# SPU_Rev_1_0.net
KiCad netlist of a schematic drawn in EAGLE
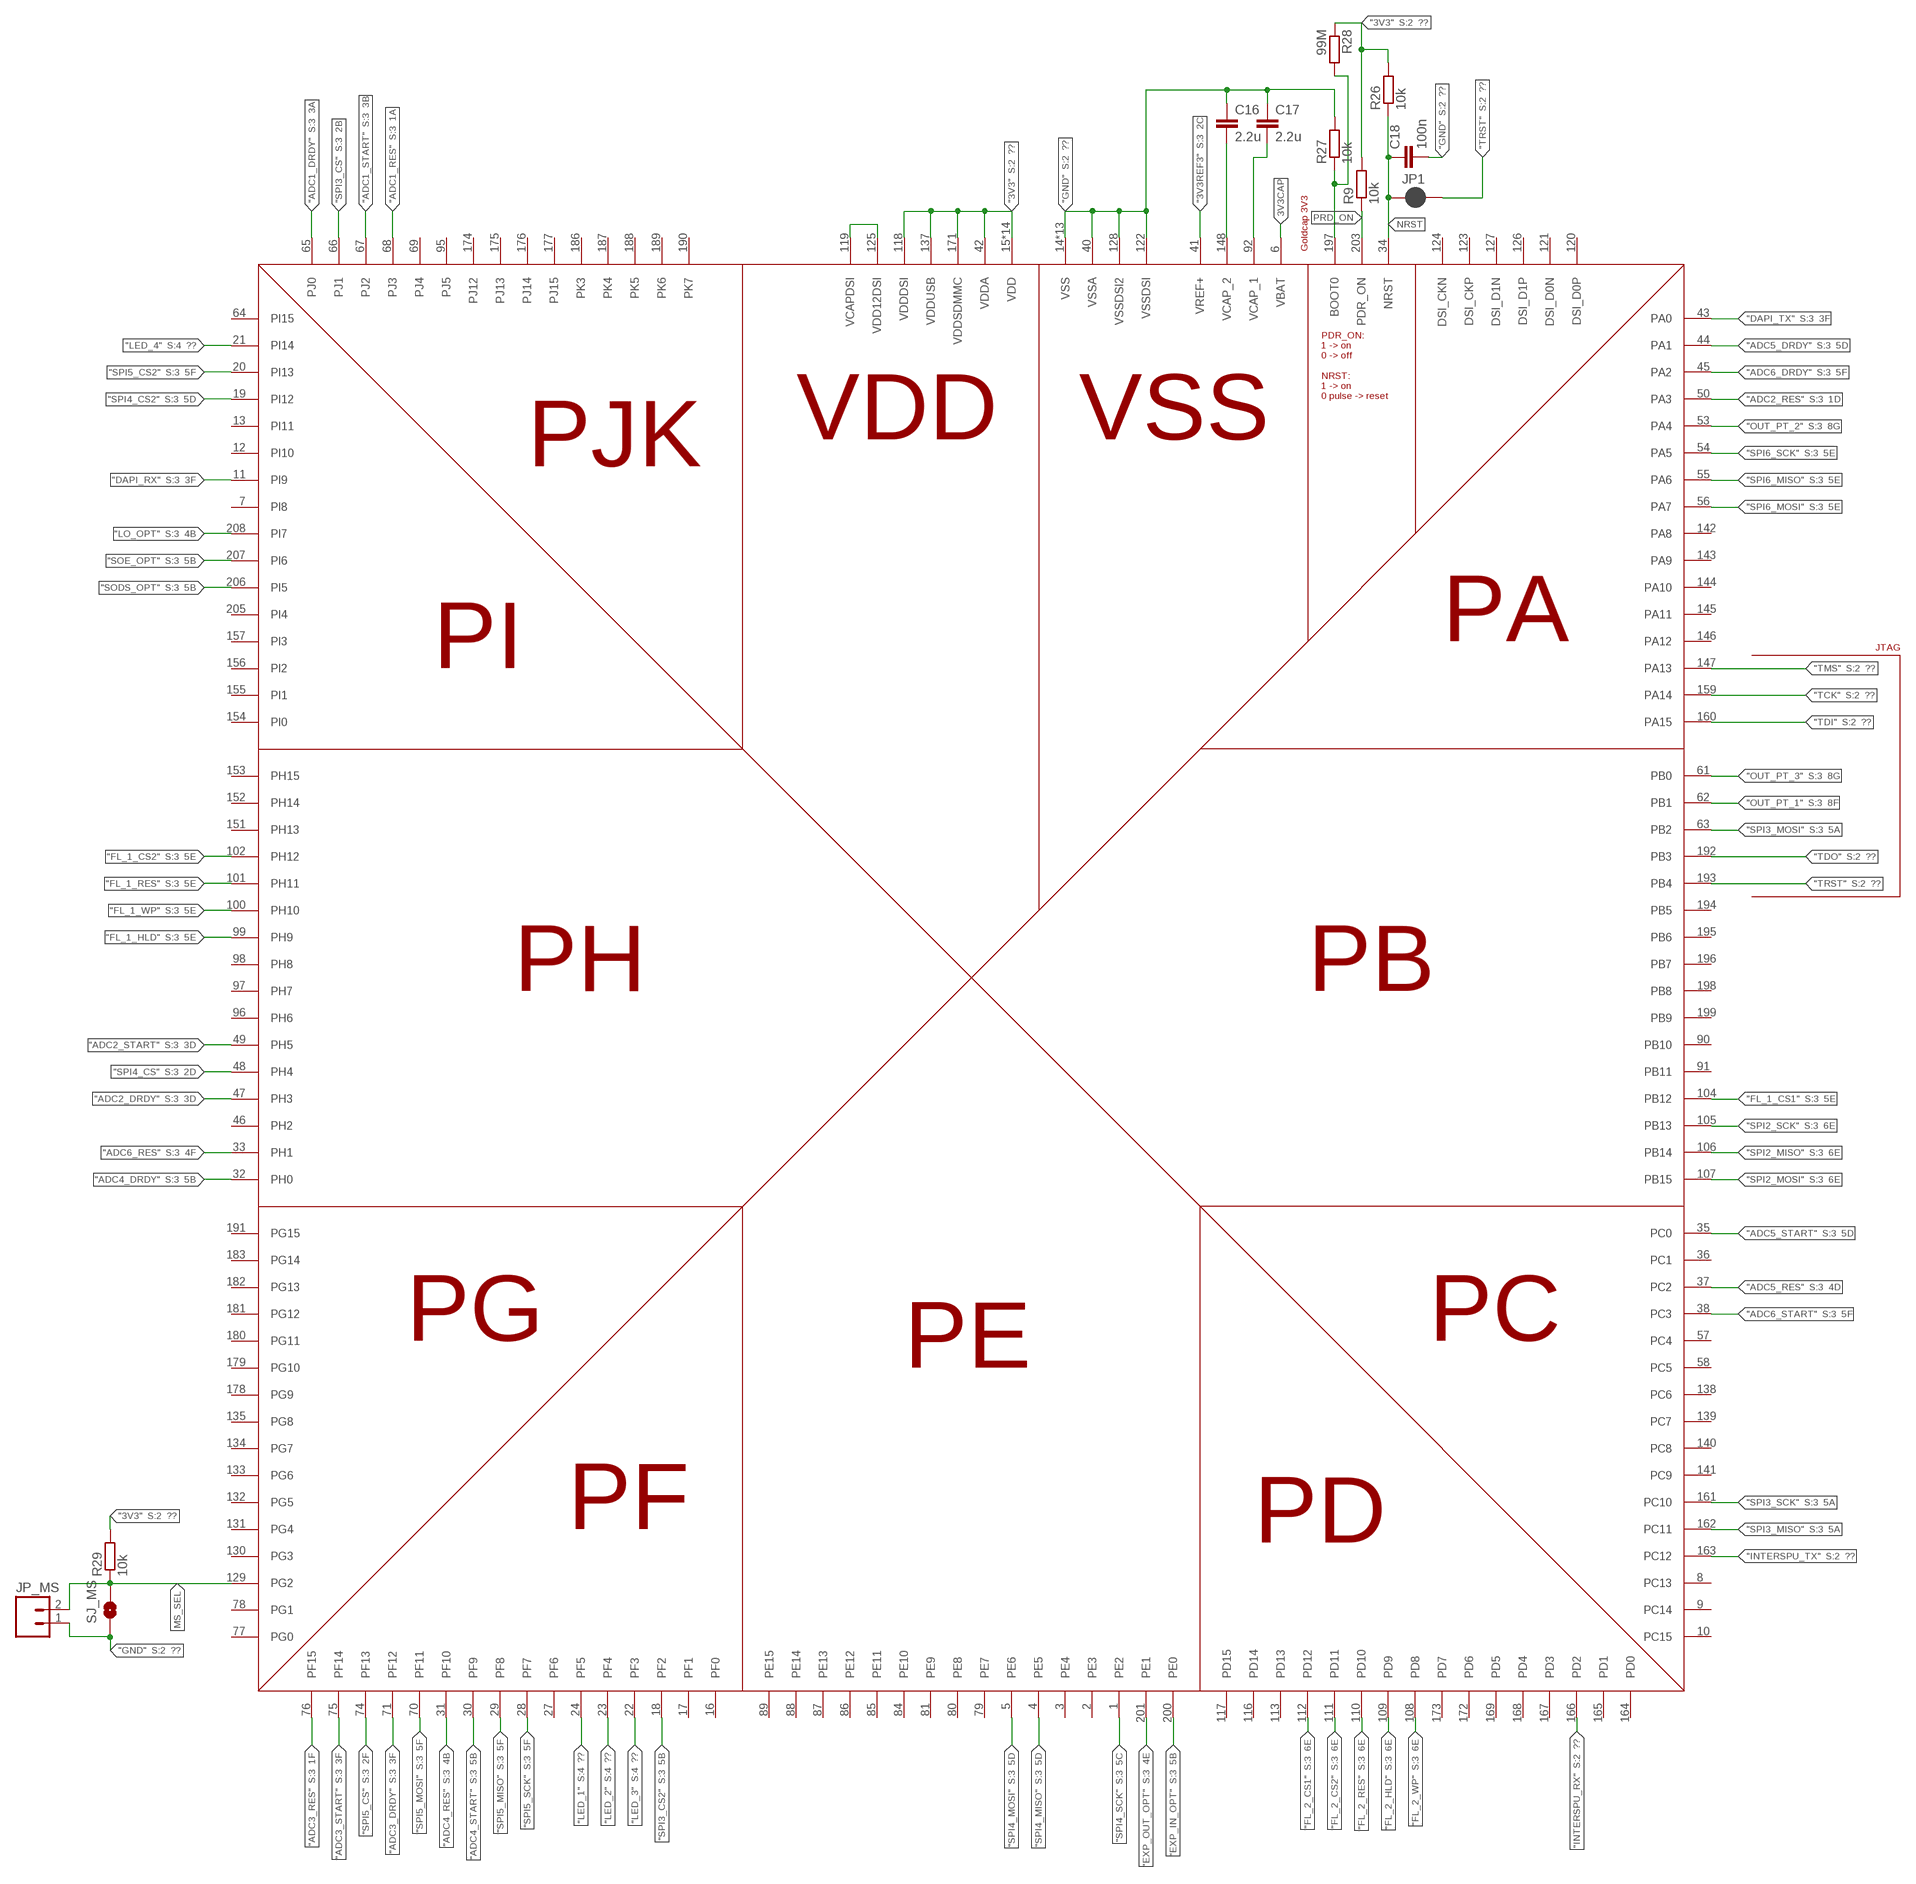
[diagram p0: schematic, sheet 1]
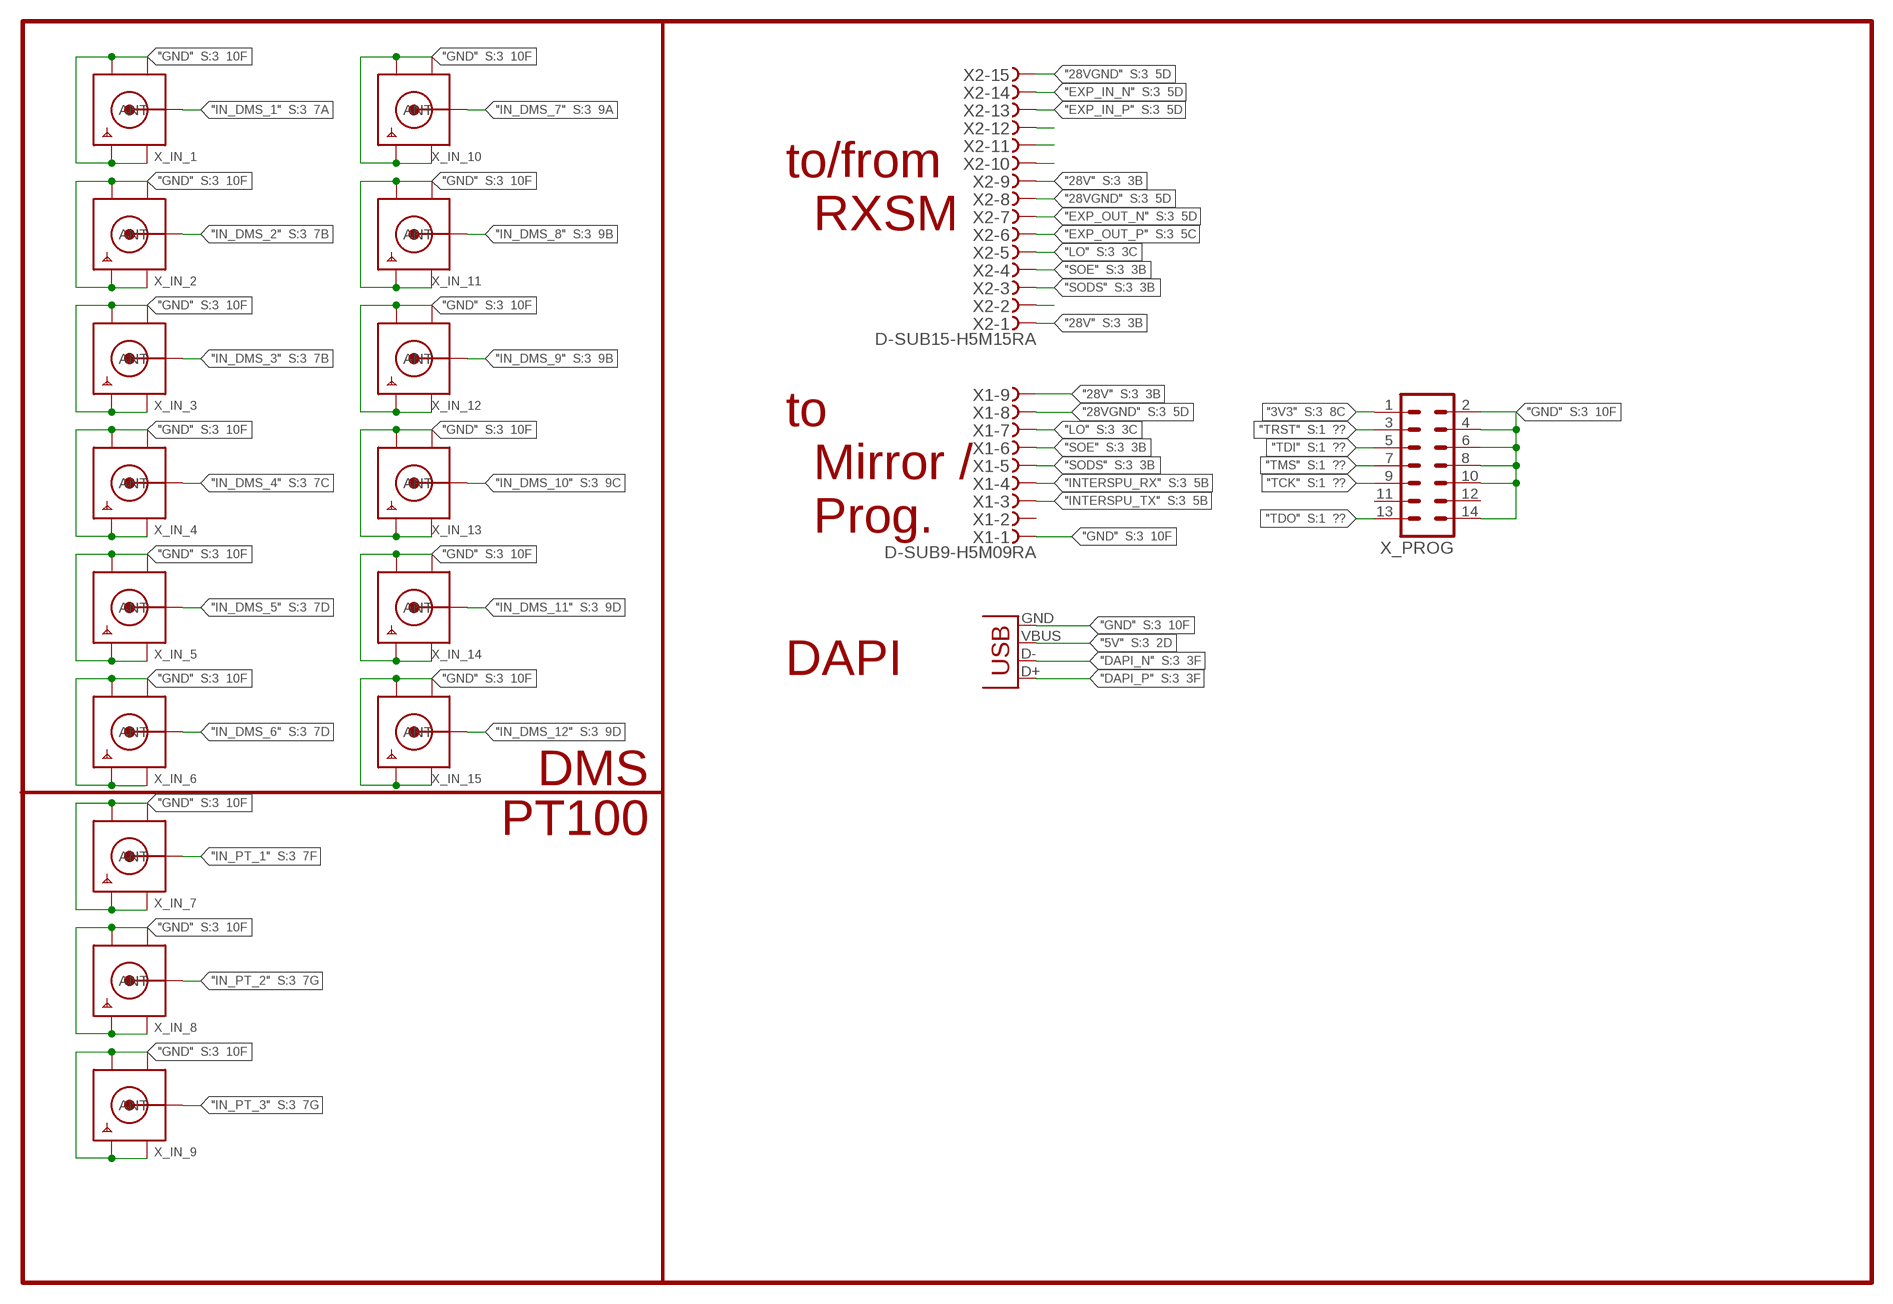
[diagram p1: schematic, sheet 2]
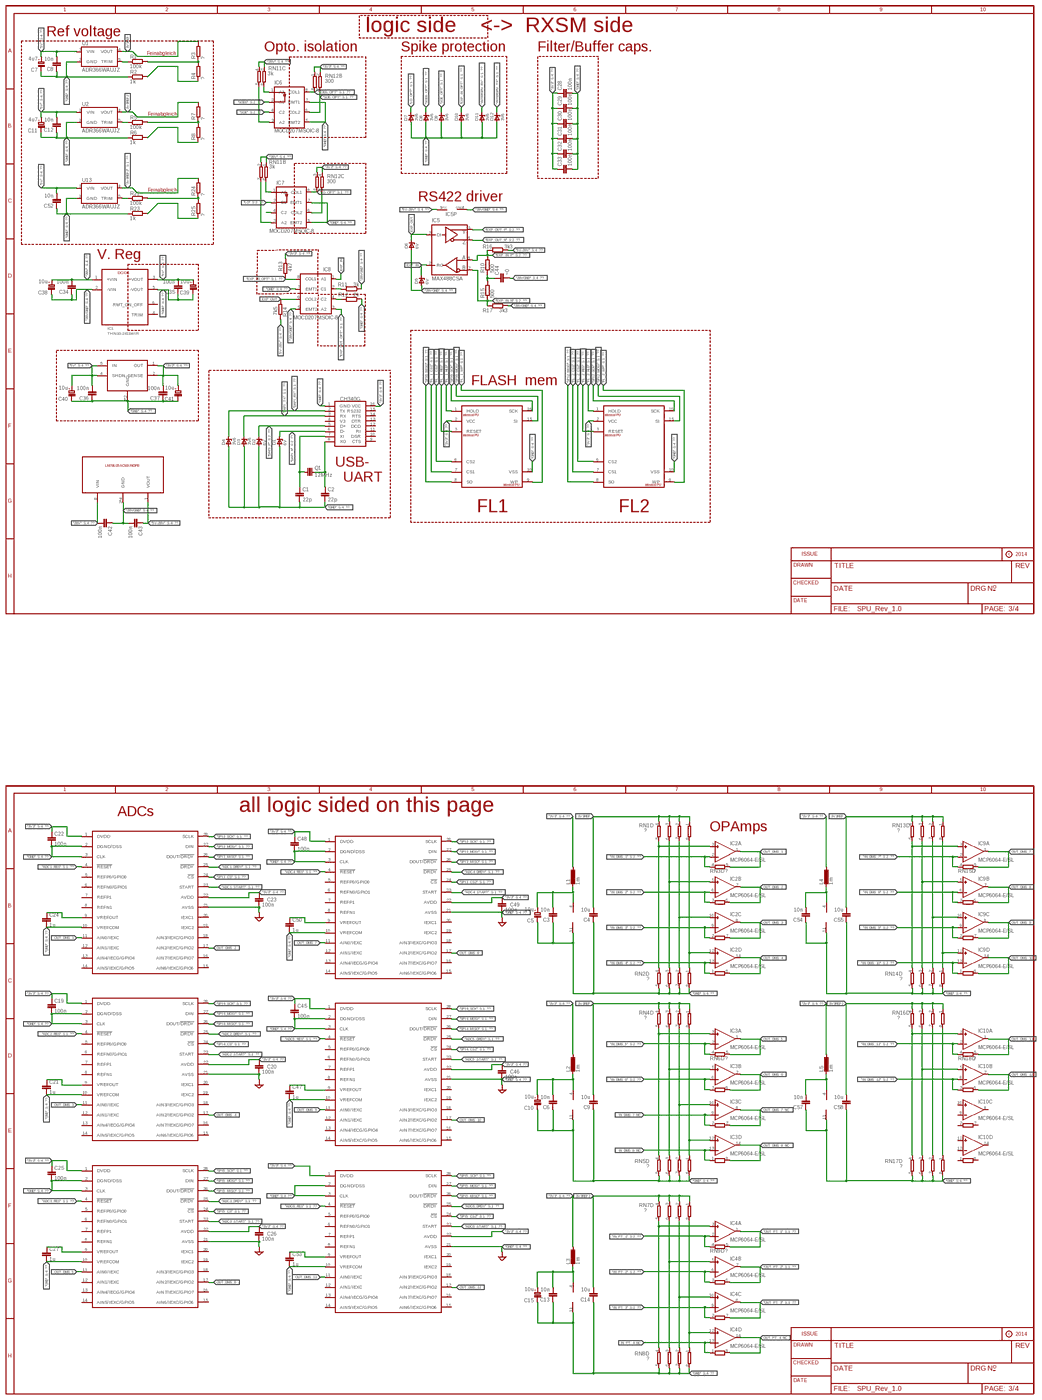
[diagram p2: schematic, sheet 3, overview]
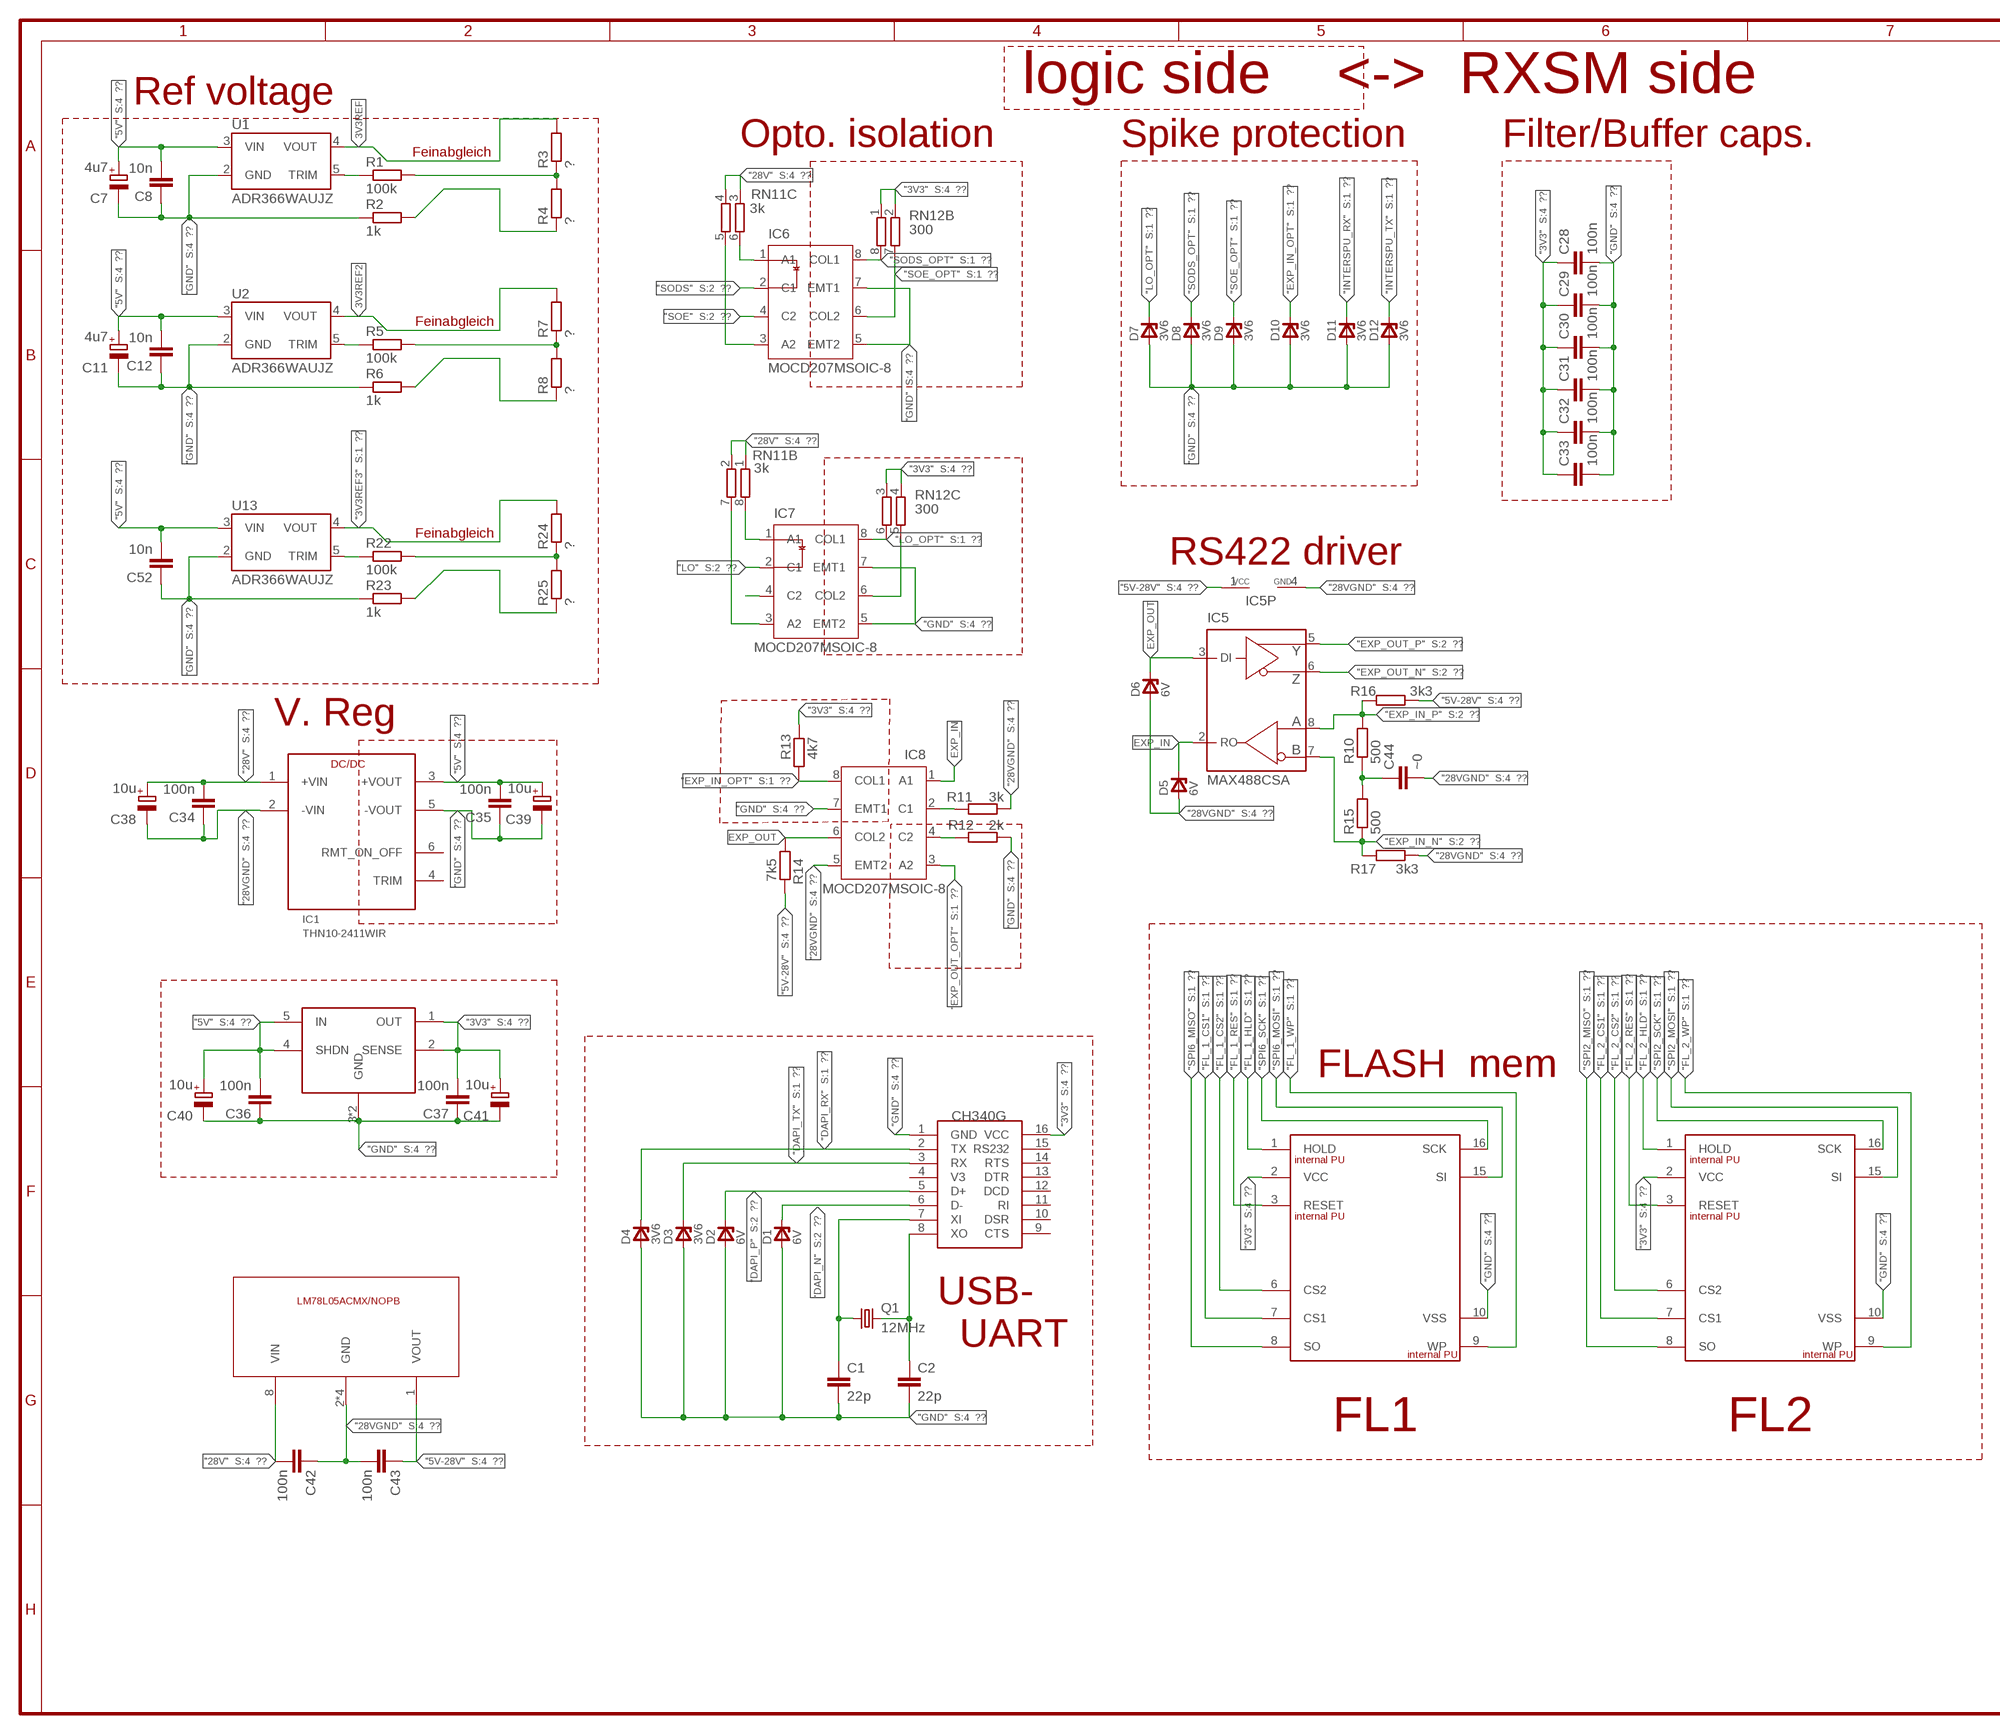
[diagram p3: schematic, sheet 3, part 1 of 4]
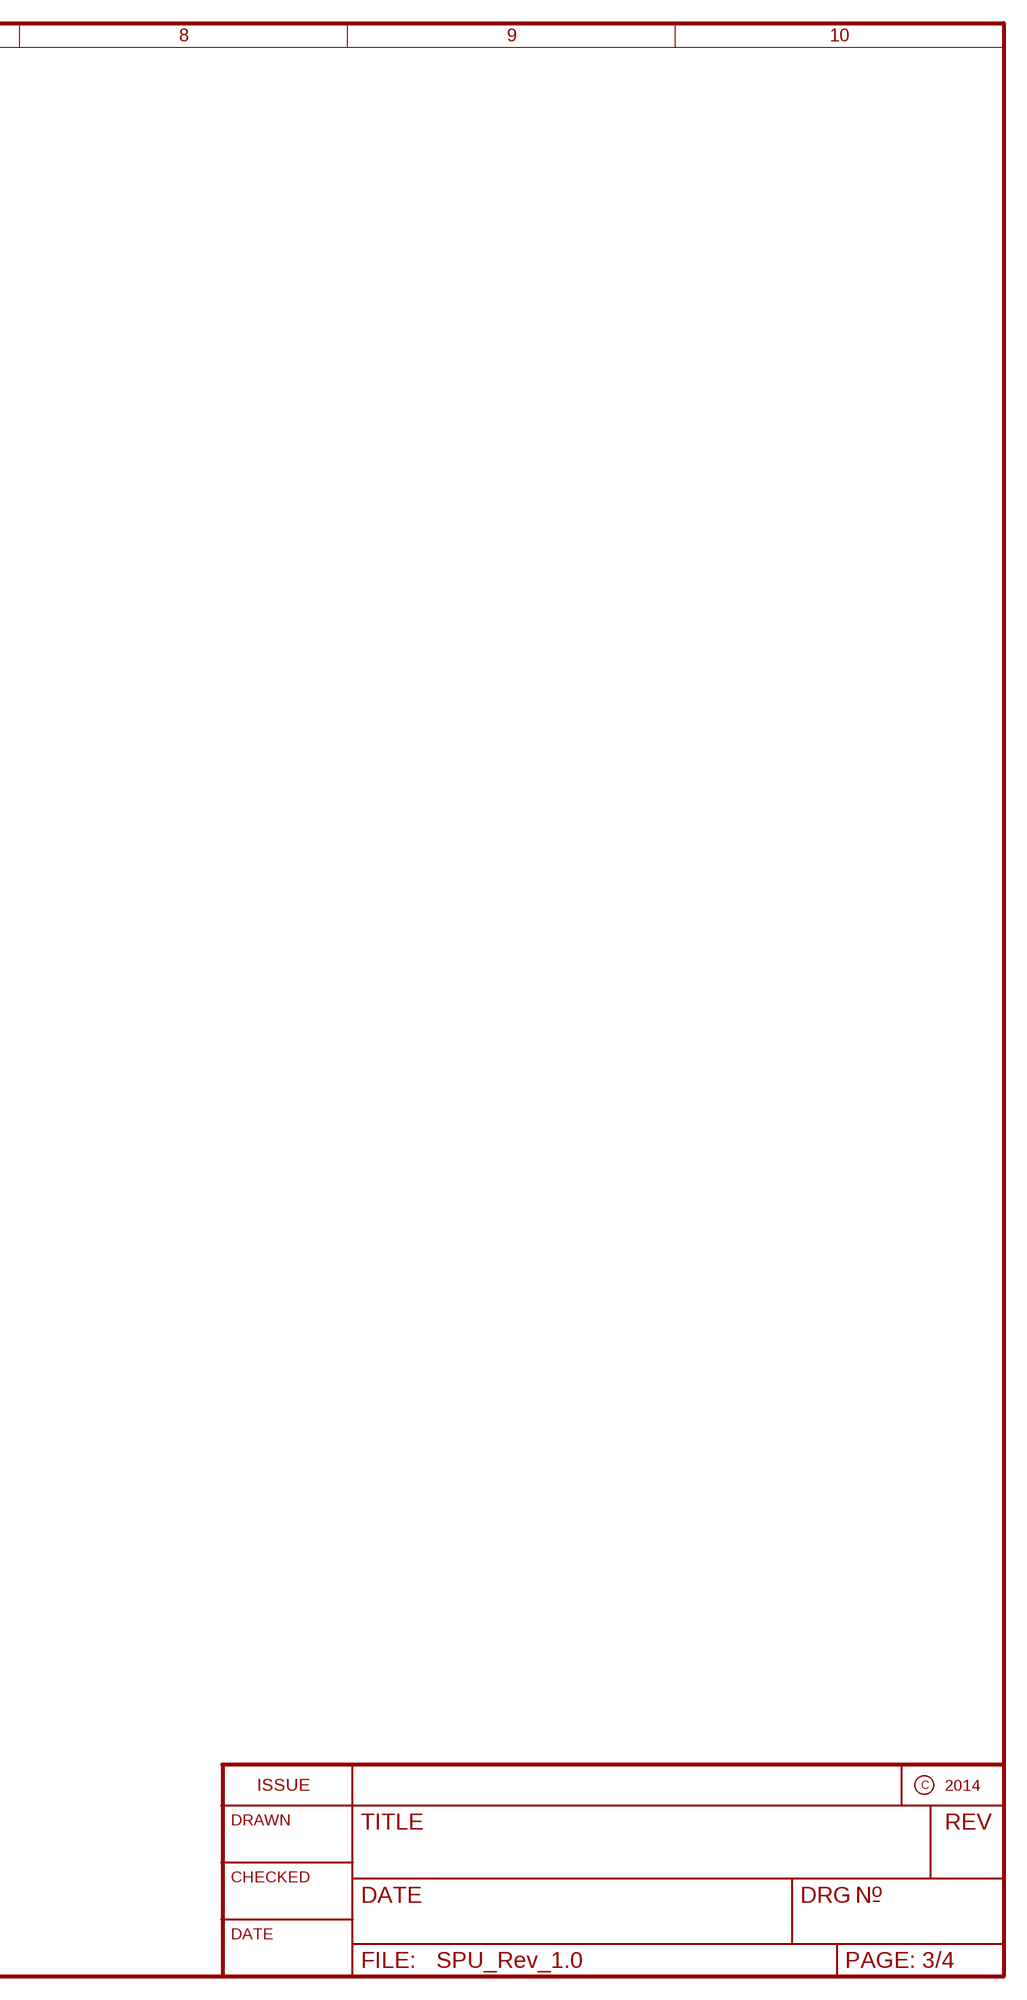
[diagram p4: schematic, sheet 3, part 2 of 4]
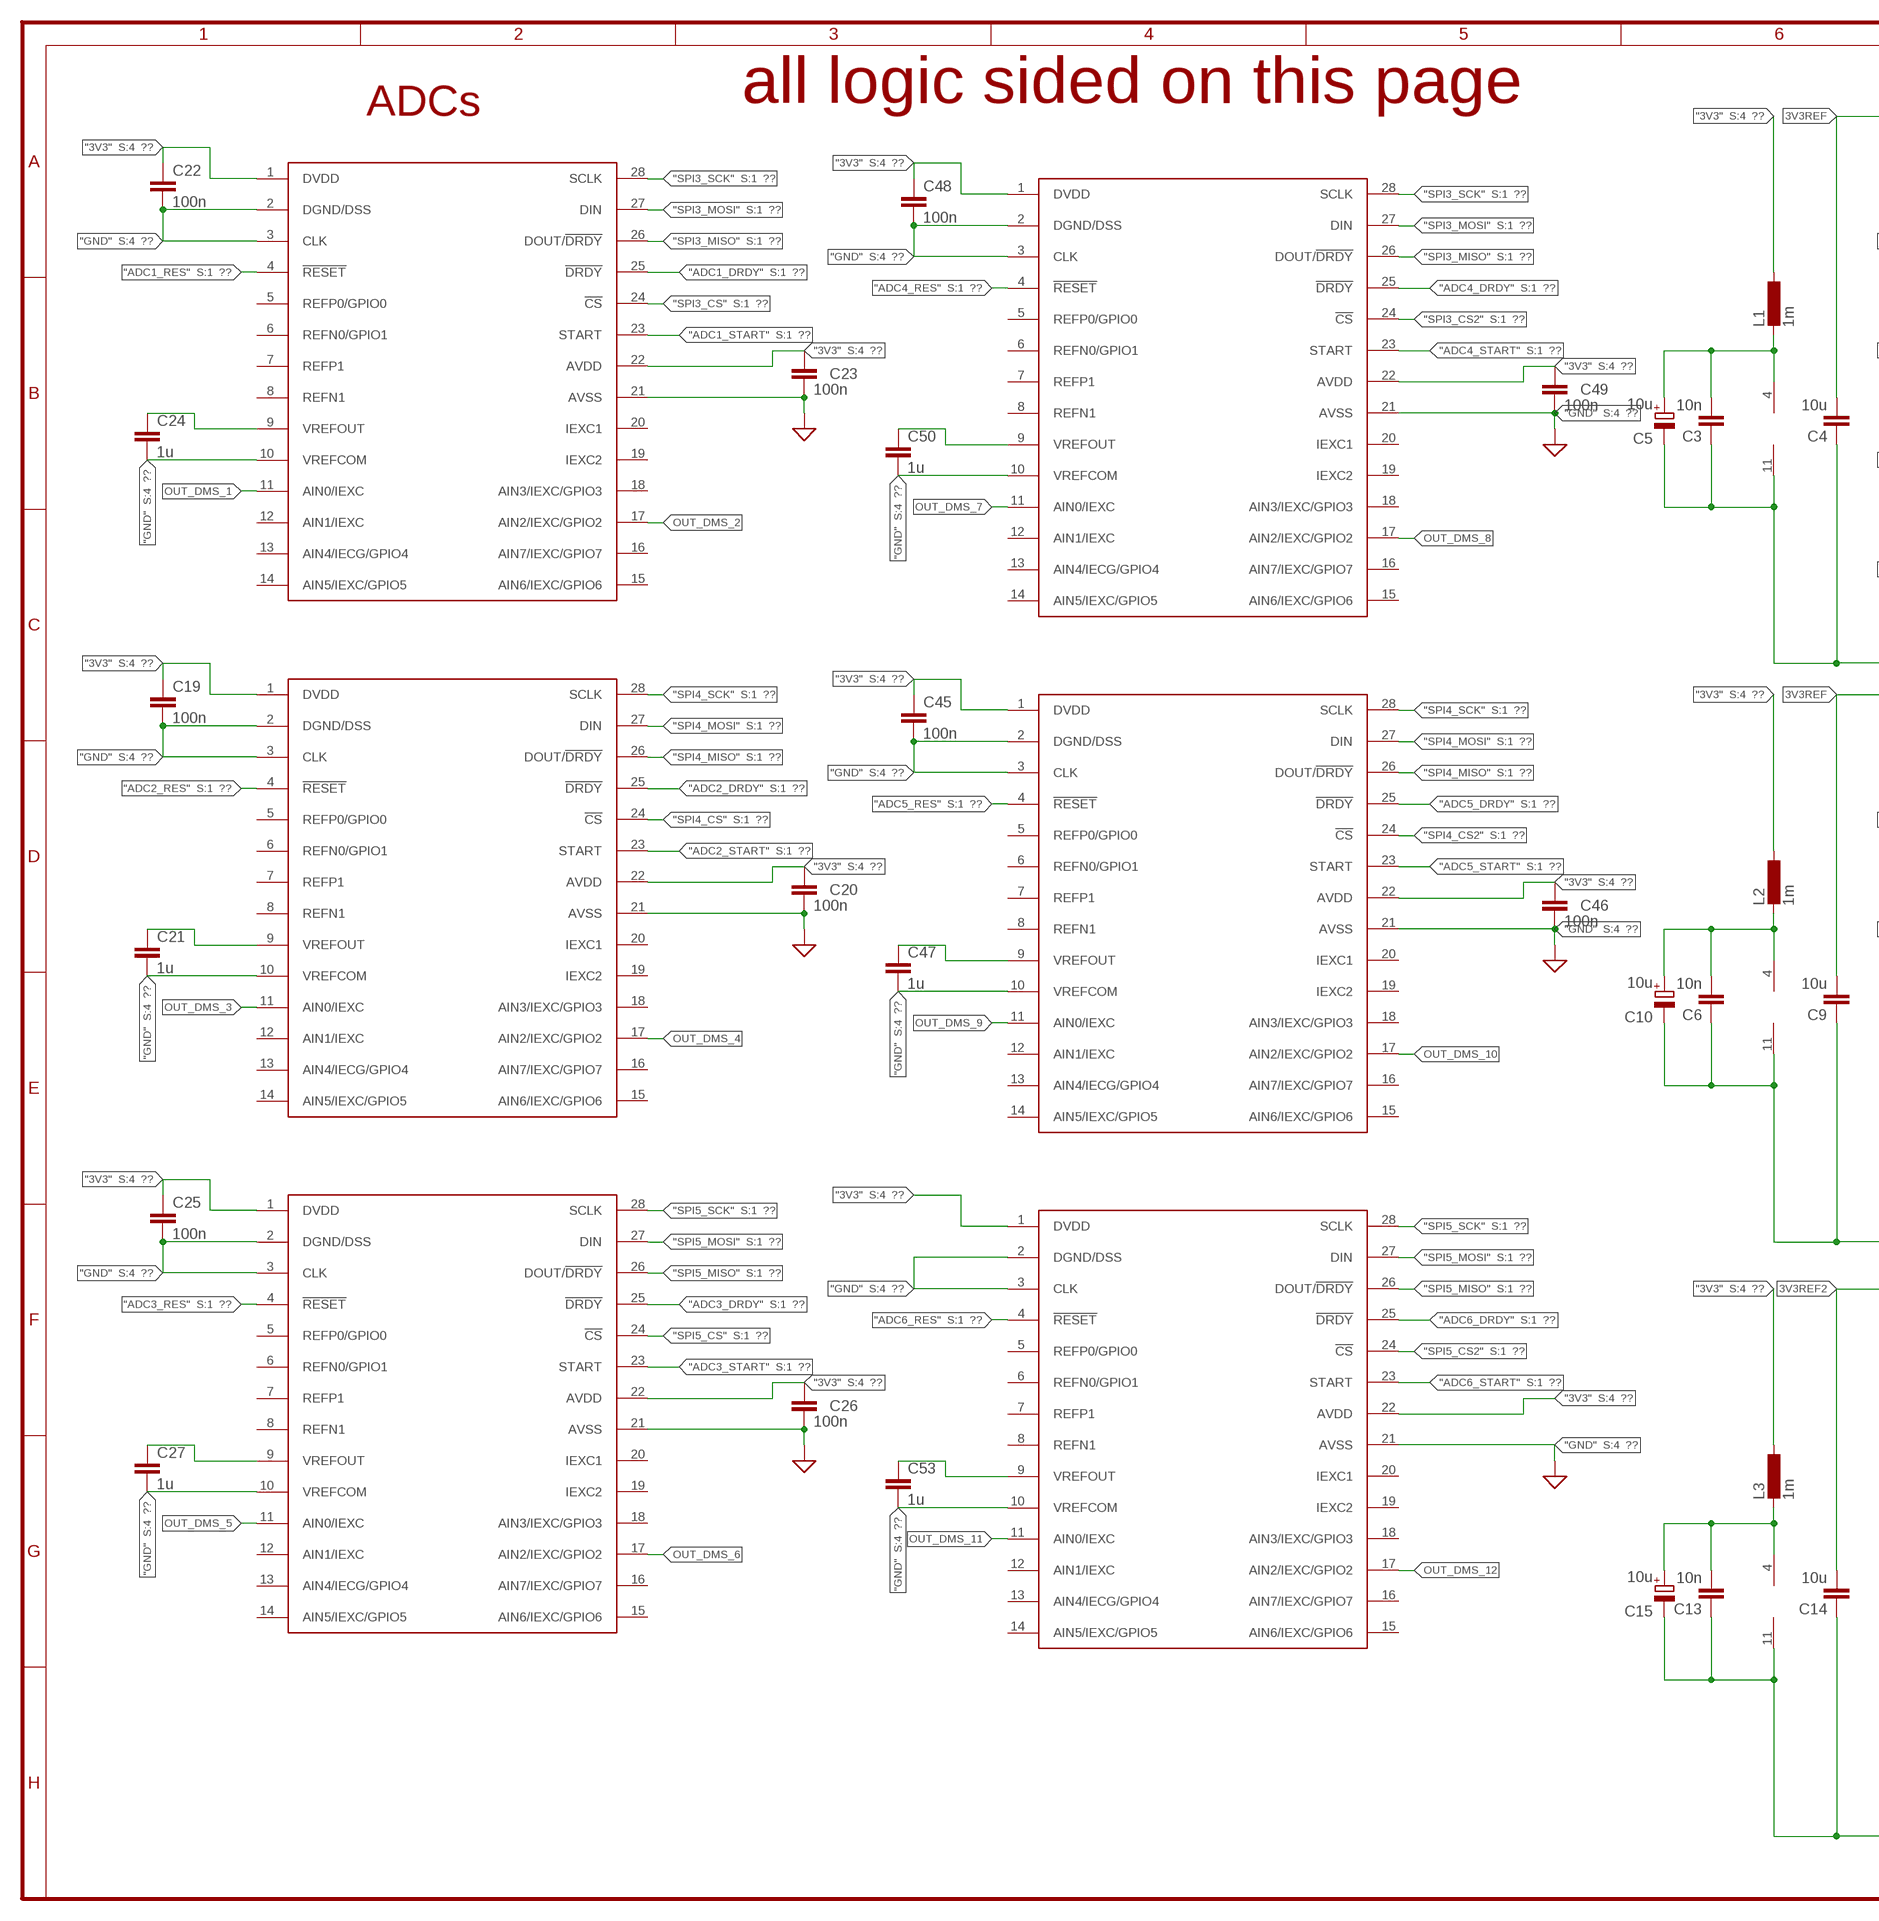
[diagram p5: schematic, sheet 3, part 3 of 4]
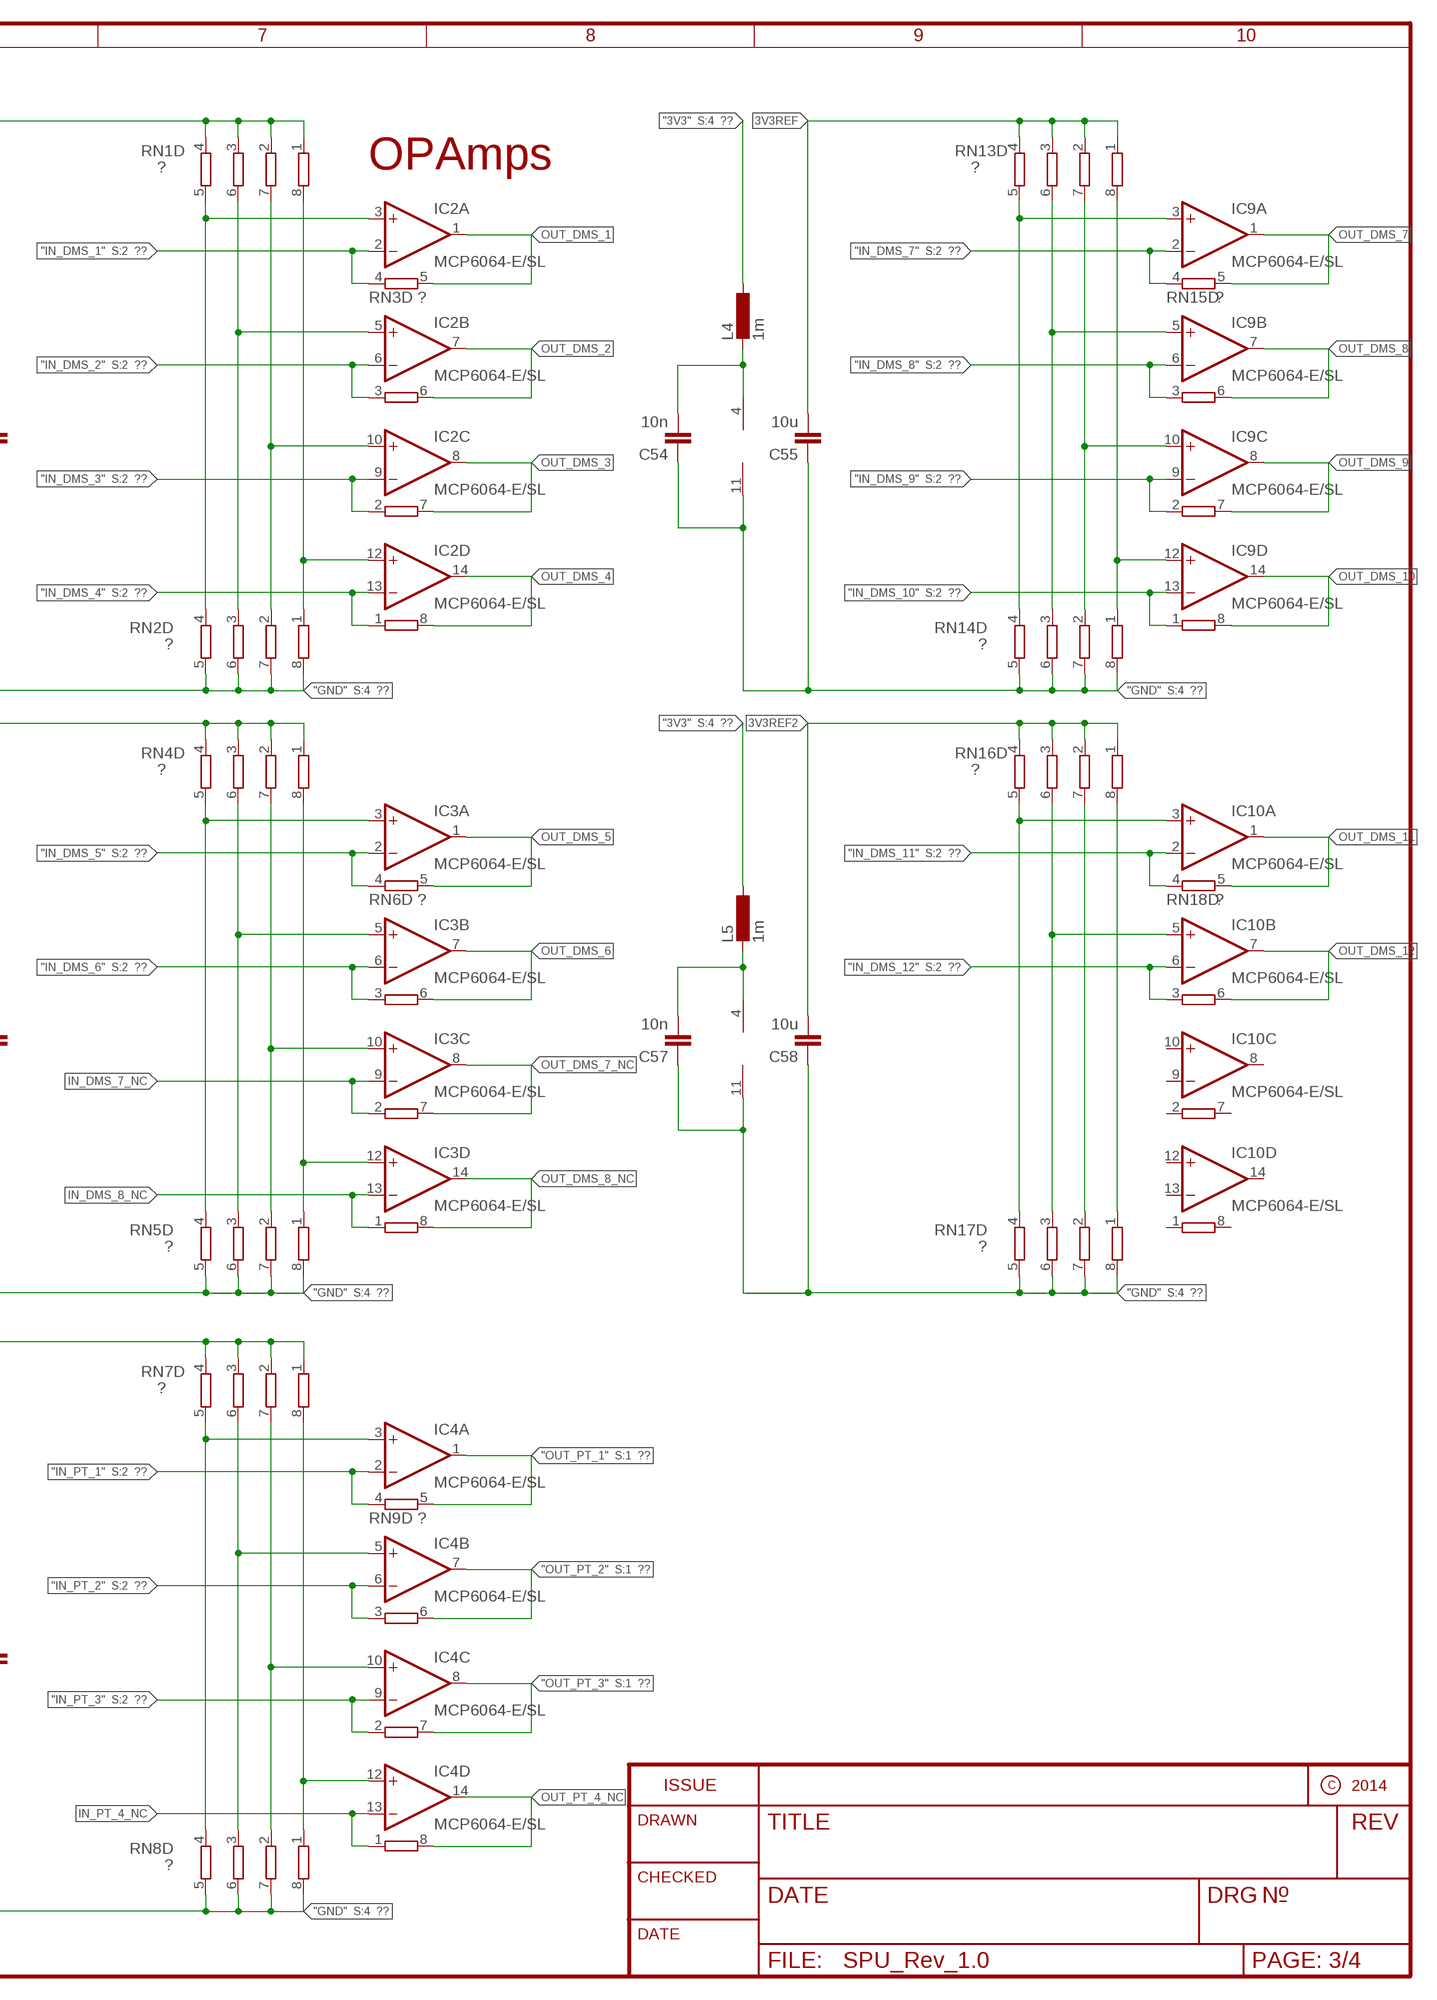
[diagram p6: schematic, sheet 3, part 4 of 4]
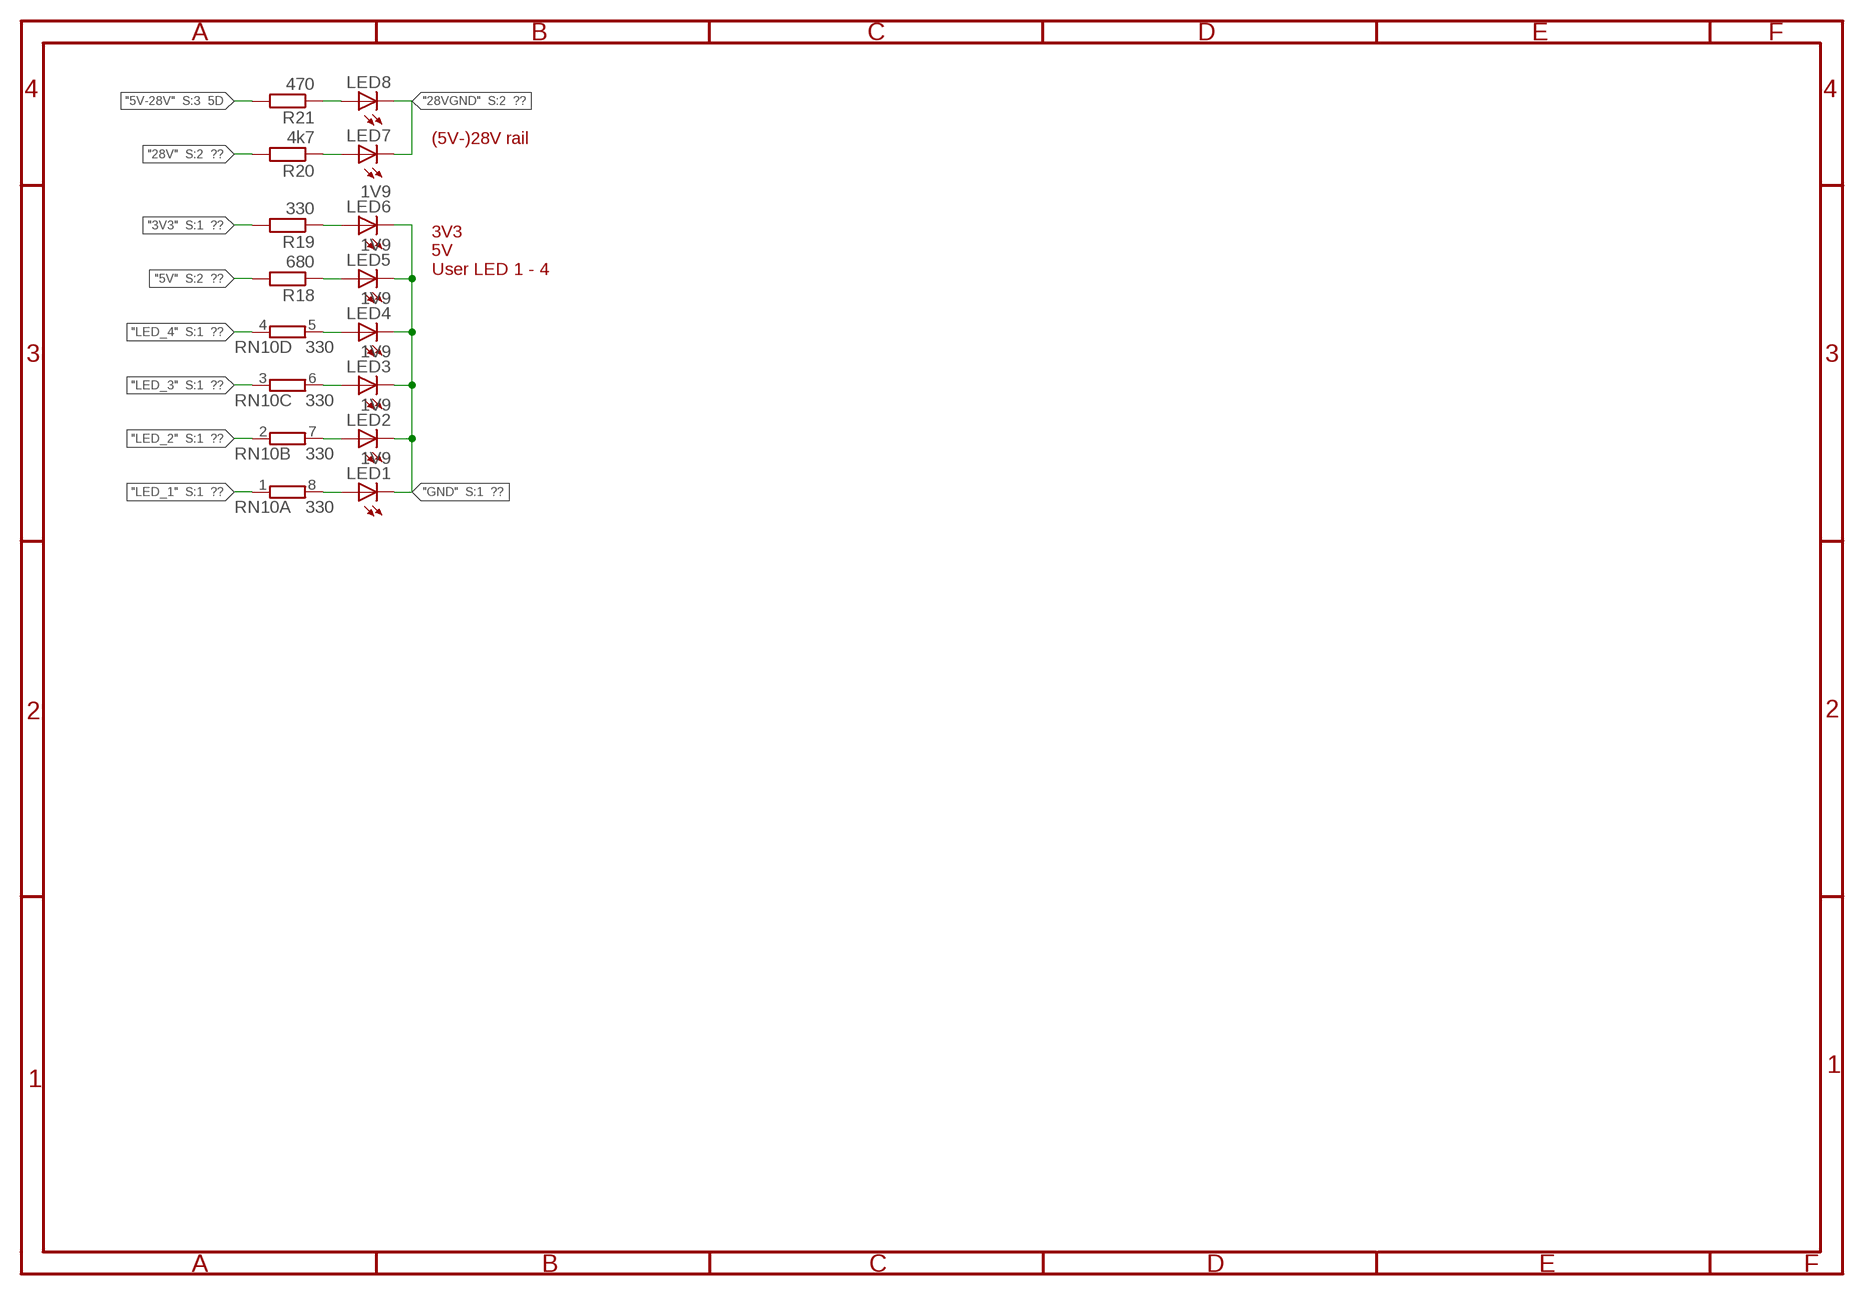
[diagram p7: schematic, sheet 4]

(export (version "E")
  (design (tool "Eeschema 10.0.6"))
  (components
    (comp (ref "C1")
      (value "22p")
      (footprint "eagle-import:C0603")
      (libsource (lib "eagle-import") (part "C-EUC0603"))
    )
    (comp (ref "C2")
      (value "22p")
      (footprint "eagle-import:C0603")
      (libsource (lib "eagle-import") (part "C-EUC0603"))
    )
    (comp (ref "C3")
      (value "10n")
      (footprint "eagle-import:C0805")
      (libsource (lib "eagle-import") (part "rcl_334_C-EUC0805"))
    )
    (comp (ref "C4")
      (value "10u")
      (footprint "eagle-import:C0805")
      (libsource (lib "eagle-import") (part "rcl_334_C-EUC0805"))
    )
    (comp (ref "C5")
      (value "10u")
      (footprint "eagle-import:153CLV-0810")
      (libsource (lib "eagle-import") (part "CPOL-EU153CLV-0810"))
    )
    (comp (ref "C6")
      (value "10n")
      (footprint "eagle-import:C0805")
      (libsource (lib "eagle-import") (part "rcl_334_C-EUC0805"))
    )
    (comp (ref "C7")
      (value "4u7")
      (footprint "eagle-import:153CLV-0810")
      (libsource (lib "eagle-import") (part "CPOL-EU153CLV-0810"))
    )
    (comp (ref "C8")
      (value "10n")
      (footprint "eagle-import:C0805")
      (libsource (lib "eagle-import") (part "rcl_334_C-EUC0805"))
    )
    (comp (ref "C9")
      (value "10u")
      (footprint "eagle-import:C0805")
      (libsource (lib "eagle-import") (part "rcl_334_C-EUC0805"))
    )
    (comp (ref "C10")
      (value "10u")
      (footprint "eagle-import:153CLV-0810")
      (libsource (lib "eagle-import") (part "CPOL-EU153CLV-0810"))
    )
    (comp (ref "C11")
      (value "4u7")
      (footprint "eagle-import:153CLV-0810")
      (libsource (lib "eagle-import") (part "CPOL-EU153CLV-0810"))
    )
    (comp (ref "C12")
      (value "10n")
      (footprint "eagle-import:C0805")
      (libsource (lib "eagle-import") (part "rcl_334_C-EUC0805"))
    )
    (comp (ref "C13")
      (value "10n")
      (footprint "eagle-import:C0805")
      (libsource (lib "eagle-import") (part "rcl_334_C-EUC0805"))
    )
    (comp (ref "C14")
      (value "10u")
      (footprint "eagle-import:C0805")
      (libsource (lib "eagle-import") (part "rcl_334_C-EUC0805"))
    )
    (comp (ref "C15")
      (value "10u")
      (footprint "eagle-import:153CLV-0810")
      (libsource (lib "eagle-import") (part "CPOL-EU153CLV-0810"))
    )
    (comp (ref "C19")
      (value "100n")
      (footprint "eagle-import:C0805")
      (libsource (lib "eagle-import") (part "rcl_334_C-EUC0805"))
    )
    (comp (ref "C20")
      (value "100n")
      (footprint "eagle-import:C0805")
      (libsource (lib "eagle-import") (part "rcl_334_C-EUC0805"))
    )
    (comp (ref "C21")
      (value "1u")
      (footprint "eagle-import:C0805")
      (libsource (lib "eagle-import") (part "rcl_334_C-EUC0805"))
    )
    (comp (ref "C22")
      (value "100n")
      (footprint "eagle-import:C0805")
      (libsource (lib "eagle-import") (part "rcl_334_C-EUC0805"))
    )
    (comp (ref "C23")
      (value "100n")
      (footprint "eagle-import:C0805")
      (libsource (lib "eagle-import") (part "rcl_334_C-EUC0805"))
    )
    (comp (ref "C24")
      (value "1u")
      (footprint "eagle-import:C0805")
      (libsource (lib "eagle-import") (part "rcl_334_C-EUC0805"))
    )
    (comp (ref "C25")
      (value "100n")
      (footprint "eagle-import:C0805")
      (libsource (lib "eagle-import") (part "rcl_334_C-EUC0805"))
    )
    (comp (ref "C26")
      (value "100n")
      (footprint "eagle-import:C0805")
      (libsource (lib "eagle-import") (part "rcl_334_C-EUC0805"))
    )
    (comp (ref "C27")
      (value "1u")
      (footprint "eagle-import:C0805")
      (libsource (lib "eagle-import") (part "rcl_334_C-EUC0805"))
    )
    (comp (ref "C28")
      (value "100n")
      (footprint "eagle-import:C0805")
      (libsource (lib "eagle-import") (part "rcl_334_C-EUC0805"))
    )
    (comp (ref "C29")
      (value "100n")
      (footprint "eagle-import:C0805")
      (libsource (lib "eagle-import") (part "rcl_334_C-EUC0805"))
    )
    (comp (ref "C30")
      (value "100n")
      (footprint "eagle-import:C0805")
      (libsource (lib "eagle-import") (part "rcl_334_C-EUC0805"))
    )
    (comp (ref "C31")
      (value "100n")
      (footprint "eagle-import:C0805")
      (libsource (lib "eagle-import") (part "rcl_334_C-EUC0805"))
    )
    (comp (ref "C32")
      (value "100n")
      (footprint "eagle-import:C0805")
      (libsource (lib "eagle-import") (part "rcl_334_C-EUC0805"))
    )
    (comp (ref "C33")
      (value "100n")
      (footprint "eagle-import:C0805")
      (libsource (lib "eagle-import") (part "rcl_334_C-EUC0805"))
    )
    (comp (ref "C34")
      (value "100n")
      (footprint "eagle-import:C0805")
      (libsource (lib "eagle-import") (part "rcl_334_C-EUC0805"))
    )
    (comp (ref "C35")
      (value "100n")
      (footprint "eagle-import:C0805")
      (libsource (lib "eagle-import") (part "rcl_334_C-EUC0805"))
    )
    (comp (ref "C36")
      (value "100n")
      (footprint "eagle-import:C0805")
      (libsource (lib "eagle-import") (part "rcl_334_C-EUC0805"))
    )
    (comp (ref "C37")
      (value "100n")
      (footprint "eagle-import:C0805")
      (libsource (lib "eagle-import") (part "rcl_334_C-EUC0805"))
    )
    (comp (ref "C38")
      (value "10u")
      (footprint "eagle-import:153CLV-0810")
      (libsource (lib "eagle-import") (part "CPOL-EU153CLV-0810"))
    )
    (comp (ref "C39")
      (value "10u")
      (footprint "eagle-import:153CLV-0810")
      (libsource (lib "eagle-import") (part "CPOL-EU153CLV-0810"))
    )
    (comp (ref "C40")
      (value "10u")
      (footprint "eagle-import:153CLV-0810")
      (libsource (lib "eagle-import") (part "CPOL-EU153CLV-0810"))
    )
    (comp (ref "C41")
      (value "10u")
      (footprint "eagle-import:153CLV-0810")
      (libsource (lib "eagle-import") (part "CPOL-EU153CLV-0810"))
    )
    (comp (ref "C42")
      (value "100n")
      (footprint "eagle-import:C0805")
      (libsource (lib "eagle-import") (part "rcl_334_C-EUC0805"))
    )
    (comp (ref "C43")
      (value "100n")
      (footprint "eagle-import:C0805")
      (libsource (lib "eagle-import") (part "rcl_334_C-EUC0805"))
    )
    (comp (ref "C44")
      (value "~0")
      (footprint "eagle-import:C0805")
      (libsource (lib "eagle-import") (part "rcl_334_C-EUC0805"))
    )
    (comp (ref "C45")
      (value "100n")
      (footprint "eagle-import:C0805")
      (libsource (lib "eagle-import") (part "rcl_334_C-EUC0805"))
    )
    (comp (ref "C46")
      (value "100n")
      (footprint "eagle-import:C0805")
      (libsource (lib "eagle-import") (part "rcl_334_C-EUC0805"))
    )
    (comp (ref "C47")
      (value "1u")
      (footprint "eagle-import:C0805")
      (libsource (lib "eagle-import") (part "rcl_334_C-EUC0805"))
    )
    (comp (ref "C48")
      (value "100n")
      (footprint "eagle-import:C0805")
      (libsource (lib "eagle-import") (part "rcl_334_C-EUC0805"))
    )
    (comp (ref "C49")
      (value "100n")
      (footprint "eagle-import:C0805")
      (libsource (lib "eagle-import") (part "rcl_334_C-EUC0805"))
    )
    (comp (ref "C50")
      (value "1u")
      (footprint "eagle-import:C0805")
      (libsource (lib "eagle-import") (part "rcl_334_C-EUC0805"))
    )
    (comp (ref "C52")
      (value "10n")
      (footprint "eagle-import:C0805")
      (libsource (lib "eagle-import") (part "rcl_334_C-EUC0805"))
    )
    (comp (ref "C53")
      (value "1u")
      (footprint "eagle-import:C0805")
      (libsource (lib "eagle-import") (part "rcl_334_C-EUC0805"))
    )
    (comp (ref "C54")
      (value "10n")
      (footprint "eagle-import:C0805")
      (libsource (lib "eagle-import") (part "rcl_334_C-EUC0805"))
    )
    (comp (ref "C55")
      (value "10u")
      (footprint "eagle-import:C0805")
      (libsource (lib "eagle-import") (part "rcl_334_C-EUC0805"))
    )
    (comp (ref "C57")
      (value "10n")
      (footprint "eagle-import:C0805")
      (libsource (lib "eagle-import") (part "rcl_334_C-EUC0805"))
    )
    (comp (ref "C58")
      (value "10u")
      (footprint "eagle-import:C0805")
      (libsource (lib "eagle-import") (part "rcl_334_C-EUC0805"))
    )
    (comp (ref "D1")
      (value "6V")
      (footprint "eagle-import:DMELF")
      (libsource (lib "eagle-import") (part "DZMELF"))
    )
    (comp (ref "D2")
      (value "6V")
      (footprint "eagle-import:DMELF")
      (libsource (lib "eagle-import") (part "DZMELF"))
    )
    (comp (ref "D3")
      (value "3V6")
      (footprint "eagle-import:DMELF")
      (libsource (lib "eagle-import") (part "DZMELF"))
    )
    (comp (ref "D4")
      (value "3V6")
      (footprint "eagle-import:DMELF")
      (libsource (lib "eagle-import") (part "DZMELF"))
    )
    (comp (ref "D5")
      (value "6V")
      (footprint "eagle-import:DMELF")
      (libsource (lib "eagle-import") (part "DZMELF"))
    )
    (comp (ref "D6")
      (value "6V")
      (footprint "eagle-import:DMELF")
      (libsource (lib "eagle-import") (part "DZMELF"))
    )
    (comp (ref "D7")
      (value "3V6")
      (footprint "eagle-import:DMELF")
      (libsource (lib "eagle-import") (part "DZMELF"))
    )
    (comp (ref "D8")
      (value "3V6")
      (footprint "eagle-import:DMELF")
      (libsource (lib "eagle-import") (part "DZMELF"))
    )
    (comp (ref "D9")
      (value "3V6")
      (footprint "eagle-import:DMELF")
      (libsource (lib "eagle-import") (part "DZMELF"))
    )
    (comp (ref "D10")
      (value "3V6")
      (footprint "eagle-import:DMELF")
      (libsource (lib "eagle-import") (part "DZMELF"))
    )
    (comp (ref "D11")
      (value "3V6")
      (footprint "eagle-import:DMELF")
      (libsource (lib "eagle-import") (part "DZMELF"))
    )
    (comp (ref "D12")
      (value "3V6")
      (footprint "eagle-import:DMELF")
      (libsource (lib "eagle-import") (part "DZMELF"))
    )
    (comp (ref "IC1")
      (value "THN10-2411WIR")
      (footprint "eagle-import:THL_20WI_SERIES")
      (libsource (lib "eagle-import") (part "THL_20WI_SERIES"))
    )
    (comp (ref "IC2")
      (value "MCP6064-E/SL")
      (footprint "eagle-import:SO14")
      (libsource (lib "eagle-import") (part "MCP604SL"))
    )
    (comp (ref "IC3")
      (value "MCP6064-E/SL")
      (footprint "eagle-import:SO14")
      (libsource (lib "eagle-import") (part "MCP604SL"))
    )
    (comp (ref "IC4")
      (value "MCP6064-E/SL")
      (footprint "eagle-import:SO14")
      (libsource (lib "eagle-import") (part "MCP604SL"))
    )
    (comp (ref "IC5")
      (value "MAX488CSA")
      (footprint "eagle-import:SO08")
      (fields (field (name "MF") "MAXIM"))
      (libsource (lib "eagle-import") (part "MAX488CSA"))
    )
    (comp (ref "IC6")
      (value "MOCD207MSOIC-8")
      (footprint "eagle-import:SOIC127P594X363-8N")
      (fields (field (name "MANUFACTURER") "ON Semiconductor") (field (name "MPN") "MOCD207M"))
      (libsource (lib "eagle-import") (part "MOCD207MSOIC-8"))
    )
    (comp (ref "IC7")
      (value "MOCD207MSOIC-8")
      (footprint "eagle-import:SOIC127P594X363-8N")
      (fields (field (name "MANUFACTURER") "ON Semiconductor") (field (name "MPN") "MOCD207M"))
      (libsource (lib "eagle-import") (part "MOCD207MSOIC-8"))
    )
    (comp (ref "IC8")
      (value "MOCD207MSOIC-8")
      (footprint "eagle-import:SOIC127P594X363-8N")
      (fields (field (name "MANUFACTURER") "ON Semiconductor") (field (name "MPN") "MOCD207M"))
      (libsource (lib "eagle-import") (part "MOCD207MSOIC-8"))
    )
    (comp (ref "IC9")
      (value "MCP6064-E/SL")
      (footprint "eagle-import:SO14")
      (libsource (lib "eagle-import") (part "MCP604SL"))
    )
    (comp (ref "IC10")
      (value "MCP6064-E/SL")
      (footprint "eagle-import:SO14")
      (libsource (lib "eagle-import") (part "MCP604SL"))
    )
    (comp (ref "IC12")
      (value "LM78L05ACMX/NOPB")
      (footprint "eagle-import:SOIC8")
      (libsource (lib "eagle-import") (part "LM78L05ACMX/NOPB"))
    )
    (comp (ref "IC13")
      (value "CH340G")
      (footprint "eagle-import:SOIC16")
      (libsource (lib "eagle-import") (part "CH340G"))
    )
    (comp (ref "L1")
      (value "1m")
      (footprint "eagle-import:L5650M")
      (libsource (lib "eagle-import") (part "L-EUL5650M"))
    )
    (comp (ref "L2")
      (value "1m")
      (footprint "eagle-import:L5650M")
      (libsource (lib "eagle-import") (part "L-EUL5650M"))
    )
    (comp (ref "L3")
      (value "1m")
      (footprint "eagle-import:L5650M")
      (libsource (lib "eagle-import") (part "L-EUL5650M"))
    )
    (comp (ref "L4")
      (value "1m")
      (footprint "eagle-import:L5650M")
      (libsource (lib "eagle-import") (part "L-EUL5650M"))
    )
    (comp (ref "L5")
      (value "1m")
      (footprint "eagle-import:L5650M")
      (libsource (lib "eagle-import") (part "L-EUL5650M"))
    )
    (comp (ref "Q1")
      (value "12MHz")
      (footprint "eagle-import:SM49")
      (libsource (lib "eagle-import") (part "CRYSTALSM49"))
    )
    (comp (ref "R1")
      (value "100k")
      (footprint "eagle-import:R0805")
      (libsource (lib "eagle-import") (part "rcl_334_R-EU_R0805"))
    )
    (comp (ref "R2")
      (value "1k")
      (footprint "eagle-import:R0805")
      (libsource (lib "eagle-import") (part "rcl_334_R-EU_R0805"))
    )
    (comp (ref "R3")
      (value "?")
      (footprint "eagle-import:R0805")
      (libsource (lib "eagle-import") (part "rcl_334_R-EU_R0805"))
    )
    (comp (ref "R4")
      (value "?")
      (footprint "eagle-import:R0805")
      (libsource (lib "eagle-import") (part "rcl_334_R-EU_R0805"))
    )
    (comp (ref "R5")
      (value "100k")
      (footprint "eagle-import:R0805")
      (libsource (lib "eagle-import") (part "rcl_334_R-EU_R0805"))
    )
    (comp (ref "R6")
      (value "1k")
      (footprint "eagle-import:R0805")
      (libsource (lib "eagle-import") (part "rcl_334_R-EU_R0805"))
    )
    (comp (ref "R7")
      (value "?")
      (footprint "eagle-import:R0805")
      (libsource (lib "eagle-import") (part "rcl_334_R-EU_R0805"))
    )
    (comp (ref "R8")
      (value "?")
      (footprint "eagle-import:R0805")
      (libsource (lib "eagle-import") (part "rcl_334_R-EU_R0805"))
    )
    (comp (ref "R10")
      (value "500")
      (footprint "eagle-import:R0805")
      (libsource (lib "eagle-import") (part "R-EU_R0805"))
    )
    (comp (ref "R11")
      (value "3k")
      (footprint "eagle-import:R0805")
      (libsource (lib "eagle-import") (part "rcl_334_R-EU_R0805"))
    )
    (comp (ref "R12")
      (value "2k")
      (footprint "eagle-import:R0805")
      (libsource (lib "eagle-import") (part "rcl_334_R-EU_R0805"))
    )
    (comp (ref "R13")
      (value "4k7")
      (footprint "eagle-import:R0805")
      (libsource (lib "eagle-import") (part "rcl_334_R-EU_R0805"))
    )
    (comp (ref "R14")
      (value "7k5")
      (footprint "eagle-import:R0805")
      (libsource (lib "eagle-import") (part "rcl_334_R-EU_R0805"))
    )
    (comp (ref "R15")
      (value "500")
      (footprint "eagle-import:R0805")
      (libsource (lib "eagle-import") (part "R-EU_R0805"))
    )
    (comp (ref "R16")
      (value "3k3")
      (footprint "eagle-import:R0805")
      (libsource (lib "eagle-import") (part "R-EU_R0805"))
    )
    (comp (ref "R17")
      (value "3k3")
      (footprint "eagle-import:R0805")
      (libsource (lib "eagle-import") (part "R-EU_R0805"))
    )
    (comp (ref "R22")
      (value "100k")
      (footprint "eagle-import:R0805")
      (libsource (lib "eagle-import") (part "rcl_334_R-EU_R0805"))
    )
    (comp (ref "R23")
      (value "1k")
      (footprint "eagle-import:R0805")
      (libsource (lib "eagle-import") (part "rcl_334_R-EU_R0805"))
    )
    (comp (ref "R24")
      (value "?")
      (footprint "eagle-import:R0805")
      (libsource (lib "eagle-import") (part "rcl_334_R-EU_R0805"))
    )
    (comp (ref "R25")
      (value "?")
      (footprint "eagle-import:R0805")
      (libsource (lib "eagle-import") (part "rcl_334_R-EU_R0805"))
    )
    (comp (ref "RN1")
      (value "?")
      (footprint "eagle-import:EXBS8V")
      (libsource (lib "eagle-import") (part "4R-NEXBS8V"))
    )
    (comp (ref "RN2")
      (value "?")
      (footprint "eagle-import:EXBS8V")
      (libsource (lib "eagle-import") (part "4R-NEXBS8V"))
    )
    (comp (ref "RN3")
      (value "?")
      (footprint "eagle-import:EXBS8V")
      (libsource (lib "eagle-import") (part "4R-NEXBS8V"))
    )
    (comp (ref "RN4")
      (value "?")
      (footprint "eagle-import:EXBS8V")
      (libsource (lib "eagle-import") (part "4R-NEXBS8V"))
    )
    (comp (ref "RN5")
      (value "?")
      (footprint "eagle-import:EXBS8V")
      (libsource (lib "eagle-import") (part "4R-NEXBS8V"))
    )
    (comp (ref "RN6")
      (value "?")
      (footprint "eagle-import:EXBS8V")
      (libsource (lib "eagle-import") (part "4R-NEXBS8V"))
    )
    (comp (ref "RN7")
      (value "?")
      (footprint "eagle-import:EXBS8V")
      (libsource (lib "eagle-import") (part "4R-NEXBS8V"))
    )
    (comp (ref "RN8")
      (value "?")
      (footprint "eagle-import:EXBS8V")
      (libsource (lib "eagle-import") (part "4R-NEXBS8V"))
    )
    (comp (ref "RN9")
      (value "?")
      (footprint "eagle-import:EXBS8V")
      (libsource (lib "eagle-import") (part "4R-NEXBS8V"))
    )
    (comp (ref "RN11")
      (value "3k")
      (footprint "eagle-import:EXBS8V")
      (libsource (lib "eagle-import") (part "4R-NEXBS8V"))
    )
    (comp (ref "RN12")
      (value "300")
      (footprint "eagle-import:EXBS8V")
      (libsource (lib "eagle-import") (part "4R-NEXBS8V"))
    )
    (comp (ref "RN13")
      (value "?")
      (footprint "eagle-import:EXBS8V")
      (libsource (lib "eagle-import") (part "4R-NEXBS8V"))
    )
    (comp (ref "RN14")
      (value "?")
      (footprint "eagle-import:EXBS8V")
      (libsource (lib "eagle-import") (part "4R-NEXBS8V"))
    )
    (comp (ref "RN15")
      (value "?")
      (footprint "eagle-import:EXBS8V")
      (libsource (lib "eagle-import") (part "4R-NEXBS8V"))
    )
    (comp (ref "RN16")
      (value "?")
      (footprint "eagle-import:EXBS8V")
      (libsource (lib "eagle-import") (part "4R-NEXBS8V"))
    )
    (comp (ref "RN17")
      (value "?")
      (footprint "eagle-import:EXBS8V")
      (libsource (lib "eagle-import") (part "4R-NEXBS8V"))
    )
    (comp (ref "RN18")
      (value "?")
      (footprint "eagle-import:EXBS8V")
      (libsource (lib "eagle-import") (part "4R-NEXBS8V"))
    )
    (comp (ref "U1")
      (value "ADR366WAUJZ")
      (footprint "eagle-import:SOT23-5")
      (libsource (lib "eagle-import") (part "ADR36UJZ_"))
    )
    (comp (ref "U2")
      (value "ADR366WAUJZ")
      (footprint "eagle-import:SOT23-5")
      (libsource (lib "eagle-import") (part "ADR36UJZ_"))
    )
    (comp (ref "U3")
      (value "ADS1148QPWRQ1")
      (footprint "eagle-import:TSSOP28")
      (libsource (lib "eagle-import") (part "ADS1148QPWRQ1"))
    )
    (comp (ref "U4")
      (value "ADS1148QPWRQ1")
      (footprint "eagle-import:TSSOP28")
      (libsource (lib "eagle-import") (part "ADS1148QPWRQ1"))
    )
    (comp (ref "U5")
      (value "ADS1148QPWRQ1")
      (footprint "eagle-import:TSSOP28")
      (libsource (lib "eagle-import") (part "ADS1148QPWRQ1"))
    )
    (comp (ref "U6")
      (value "LT1528")
      (footprint "eagle-import:Q5-DD")
      (libsource (lib "eagle-import") (part "LT1528"))
    )
    (comp (ref "U7")
      (value "S70FL01GS")
      (footprint "eagle-import:SO16")
      (libsource (lib "eagle-import") (part "S70FL01GS"))
    )
    (comp (ref "U8")
      (value "S70FL01GS")
      (footprint "eagle-import:SO16")
      (libsource (lib "eagle-import") (part "S70FL01GS"))
    )
    (comp (ref "U10")
      (value "ADS1148QPWRQ1")
      (footprint "eagle-import:TSSOP28")
      (libsource (lib "eagle-import") (part "ADS1148QPWRQ1"))
    )
    (comp (ref "U11")
      (value "ADS1148QPWRQ1")
      (footprint "eagle-import:TSSOP28")
      (libsource (lib "eagle-import") (part "ADS1148QPWRQ1"))
    )
    (comp (ref "U12")
      (value "ADS1148QPWRQ1")
      (footprint "eagle-import:TSSOP28")
      (libsource (lib "eagle-import") (part "ADS1148QPWRQ1"))
    )
    (comp (ref "U13")
      (value "ADR366WAUJZ")
      (footprint "eagle-import:SOT23-5")
      (libsource (lib "eagle-import") (part "ADR36UJZ_"))
    )
    (comp (ref "C16")
      (value "2.2u")
      (footprint "eagle-import:C1206")
      (libsource (lib "eagle-import") (part "rcl_334_C-EUC1206"))
    )
    (comp (ref "C17")
      (value "2.2u")
      (footprint "eagle-import:C1206")
      (libsource (lib "eagle-import") (part "rcl_334_C-EUC1206"))
    )
    (comp (ref "C18")
      (value "100n")
      (footprint "eagle-import:0603-CAP")
      (libsource (lib "eagle-import") (part "CAP0603-CAP"))
    )
    (comp (ref "JP1")
      (value "JUMPER-SMT_2_NC_PASTE_SILK")
      (footprint "eagle-import:SMT-JUMPER_2_NC_PASTE_SILK")
      (libsource (lib "eagle-import") (part "JUMPER-SMT_2_NC_PASTE_SILK"))
    )
    (comp (ref "JP_MS")
      (value "M02PTH")
      (footprint "eagle-import:1X02")
      (libsource (lib "eagle-import") (part "M02PTH"))
    )
    (comp (ref "R9")
      (value "10k")
      (footprint "eagle-import:R0805")
      (libsource (lib "eagle-import") (part "rcl_334_R-EU_R0805"))
    )
    (comp (ref "R26")
      (value "10k")
      (footprint "eagle-import:R0805")
      (libsource (lib "eagle-import") (part "rcl_334_R-EU_R0805"))
    )
    (comp (ref "R27")
      (value "10k")
      (footprint "eagle-import:R0805")
      (libsource (lib "eagle-import") (part "rcl_334_R-EU_R0805"))
    )
    (comp (ref "R28")
      (value "99M")
      (footprint "eagle-import:R0805")
      (libsource (lib "eagle-import") (part "rcl_334_R-EU_R0805"))
    )
    (comp (ref "R29")
      (value "10k")
      (footprint "eagle-import:R0805")
      (libsource (lib "eagle-import") (part "rcl_334_R-EU_R0805"))
    )
    (comp (ref "SJ_MS")
      (value "SOLDERJUMPERNO")
      (footprint "eagle-import:SJ_2S-NO")
      (libsource (lib "eagle-import") (part "SOLDERJUMPERNO"))
    )
    (comp (ref "U9")
      (value "STM32F77XXXLQFP208")
      (footprint "eagle-import:QFP50P3060X3060X385-208")
      (libsource (lib "eagle-import") (part "STM32F77XXXLQFP208"))
    )
    (comp (ref "X1")
      (value "D-SUB9-H5M09RA")
      (footprint "eagle-import:H5M09RA")
      (libsource (lib "eagle-import") (part "D-SUB9-H5M09RA"))
    )
    (comp (ref "X2")
      (value "D-SUB15-H5M15RA")
      (footprint "eagle-import:H5M15RA")
      (fields (field (name "MF") "TYCO ELECTRONICS") (field (name "MPN") "H5M15RA29C"))
      (libsource (lib "eagle-import") (part "D-SUB15-H5M15RA"))
    )
    (comp (ref "X3")
      (value "USBPTH")
      (footprint "eagle-import:USB-B-PTH")
      (libsource (lib "eagle-import") (part "USBPTH"))
    )
    (comp (ref "X_IN_1")
      (value "SMACONNECTOR_EDGE")
      (footprint "eagle-import:SMA_EDGELAUNCH")
      (libsource (lib "eagle-import") (part "SMACONNECTOR_EDGE"))
    )
    (comp (ref "X_IN_2")
      (value "SMACONNECTOR_EDGE")
      (footprint "eagle-import:SMA_EDGELAUNCH")
      (libsource (lib "eagle-import") (part "SMACONNECTOR_EDGE"))
    )
    (comp (ref "X_IN_3")
      (value "SMACONNECTOR_EDGE")
      (footprint "eagle-import:SMA_EDGELAUNCH")
      (libsource (lib "eagle-import") (part "SMACONNECTOR_EDGE"))
    )
    (comp (ref "X_IN_4")
      (value "SMACONNECTOR_EDGE")
      (footprint "eagle-import:SMA_EDGELAUNCH")
      (libsource (lib "eagle-import") (part "SMACONNECTOR_EDGE"))
    )
    (comp (ref "X_IN_5")
      (value "SMACONNECTOR_EDGE")
      (footprint "eagle-import:SMA_EDGELAUNCH")
      (libsource (lib "eagle-import") (part "SMACONNECTOR_EDGE"))
    )
    (comp (ref "X_IN_6")
      (value "SMACONNECTOR_EDGE")
      (footprint "eagle-import:SMA_EDGELAUNCH")
      (libsource (lib "eagle-import") (part "SMACONNECTOR_EDGE"))
    )
    (comp (ref "X_IN_7")
      (value "SMACONNECTOR_EDGE")
      (footprint "eagle-import:SMA_EDGELAUNCH")
      (libsource (lib "eagle-import") (part "SMACONNECTOR_EDGE"))
    )
    (comp (ref "X_IN_8")
      (value "SMACONNECTOR_EDGE")
      (footprint "eagle-import:SMA_EDGELAUNCH")
      (libsource (lib "eagle-import") (part "SMACONNECTOR_EDGE"))
    )
    (comp (ref "X_IN_9")
      (value "SMACONNECTOR_EDGE")
      (footprint "eagle-import:SMA_EDGELAUNCH")
      (libsource (lib "eagle-import") (part "SMACONNECTOR_EDGE"))
    )
    (comp (ref "X_IN_10")
      (value "SMACONNECTOR_EDGE")
      (footprint "eagle-import:SMA_EDGELAUNCH")
      (libsource (lib "eagle-import") (part "SMACONNECTOR_EDGE"))
    )
    (comp (ref "X_IN_11")
      (value "SMACONNECTOR_EDGE")
      (footprint "eagle-import:SMA_EDGELAUNCH")
      (libsource (lib "eagle-import") (part "SMACONNECTOR_EDGE"))
    )
    (comp (ref "X_IN_12")
      (value "SMACONNECTOR_EDGE")
      (footprint "eagle-import:SMA_EDGELAUNCH")
      (libsource (lib "eagle-import") (part "SMACONNECTOR_EDGE"))
    )
    (comp (ref "X_IN_13")
      (value "SMACONNECTOR_EDGE")
      (footprint "eagle-import:SMA_EDGELAUNCH")
      (libsource (lib "eagle-import") (part "SMACONNECTOR_EDGE"))
    )
    (comp (ref "X_IN_14")
      (value "SMACONNECTOR_EDGE")
      (footprint "eagle-import:SMA_EDGELAUNCH")
      (libsource (lib "eagle-import") (part "SMACONNECTOR_EDGE"))
    )
    (comp (ref "X_IN_15")
      (value "SMACONNECTOR_EDGE")
      (footprint "eagle-import:SMA_EDGELAUNCH")
      (libsource (lib "eagle-import") (part "SMACONNECTOR_EDGE"))
    )
    (comp (ref "X_PROG")
      (value "MA07-2")
      (footprint "eagle-import:MA07-2")
      (libsource (lib "eagle-import") (part "MA07-2"))
    )
    (comp (ref "LED1")
      (value "1V9")
      (footprint "eagle-import:CHIP-LED0603")
      (libsource (lib "eagle-import") (part "LEDCHIP-LED0603"))
    )
    (comp (ref "LED2")
      (value "1V9")
      (footprint "eagle-import:CHIP-LED0603")
      (libsource (lib "eagle-import") (part "LEDCHIP-LED0603"))
    )
    (comp (ref "LED3")
      (value "1V9")
      (footprint "eagle-import:CHIP-LED0603")
      (libsource (lib "eagle-import") (part "LEDCHIP-LED0603"))
    )
    (comp (ref "LED4")
      (value "1V9")
      (footprint "eagle-import:CHIP-LED0603")
      (libsource (lib "eagle-import") (part "LEDCHIP-LED0603"))
    )
    (comp (ref "LED5")
      (value "1V9")
      (footprint "eagle-import:CHIP-LED0603")
      (libsource (lib "eagle-import") (part "LEDCHIP-LED0603"))
    )
    (comp (ref "LED6")
      (value "1V9")
      (footprint "eagle-import:CHIP-LED0603")
      (libsource (lib "eagle-import") (part "LEDCHIP-LED0603"))
    )
    (comp (ref "LED7")
      (value "LEDCHIP-LED0603")
      (footprint "eagle-import:CHIP-LED0603")
      (libsource (lib "eagle-import") (part "LEDCHIP-LED0603"))
    )
    (comp (ref "LED8")
      (value "LEDCHIP-LED0603")
      (footprint "eagle-import:CHIP-LED0603")
      (libsource (lib "eagle-import") (part "LEDCHIP-LED0603"))
    )
    (comp (ref "R18")
      (value "680")
      (footprint "eagle-import:R0805")
      (libsource (lib "eagle-import") (part "rcl_334_R-EU_R0805"))
    )
    (comp (ref "R19")
      (value "330")
      (footprint "eagle-import:R0805")
      (libsource (lib "eagle-import") (part "rcl_334_R-EU_R0805"))
    )
    (comp (ref "R20")
      (value "4k7")
      (footprint "eagle-import:R0805")
      (libsource (lib "eagle-import") (part "rcl_334_R-EU_R0805"))
    )
    (comp (ref "R21")
      (value "470")
      (footprint "eagle-import:R0805")
      (libsource (lib "eagle-import") (part "rcl_334_R-EU_R0805"))
    )
    (comp (ref "RN10")
      (value "330")
      (footprint "eagle-import:EXBS8V")
      (libsource (lib "eagle-import") (part "4R-NEXBS8V"))
    )
  )
  (nets
    (net (code "1") (name "3V3") (class "Default")
      (node (ref "C19") (pin "1") (pinfunction "1_1") (pintype "passive"))
      (node (ref "C20") (pin "1") (pinfunction "1_1") (pintype "passive"))
      (node (ref "C22") (pin "1") (pinfunction "1_1") (pintype "passive"))
      (node (ref "C23") (pin "1") (pinfunction "1_1") (pintype "passive"))
      (node (ref "C25") (pin "1") (pinfunction "1_1") (pintype "passive"))
      (node (ref "C26") (pin "1") (pinfunction "1_1") (pintype "passive"))
      (node (ref "C28") (pin "1") (pinfunction "1_1") (pintype "passive"))
      (node (ref "C29") (pin "1") (pinfunction "1_1") (pintype "passive"))
      (node (ref "C30") (pin "1") (pinfunction "1_1") (pintype "passive"))
      (node (ref "C31") (pin "1") (pinfunction "1_1") (pintype "passive"))
      (node (ref "C32") (pin "1") (pinfunction "1_1") (pintype "passive"))
      (node (ref "C33") (pin "1") (pinfunction "1_1") (pintype "passive"))
      (node (ref "C37") (pin "2") (pinfunction "2_2") (pintype "passive"))
      (node (ref "C41") (pin "+") (pinfunction "+_+") (pintype "passive"))
      (node (ref "C45") (pin "1") (pinfunction "1_1") (pintype "passive"))
      (node (ref "C46") (pin "1") (pinfunction "1_1") (pintype "passive"))
      (node (ref "C48") (pin "1") (pinfunction "1_1") (pintype "passive"))
      (node (ref "C49") (pin "1") (pinfunction "1_1") (pintype "passive"))
      (node (ref "IC13") (pin "16") (pinfunction "VCC_16") (pintype "bidirectional"))
      (node (ref "L1") (pin "1") (pinfunction "1_1") (pintype "passive"))
      (node (ref "L2") (pin "1") (pinfunction "1_1") (pintype "passive"))
      (node (ref "L3") (pin "1") (pinfunction "1_1") (pintype "passive"))
      (node (ref "L4") (pin "1") (pinfunction "1_1") (pintype "passive"))
      (node (ref "L5") (pin "1") (pinfunction "1_1") (pintype "passive"))
      (node (ref "R13") (pin "2") (pinfunction "2_2") (pintype "passive"))
      (node (ref "R19") (pin "2") (pinfunction "2_2") (pintype "passive"))
      (node (ref "R26") (pin "2") (pinfunction "2_2") (pintype "passive"))
      (node (ref "R28") (pin "1") (pinfunction "1_1") (pintype "passive"))
      (node (ref "R29") (pin "2") (pinfunction "2_2") (pintype "passive"))
      (node (ref "R9") (pin "2") (pinfunction "2_2") (pintype "passive"))
      (node (ref "RN12") (pin "1") (pinfunction "1_1") (pintype "passive"))
      (node (ref "RN12") (pin "2") (pinfunction "1_2") (pintype "passive"))
      (node (ref "RN12") (pin "3") (pinfunction "1_3") (pintype "passive"))
      (node (ref "RN12") (pin "4") (pinfunction "1_4") (pintype "passive"))
      (node (ref "U10") (pin "1") (pinfunction "DVDD_1") (pintype "bidirectional"))
      (node (ref "U10") (pin "22") (pinfunction "AVDD_22") (pintype "bidirectional"))
      (node (ref "U11") (pin "1") (pinfunction "DVDD_1") (pintype "bidirectional"))
      (node (ref "U11") (pin "22") (pinfunction "AVDD_22") (pintype "bidirectional"))
      (node (ref "U12") (pin "1") (pinfunction "DVDD_1") (pintype "bidirectional"))
      (node (ref "U12") (pin "22") (pinfunction "AVDD_22") (pintype "bidirectional"))
      (node (ref "U3") (pin "1") (pinfunction "DVDD_1") (pintype "bidirectional"))
      (node (ref "U3") (pin "22") (pinfunction "AVDD_22") (pintype "bidirectional"))
      (node (ref "U4") (pin "1") (pinfunction "DVDD_1") (pintype "bidirectional"))
      (node (ref "U4") (pin "22") (pinfunction "AVDD_22") (pintype "bidirectional"))
      (node (ref "U5") (pin "1") (pinfunction "DVDD_1") (pintype "bidirectional"))
      (node (ref "U5") (pin "22") (pinfunction "AVDD_22") (pintype "bidirectional"))
      (node (ref "U6") (pin "1") (pinfunction "OUT_1") (pintype "bidirectional"))
      (node (ref "U6") (pin "2") (pinfunction "SENSE_2") (pintype "bidirectional"))
      (node (ref "U7") (pin "2") (pinfunction "VCC_2") (pintype "bidirectional"))
      (node (ref "U8") (pin "2") (pinfunction "VCC_2") (pintype "bidirectional"))
      (node (ref "U9") (pin "103") (pinfunction "VDD_103") (pintype "bidirectional"))
      (node (ref "U9") (pin "115") (pinfunction "VDD_115") (pintype "bidirectional"))
      (node (ref "U9") (pin "118") (pinfunction "VDDDSI_118") (pintype "bidirectional"))
      (node (ref "U9") (pin "137") (pinfunction "VDDUSB_137") (pintype "bidirectional"))
      (node (ref "U9") (pin "15") (pinfunction "VDD_15") (pintype "bidirectional"))
      (node (ref "U9") (pin "150") (pinfunction "VDD_150") (pintype "bidirectional"))
      (node (ref "U9") (pin "158") (pinfunction "VDD_158") (pintype "bidirectional"))
      (node (ref "U9") (pin "171") (pinfunction "VDDSDMMC_171") (pintype "bidirectional"))
      (node (ref "U9") (pin "185") (pinfunction "VDD_185") (pintype "bidirectional"))
      (node (ref "U9") (pin "204") (pinfunction "VDD_204") (pintype "bidirectional"))
      (node (ref "U9") (pin "26") (pinfunction "VDD_26") (pintype "bidirectional"))
      (node (ref "U9") (pin "39") (pinfunction "VDD_39") (pintype "bidirectional"))
      (node (ref "U9") (pin "42") (pinfunction "VDDA_42") (pintype "bidirectional"))
      (node (ref "U9") (pin "52") (pinfunction "VDD_52") (pintype "bidirectional"))
      (node (ref "U9") (pin "59") (pinfunction "VDD_59") (pintype "bidirectional"))
      (node (ref "U9") (pin "73") (pinfunction "VDD_73") (pintype "bidirectional"))
      (node (ref "U9") (pin "83") (pinfunction "VDD_83") (pintype "bidirectional"))
      (node (ref "U9") (pin "94") (pinfunction "VDD_94") (pintype "bidirectional"))
      (node (ref "X_PROG") (pin "1") (pinfunction "1_1") (pintype "passive"))
    )
    (net (code "2") (name "3V3CAP") (class "Default")
      (node (ref "U9") (pin "6") (pinfunction "VBAT_6") (pintype "bidirectional"))
    )
    (net (code "3") (name "3V3REF") (class "Default")
      (node (ref "C4") (pin "2") (pinfunction "2_2") (pintype "passive"))
      (node (ref "C55") (pin "2") (pinfunction "2_2") (pintype "passive"))
      (node (ref "C9") (pin "2") (pinfunction "2_2") (pintype "passive"))
      (node (ref "R3") (pin "2") (pinfunction "2_2") (pintype "passive"))
      (node (ref "RN1") (pin "1") (pinfunction "1_1") (pintype "passive"))
      (node (ref "RN1") (pin "2") (pinfunction "1_2") (pintype "passive"))
      (node (ref "RN1") (pin "3") (pinfunction "1_3") (pintype "passive"))
      (node (ref "RN1") (pin "4") (pinfunction "1_4") (pintype "passive"))
      (node (ref "RN13") (pin "1") (pinfunction "1_1") (pintype "passive"))
      (node (ref "RN13") (pin "2") (pinfunction "1_2") (pintype "passive"))
      (node (ref "RN13") (pin "3") (pinfunction "1_3") (pintype "passive"))
      (node (ref "RN13") (pin "4") (pinfunction "1_4") (pintype "passive"))
      (node (ref "RN4") (pin "1") (pinfunction "1_1") (pintype "passive"))
      (node (ref "RN4") (pin "2") (pinfunction "1_2") (pintype "passive"))
      (node (ref "RN4") (pin "3") (pinfunction "1_3") (pintype "passive"))
      (node (ref "RN4") (pin "4") (pinfunction "1_4") (pintype "passive"))
      (node (ref "U1") (pin "4") (pinfunction "VOUT_4") (pintype "power_in"))
    )
    (net (code "4") (name "3V3REF2") (class "Default")
      (node (ref "C14") (pin "2") (pinfunction "2_2") (pintype "passive"))
      (node (ref "C58") (pin "2") (pinfunction "2_2") (pintype "passive"))
      (node (ref "R7") (pin "2") (pinfunction "2_2") (pintype "passive"))
      (node (ref "RN16") (pin "1") (pinfunction "1_1") (pintype "passive"))
      (node (ref "RN16") (pin "2") (pinfunction "1_2") (pintype "passive"))
      (node (ref "RN16") (pin "3") (pinfunction "1_3") (pintype "passive"))
      (node (ref "RN16") (pin "4") (pinfunction "1_4") (pintype "passive"))
      (node (ref "RN7") (pin "1") (pinfunction "1_1") (pintype "passive"))
      (node (ref "RN7") (pin "2") (pinfunction "1_2") (pintype "passive"))
      (node (ref "RN7") (pin "3") (pinfunction "1_3") (pintype "passive"))
      (node (ref "RN7") (pin "4") (pinfunction "1_4") (pintype "passive"))
      (node (ref "U2") (pin "4") (pinfunction "VOUT_4") (pintype "power_in"))
    )
    (net (code "5") (name "3V3REF3") (class "Default")
      (node (ref "R24") (pin "2") (pinfunction "2_2") (pintype "passive"))
      (node (ref "U13") (pin "4") (pinfunction "VOUT_4") (pintype "power_in"))
      (node (ref "U9") (pin "41") (pinfunction "VREF+_41") (pintype "bidirectional"))
    )
    (net (code "6") (name "5V") (class "Default")
      (node (ref "C11") (pin "+") (pinfunction "+_+") (pintype "passive"))
      (node (ref "C12") (pin "2") (pinfunction "2_2") (pintype "passive"))
      (node (ref "C35") (pin "2") (pinfunction "2_2") (pintype "passive"))
      (node (ref "C36") (pin "2") (pinfunction "2_2") (pintype "passive"))
      (node (ref "C39") (pin "+") (pinfunction "+_+") (pintype "passive"))
      (node (ref "C40") (pin "+") (pinfunction "+_+") (pintype "passive"))
      (node (ref "C52") (pin "2") (pinfunction "2_2") (pintype "passive"))
      (node (ref "C7") (pin "+") (pinfunction "+_+") (pintype "passive"))
      (node (ref "C8") (pin "2") (pinfunction "2_2") (pintype "passive"))
      (node (ref "IC1") (pin "3") (pinfunction "+VOUT_3") (pintype "passive"))
      (node (ref "R18") (pin "2") (pinfunction "2_2") (pintype "passive"))
      (node (ref "U1") (pin "3") (pinfunction "VIN_3") (pintype "power_in"))
      (node (ref "U13") (pin "3") (pinfunction "VIN_3") (pintype "power_in"))
      (node (ref "U2") (pin "3") (pinfunction "VIN_3") (pintype "power_in"))
      (node (ref "U6") (pin "4") (pinfunction "SHDN_4") (pintype "bidirectional"))
      (node (ref "U6") (pin "5") (pinfunction "IN_5") (pintype "bidirectional"))
      (node (ref "X3") (pin "VBUS") (pinfunction "VBUS_VBUS") (pintype "bidirectional"))
    )
    (net (code "7") (name "5V-28V") (class "Default")
      (node (ref "C43") (pin "1") (pinfunction "1_1") (pintype "passive"))
      (node (ref "IC12") (pin "1") (pinfunction "VOUT_1") (pintype "bidirectional"))
      (node (ref "IC5") (pin "1") (pinfunction "VCC_1") (pintype "power_in"))
      (node (ref "R14") (pin "2") (pinfunction "2_2") (pintype "passive"))
      (node (ref "R16") (pin "1") (pinfunction "1_1") (pintype "passive"))
      (node (ref "R21") (pin "2") (pinfunction "2_2") (pintype "passive"))
    )
    (net (code "8") (name "28V") (class "Default")
      (node (ref "C34") (pin "2") (pinfunction "2_2") (pintype "passive"))
      (node (ref "C38") (pin "+") (pinfunction "+_+") (pintype "passive"))
      (node (ref "C42") (pin "2") (pinfunction "2_2") (pintype "passive"))
      (node (ref "IC1") (pin "1") (pinfunction "+VIN_1") (pintype "input"))
      (node (ref "IC12") (pin "8") (pinfunction "VIN_8") (pintype "bidirectional"))
      (node (ref "R20") (pin "2") (pinfunction "2_2") (pintype "passive"))
      (node (ref "RN11") (pin "1") (pinfunction "1_1") (pintype "passive"))
      (node (ref "RN11") (pin "2") (pinfunction "1_2") (pintype "passive"))
      (node (ref "RN11") (pin "3") (pinfunction "1_3") (pintype "passive"))
      (node (ref "RN11") (pin "4") (pinfunction "1_4") (pintype "passive"))
      (node (ref "X1") (pin "9") (pinfunction "F_9") (pintype "passive"))
      (node (ref "X2") (pin "1") (pinfunction "F_1") (pintype "passive"))
      (node (ref "X2") (pin "9") (pinfunction "F_9") (pintype "passive"))
    )
    (net (code "9") (name "28VGND") (class "Default")
      (node (ref "C34") (pin "1") (pinfunction "1_1") (pintype "passive"))
      (node (ref "C38") (pin "-") (pinfunction "-_-") (pintype "passive"))
      (node (ref "C42") (pin "1") (pinfunction "1_1") (pintype "passive"))
      (node (ref "C43") (pin "2") (pinfunction "2_2") (pintype "passive"))
      (node (ref "C44") (pin "2") (pinfunction "2_2") (pintype "passive"))
      (node (ref "D5") (pin "A") (pinfunction "A_A") (pintype "passive"))
      (node (ref "D6") (pin "A") (pinfunction "A_A") (pintype "passive"))
      (node (ref "IC1") (pin "2") (pinfunction "-VIN_2") (pintype "input"))
      (node (ref "IC12") (pin "2") (pinfunction "GND_2") (pintype "bidirectional"))
      (node (ref "IC12") (pin "3") (pinfunction "GND_3") (pintype "bidirectional"))
      (node (ref "IC12") (pin "6") (pinfunction "GND_6") (pintype "bidirectional"))
      (node (ref "IC12") (pin "7") (pinfunction "GND_7") (pintype "bidirectional"))
      (node (ref "IC5") (pin "4") (pinfunction "GND_4") (pintype "power_in"))
      (node (ref "IC8") (pin "5") (pinfunction "EMT2_5") (pintype "output"))
      (node (ref "LED7") (pin "C") (pinfunction "C_C") (pintype "passive"))
      (node (ref "LED8") (pin "C") (pinfunction "C_C") (pintype "passive"))
      (node (ref "R11") (pin "1") (pinfunction "1_1") (pintype "passive"))
      (node (ref "R17") (pin "1") (pinfunction "1_1") (pintype "passive"))
      (node (ref "X1") (pin "8") (pinfunction "F_8") (pintype "passive"))
      (node (ref "X2") (pin "15") (pinfunction "F_15") (pintype "passive"))
      (node (ref "X2") (pin "8") (pinfunction "F_8") (pintype "passive"))
    )
    (net (code "10") (name "ADC1_DRDY") (class "Default")
      (node (ref "U4") (pin "25") (pinfunction "~{DRDY}_25") (pintype "bidirectional"))
      (node (ref "U9") (pin "65") (pinfunction "PJ0_65") (pintype "bidirectional"))
    )
    (net (code "11") (name "ADC1_RES") (class "Default")
      (node (ref "U4") (pin "4") (pinfunction "~{RESET}_4") (pintype "bidirectional"))
      (node (ref "U9") (pin "68") (pinfunction "PJ3_68") (pintype "bidirectional"))
    )
    (net (code "12") (name "ADC1_START") (class "Default")
      (node (ref "U4") (pin "23") (pinfunction "START_23") (pintype "bidirectional"))
      (node (ref "U9") (pin "67") (pinfunction "PJ2_67") (pintype "bidirectional"))
    )
    (net (code "13") (name "ADC2_DRDY") (class "Default")
      (node (ref "U3") (pin "25") (pinfunction "~{DRDY}_25") (pintype "bidirectional"))
      (node (ref "U9") (pin "47") (pinfunction "PH3_47") (pintype "bidirectional"))
    )
    (net (code "14") (name "ADC2_RES") (class "Default")
      (node (ref "U3") (pin "4") (pinfunction "~{RESET}_4") (pintype "bidirectional"))
      (node (ref "U9") (pin "50") (pinfunction "PA3_50") (pintype "bidirectional"))
    )
    (net (code "15") (name "ADC2_START") (class "Default")
      (node (ref "U3") (pin "23") (pinfunction "START_23") (pintype "bidirectional"))
      (node (ref "U9") (pin "49") (pinfunction "PH5_49") (pintype "bidirectional"))
    )
    (net (code "16") (name "ADC3_DRDY") (class "Default")
      (node (ref "U5") (pin "25") (pinfunction "~{DRDY}_25") (pintype "bidirectional"))
      (node (ref "U9") (pin "71") (pinfunction "PF12_71") (pintype "bidirectional"))
    )
    (net (code "17") (name "ADC3_RES") (class "Default")
      (node (ref "U5") (pin "4") (pinfunction "~{RESET}_4") (pintype "bidirectional"))
      (node (ref "U9") (pin "76") (pinfunction "PF15_76") (pintype "bidirectional"))
    )
    (net (code "18") (name "ADC3_START") (class "Default")
      (node (ref "U5") (pin "23") (pinfunction "START_23") (pintype "bidirectional"))
      (node (ref "U9") (pin "75") (pinfunction "PF14_75") (pintype "bidirectional"))
    )
    (net (code "19") (name "ADC4_DRDY") (class "Default")
      (node (ref "U11") (pin "25") (pinfunction "~{DRDY}_25") (pintype "bidirectional"))
      (node (ref "U9") (pin "32") (pinfunction "PH0_32") (pintype "bidirectional"))
    )
    (net (code "20") (name "ADC4_RES") (class "Default")
      (node (ref "U11") (pin "4") (pinfunction "~{RESET}_4") (pintype "bidirectional"))
      (node (ref "U9") (pin "31") (pinfunction "PF10_31") (pintype "bidirectional"))
    )
    (net (code "21") (name "ADC4_START") (class "Default")
      (node (ref "U11") (pin "23") (pinfunction "START_23") (pintype "bidirectional"))
      (node (ref "U9") (pin "30") (pinfunction "PF9_30") (pintype "bidirectional"))
    )
    (net (code "22") (name "ADC5_DRDY") (class "Default")
      (node (ref "U10") (pin "25") (pinfunction "~{DRDY}_25") (pintype "bidirectional"))
      (node (ref "U9") (pin "44") (pinfunction "PA1_44") (pintype "bidirectional"))
    )
    (net (code "23") (name "ADC5_RES") (class "Default")
      (node (ref "U10") (pin "4") (pinfunction "~{RESET}_4") (pintype "bidirectional"))
      (node (ref "U9") (pin "37") (pinfunction "PC2_37") (pintype "bidirectional"))
    )
    (net (code "24") (name "ADC5_START") (class "Default")
      (node (ref "U10") (pin "23") (pinfunction "START_23") (pintype "bidirectional"))
      (node (ref "U9") (pin "35") (pinfunction "PC0_35") (pintype "bidirectional"))
    )
    (net (code "25") (name "ADC6_DRDY") (class "Default")
      (node (ref "U12") (pin "25") (pinfunction "~{DRDY}_25") (pintype "bidirectional"))
      (node (ref "U9") (pin "45") (pinfunction "PA2_45") (pintype "bidirectional"))
    )
    (net (code "26") (name "ADC6_RES") (class "Default")
      (node (ref "U12") (pin "4") (pinfunction "~{RESET}_4") (pintype "bidirectional"))
      (node (ref "U9") (pin "33") (pinfunction "PH1_33") (pintype "bidirectional"))
    )
    (net (code "27") (name "ADC6_START") (class "Default")
      (node (ref "U12") (pin "23") (pinfunction "START_23") (pintype "bidirectional"))
      (node (ref "U9") (pin "38") (pinfunction "PC3_38") (pintype "bidirectional"))
    )
    (net (code "28") (name "DAPI_N") (class "Default")
      (node (ref "D1") (pin "C") (pinfunction "C_C") (pintype "passive"))
      (node (ref "IC13") (pin "6") (pinfunction "D-_6") (pintype "bidirectional"))
      (node (ref "X3") (pin "D-") (pinfunction "D-_D-") (pintype "bidirectional"))
    )
    (net (code "29") (name "DAPI_P") (class "Default")
      (node (ref "D2") (pin "C") (pinfunction "C_C") (pintype "passive"))
      (node (ref "IC13") (pin "5") (pinfunction "D+_5") (pintype "bidirectional"))
      (node (ref "X3") (pin "D+") (pinfunction "D+_D+") (pintype "bidirectional"))
    )
    (net (code "30") (name "DAPI_RX") (class "Default")
      (node (ref "D4") (pin "C") (pinfunction "C_C") (pintype "passive"))
      (node (ref "IC13") (pin "2") (pinfunction "TX_2") (pintype "bidirectional"))
      (node (ref "U9") (pin "11") (pinfunction "PI9_11") (pintype "bidirectional"))
    )
    (net (code "31") (name "DAPI_TX") (class "Default")
      (node (ref "D3") (pin "C") (pinfunction "C_C") (pintype "passive"))
      (node (ref "IC13") (pin "3") (pinfunction "RX_3") (pintype "bidirectional"))
      (node (ref "U9") (pin "43") (pinfunction "PA0_43") (pintype "bidirectional"))
    )
    (net (code "32") (name "EXP_IN") (class "Default")
      (node (ref "D5") (pin "C") (pinfunction "C_C") (pintype "passive"))
      (node (ref "IC5") (pin "2") (pinfunction "RO_2") (pintype "output"))
      (node (ref "IC8") (pin "1") (pinfunction "A1_1") (pintype "bidirectional"))
    )
    (net (code "33") (name "EXP_IN_N") (class "Default")
      (node (ref "IC5") (pin "7") (pinfunction "B_7") (pintype "input"))
      (node (ref "R15") (pin "1") (pinfunction "1_1") (pintype "passive"))
      (node (ref "R17") (pin "2") (pinfunction "2_2") (pintype "passive"))
      (node (ref "X2") (pin "14") (pinfunction "F_14") (pintype "passive"))
    )
    (net (code "34") (name "EXP_IN_OPT") (class "Default")
      (node (ref "D10") (pin "C") (pinfunction "C_C") (pintype "passive"))
      (node (ref "IC8") (pin "8") (pinfunction "COL1_8") (pintype "input"))
      (node (ref "R13") (pin "1") (pinfunction "1_1") (pintype "passive"))
      (node (ref "U9") (pin "200") (pinfunction "PE0_200") (pintype "bidirectional"))
    )
    (net (code "35") (name "EXP_IN_P") (class "Default")
      (node (ref "IC5") (pin "8") (pinfunction "A_8") (pintype "input"))
      (node (ref "R10") (pin "2") (pinfunction "2_2") (pintype "passive"))
      (node (ref "R16") (pin "2") (pinfunction "2_2") (pintype "passive"))
      (node (ref "X2") (pin "13") (pinfunction "F_13") (pintype "passive"))
    )
    (net (code "36") (name "EXP_OUT") (class "Default")
      (node (ref "D6") (pin "C") (pinfunction "C_C") (pintype "passive"))
      (node (ref "IC5") (pin "3") (pinfunction "DI_3") (pintype "input"))
      (node (ref "IC8") (pin "6") (pinfunction "COL2_6") (pintype "input"))
      (node (ref "R14") (pin "1") (pinfunction "1_1") (pintype "passive"))
    )
    (net (code "37") (name "EXP_OUT_N") (class "Default")
      (node (ref "IC5") (pin "6") (pinfunction "Z_6") (pintype "output"))
      (node (ref "X2") (pin "7") (pinfunction "F_7") (pintype "passive"))
    )
    (net (code "38") (name "EXP_OUT_OPT") (class "Default")
      (node (ref "IC8") (pin "3") (pinfunction "A2_3") (pintype "bidirectional"))
      (node (ref "U9") (pin "201") (pinfunction "PE1_201") (pintype "bidirectional"))
    )
    (net (code "39") (name "EXP_OUT_P") (class "Default")
      (node (ref "IC5") (pin "5") (pinfunction "Y_5") (pintype "output"))
      (node (ref "X2") (pin "6") (pinfunction "F_6") (pintype "passive"))
    )
    (net (code "40") (name "FL_1_CS1") (class "Default")
      (node (ref "U7") (pin "7") (pinfunction "CS1_7") (pintype "bidirectional"))
      (node (ref "U9") (pin "104") (pinfunction "PB12_104") (pintype "bidirectional"))
    )
    (net (code "41") (name "FL_1_CS2") (class "Default")
      (node (ref "U7") (pin "6") (pinfunction "CS2_6") (pintype "bidirectional"))
      (node (ref "U9") (pin "102") (pinfunction "PH12_102") (pintype "bidirectional"))
    )
    (net (code "42") (name "FL_1_HLD") (class "Default")
      (node (ref "U7") (pin "1") (pinfunction "HOLD_1") (pintype "bidirectional"))
      (node (ref "U9") (pin "99") (pinfunction "PH9_99") (pintype "bidirectional"))
    )
    (net (code "43") (name "FL_1_RES") (class "Default")
      (node (ref "U7") (pin "3") (pinfunction "RESET_3") (pintype "bidirectional"))
      (node (ref "U9") (pin "101") (pinfunction "PH11_101") (pintype "bidirectional"))
    )
    (net (code "44") (name "FL_1_WP") (class "Default")
      (node (ref "U7") (pin "9") (pinfunction "WP_9") (pintype "bidirectional"))
      (node (ref "U9") (pin "100") (pinfunction "PH10_100") (pintype "bidirectional"))
    )
    (net (code "45") (name "FL_2_CS1") (class "Default")
      (node (ref "U8") (pin "7") (pinfunction "CS1_7") (pintype "bidirectional"))
      (node (ref "U9") (pin "112") (pinfunction "PD12_112") (pintype "bidirectional"))
    )
    (net (code "46") (name "FL_2_CS2") (class "Default")
      (node (ref "U8") (pin "6") (pinfunction "CS2_6") (pintype "bidirectional"))
      (node (ref "U9") (pin "111") (pinfunction "PD11_111") (pintype "bidirectional"))
    )
    (net (code "47") (name "FL_2_HLD") (class "Default")
      (node (ref "U8") (pin "1") (pinfunction "HOLD_1") (pintype "bidirectional"))
      (node (ref "U9") (pin "109") (pinfunction "PD9_109") (pintype "bidirectional"))
    )
    (net (code "48") (name "FL_2_RES") (class "Default")
      (node (ref "U8") (pin "3") (pinfunction "RESET_3") (pintype "bidirectional"))
      (node (ref "U9") (pin "110") (pinfunction "PD10_110") (pintype "bidirectional"))
    )
    (net (code "49") (name "FL_2_WP") (class "Default")
      (node (ref "U8") (pin "9") (pinfunction "WP_9") (pintype "bidirectional"))
      (node (ref "U9") (pin "108") (pinfunction "PD8_108") (pintype "bidirectional"))
    )
    (net (code "50") (name "GND") (class "Default")
      (node (ref "C1") (pin "2") (pinfunction "2_2") (pintype "passive"))
      (node (ref "C10") (pin "-") (pinfunction "-_-") (pintype "passive"))
      (node (ref "C11") (pin "-") (pinfunction "-_-") (pintype "passive"))
      (node (ref "C12") (pin "1") (pinfunction "1_1") (pintype "passive"))
      (node (ref "C13") (pin "1") (pinfunction "1_1") (pintype "passive"))
      (node (ref "C14") (pin "1") (pinfunction "1_1") (pintype "passive"))
      (node (ref "C15") (pin "-") (pinfunction "-_-") (pintype "passive"))
      (node (ref "C16") (pin "1") (pinfunction "1_1") (pintype "passive"))
      (node (ref "C17") (pin "1") (pinfunction "1_1") (pintype "passive"))
      (node (ref "C18") (pin "2") (pinfunction "2_2") (pintype "passive"))
      (node (ref "C19") (pin "2") (pinfunction "2_2") (pintype "passive"))
      (node (ref "C2") (pin "2") (pinfunction "2_2") (pintype "passive"))
      (node (ref "C20") (pin "2") (pinfunction "2_2") (pintype "passive"))
      (node (ref "C21") (pin "2") (pinfunction "2_2") (pintype "passive"))
      (node (ref "C22") (pin "2") (pinfunction "2_2") (pintype "passive"))
      (node (ref "C23") (pin "2") (pinfunction "2_2") (pintype "passive"))
      (node (ref "C24") (pin "2") (pinfunction "2_2") (pintype "passive"))
      (node (ref "C25") (pin "2") (pinfunction "2_2") (pintype "passive"))
      (node (ref "C26") (pin "2") (pinfunction "2_2") (pintype "passive"))
      (node (ref "C27") (pin "2") (pinfunction "2_2") (pintype "passive"))
      (node (ref "C28") (pin "2") (pinfunction "2_2") (pintype "passive"))
      (node (ref "C29") (pin "2") (pinfunction "2_2") (pintype "passive"))
      (node (ref "C3") (pin "1") (pinfunction "1_1") (pintype "passive"))
      (node (ref "C30") (pin "2") (pinfunction "2_2") (pintype "passive"))
      (node (ref "C31") (pin "2") (pinfunction "2_2") (pintype "passive"))
      (node (ref "C32") (pin "2") (pinfunction "2_2") (pintype "passive"))
      (node (ref "C33") (pin "2") (pinfunction "2_2") (pintype "passive"))
      (node (ref "C35") (pin "1") (pinfunction "1_1") (pintype "passive"))
      (node (ref "C36") (pin "1") (pinfunction "1_1") (pintype "passive"))
      (node (ref "C37") (pin "1") (pinfunction "1_1") (pintype "passive"))
      (node (ref "C39") (pin "-") (pinfunction "-_-") (pintype "passive"))
      (node (ref "C4") (pin "1") (pinfunction "1_1") (pintype "passive"))
      (node (ref "C40") (pin "-") (pinfunction "-_-") (pintype "passive"))
      (node (ref "C41") (pin "-") (pinfunction "-_-") (pintype "passive"))
      (node (ref "C45") (pin "2") (pinfunction "2_2") (pintype "passive"))
      (node (ref "C46") (pin "2") (pinfunction "2_2") (pintype "passive"))
      (node (ref "C47") (pin "2") (pinfunction "2_2") (pintype "passive"))
      (node (ref "C48") (pin "2") (pinfunction "2_2") (pintype "passive"))
      (node (ref "C49") (pin "2") (pinfunction "2_2") (pintype "passive"))
      (node (ref "C5") (pin "-") (pinfunction "-_-") (pintype "passive"))
      (node (ref "C50") (pin "2") (pinfunction "2_2") (pintype "passive"))
      (node (ref "C52") (pin "1") (pinfunction "1_1") (pintype "passive"))
      (node (ref "C53") (pin "2") (pinfunction "2_2") (pintype "passive"))
      (node (ref "C54") (pin "1") (pinfunction "1_1") (pintype "passive"))
      (node (ref "C55") (pin "1") (pinfunction "1_1") (pintype "passive"))
      (node (ref "C57") (pin "1") (pinfunction "1_1") (pintype "passive"))
      (node (ref "C58") (pin "1") (pinfunction "1_1") (pintype "passive"))
      (node (ref "C6") (pin "1") (pinfunction "1_1") (pintype "passive"))
      (node (ref "C7") (pin "-") (pinfunction "-_-") (pintype "passive"))
      (node (ref "C8") (pin "1") (pinfunction "1_1") (pintype "passive"))
      (node (ref "C9") (pin "1") (pinfunction "1_1") (pintype "passive"))
      (node (ref "D1") (pin "A") (pinfunction "A_A") (pintype "passive"))
      (node (ref "D10") (pin "A") (pinfunction "A_A") (pintype "passive"))
      (node (ref "D11") (pin "A") (pinfunction "A_A") (pintype "passive"))
      (node (ref "D12") (pin "A") (pinfunction "A_A") (pintype "passive"))
      (node (ref "D2") (pin "A") (pinfunction "A_A") (pintype "passive"))
      (node (ref "D3") (pin "A") (pinfunction "A_A") (pintype "passive"))
      (node (ref "D4") (pin "A") (pinfunction "A_A") (pintype "passive"))
      (node (ref "D7") (pin "A") (pinfunction "A_A") (pintype "passive"))
      (node (ref "D8") (pin "A") (pinfunction "A_A") (pintype "passive"))
      (node (ref "D9") (pin "A") (pinfunction "A_A") (pintype "passive"))
      (node (ref "IC1") (pin "5") (pinfunction "-VOUT_5") (pintype "passive"))
      (node (ref "IC10") (pin "11") (pinfunction "V-_11") (pintype "power_in"))
      (node (ref "IC13") (pin "1") (pinfunction "GND_1") (pintype "bidirectional"))
      (node (ref "IC2") (pin "11") (pinfunction "V-_11") (pintype "power_in"))
      (node (ref "IC3") (pin "11") (pinfunction "V-_11") (pintype "power_in"))
      (node (ref "IC4") (pin "11") (pinfunction "V-_11") (pintype "power_in"))
      (node (ref "IC6") (pin "5") (pinfunction "EMT2_5") (pintype "output"))
      (node (ref "IC6") (pin "7") (pinfunction "EMT1_7") (pintype "output"))
      (node (ref "IC7") (pin "5") (pinfunction "EMT2_5") (pintype "output"))
      (node (ref "IC7") (pin "7") (pinfunction "EMT1_7") (pintype "output"))
      (node (ref "IC8") (pin "7") (pinfunction "EMT1_7") (pintype "output"))
      (node (ref "IC9") (pin "11") (pinfunction "V-_11") (pintype "power_in"))
      (node (ref "JP_MS") (pin "1") (pinfunction "1_1") (pintype "passive"))
      (node (ref "LED1") (pin "C") (pinfunction "C_C") (pintype "passive"))
      (node (ref "LED2") (pin "C") (pinfunction "C_C") (pintype "passive"))
      (node (ref "LED3") (pin "C") (pinfunction "C_C") (pintype "passive"))
      (node (ref "LED4") (pin "C") (pinfunction "C_C") (pintype "passive"))
      (node (ref "LED5") (pin "C") (pinfunction "C_C") (pintype "passive"))
      (node (ref "LED6") (pin "C") (pinfunction "C_C") (pintype "passive"))
      (node (ref "R12") (pin "1") (pinfunction "1_1") (pintype "passive"))
      (node (ref "R2") (pin "1") (pinfunction "1_1") (pintype "passive"))
      (node (ref "R23") (pin "1") (pinfunction "1_1") (pintype "passive"))
      (node (ref "R27") (pin "2") (pinfunction "2_2") (pintype "passive"))
      (node (ref "R6") (pin "1") (pinfunction "1_1") (pintype "passive"))
      (node (ref "RN14") (pin "5") (pinfunction "2_5") (pintype "passive"))
      (node (ref "RN14") (pin "6") (pinfunction "2_6") (pintype "passive"))
      (node (ref "RN14") (pin "7") (pinfunction "2_7") (pintype "passive"))
      (node (ref "RN14") (pin "8") (pinfunction "2_8") (pintype "passive"))
      (node (ref "RN17") (pin "5") (pinfunction "2_5") (pintype "passive"))
      (node (ref "RN17") (pin "6") (pinfunction "2_6") (pintype "passive"))
      (node (ref "RN17") (pin "7") (pinfunction "2_7") (pintype "passive"))
      (node (ref "RN17") (pin "8") (pinfunction "2_8") (pintype "passive"))
      (node (ref "RN2") (pin "5") (pinfunction "2_5") (pintype "passive"))
      (node (ref "RN2") (pin "6") (pinfunction "2_6") (pintype "passive"))
      (node (ref "RN2") (pin "7") (pinfunction "2_7") (pintype "passive"))
      (node (ref "RN2") (pin "8") (pinfunction "2_8") (pintype "passive"))
      (node (ref "RN5") (pin "5") (pinfunction "2_5") (pintype "passive"))
      (node (ref "RN5") (pin "6") (pinfunction "2_6") (pintype "passive"))
      (node (ref "RN5") (pin "7") (pinfunction "2_7") (pintype "passive"))
      (node (ref "RN5") (pin "8") (pinfunction "2_8") (pintype "passive"))
      (node (ref "RN8") (pin "5") (pinfunction "2_5") (pintype "passive"))
      (node (ref "RN8") (pin "6") (pinfunction "2_6") (pintype "passive"))
      (node (ref "RN8") (pin "7") (pinfunction "2_7") (pintype "passive"))
      (node (ref "RN8") (pin "8") (pinfunction "2_8") (pintype "passive"))
      (node (ref "SJ_MS") (pin "1") (pinfunction "1_1") (pintype "passive"))
      (node (ref "U1") (pin "2") (pinfunction "GND_2") (pintype "power_in"))
      (node (ref "U10") (pin "10") (pinfunction "VREFCOM_10") (pintype "bidirectional"))
      (node (ref "U10") (pin "2") (pinfunction "DGND/DSS_2") (pintype "bidirectional"))
      (node (ref "U10") (pin "21") (pinfunction "AVSS_21") (pintype "bidirectional"))
      (node (ref "U10") (pin "3") (pinfunction "CLK_3") (pintype "bidirectional"))
      (node (ref "U11") (pin "10") (pinfunction "VREFCOM_10") (pintype "bidirectional"))
      (node (ref "U11") (pin "2") (pinfunction "DGND/DSS_2") (pintype "bidirectional"))
      (node (ref "U11") (pin "21") (pinfunction "AVSS_21") (pintype "bidirectional"))
      (node (ref "U11") (pin "3") (pinfunction "CLK_3") (pintype "bidirectional"))
      (node (ref "U12") (pin "10") (pinfunction "VREFCOM_10") (pintype "bidirectional"))
      (node (ref "U12") (pin "2") (pinfunction "DGND/DSS_2") (pintype "bidirectional"))
      (node (ref "U12") (pin "21") (pinfunction "AVSS_21") (pintype "bidirectional"))
      (node (ref "U12") (pin "3") (pinfunction "CLK_3") (pintype "bidirectional"))
      (node (ref "U13") (pin "2") (pinfunction "GND_2") (pintype "power_in"))
      (node (ref "U2") (pin "2") (pinfunction "GND_2") (pintype "power_in"))
      (node (ref "U3") (pin "10") (pinfunction "VREFCOM_10") (pintype "bidirectional"))
      (node (ref "U3") (pin "2") (pinfunction "DGND/DSS_2") (pintype "bidirectional"))
      (node (ref "U3") (pin "21") (pinfunction "AVSS_21") (pintype "bidirectional"))
      (node (ref "U3") (pin "3") (pinfunction "CLK_3") (pintype "bidirectional"))
      (node (ref "U4") (pin "10") (pinfunction "VREFCOM_10") (pintype "bidirectional"))
      (node (ref "U4") (pin "2") (pinfunction "DGND/DSS_2") (pintype "bidirectional"))
      (node (ref "U4") (pin "21") (pinfunction "AVSS_21") (pintype "bidirectional"))
      (node (ref "U4") (pin "3") (pinfunction "CLK_3") (pintype "bidirectional"))
      (node (ref "U5") (pin "10") (pinfunction "VREFCOM_10") (pintype "bidirectional"))
      (node (ref "U5") (pin "2") (pinfunction "DGND/DSS_2") (pintype "bidirectional"))
      (node (ref "U5") (pin "21") (pinfunction "AVSS_21") (pintype "bidirectional"))
      (node (ref "U5") (pin "3") (pinfunction "CLK_3") (pintype "bidirectional"))
      (node (ref "U6") (pin "3") (pinfunction "GND_3") (pintype "bidirectional"))
      (node (ref "U6") (pin "6") (pinfunction "GND_6") (pintype "bidirectional"))
      (node (ref "U7") (pin "10") (pinfunction "VSS_10") (pintype "bidirectional"))
      (node (ref "U8") (pin "10") (pinfunction "VSS_10") (pintype "bidirectional"))
      (node (ref "U9") (pin "114") (pinfunction "VSS_114") (pintype "bidirectional"))
      (node (ref "U9") (pin "122") (pinfunction "VSSDSI_122") (pintype "bidirectional"))
      (node (ref "U9") (pin "128") (pinfunction "VSSDSI2_128") (pintype "bidirectional"))
      (node (ref "U9") (pin "136") (pinfunction "VSS_136") (pintype "bidirectional"))
      (node (ref "U9") (pin "14") (pinfunction "VSS_14") (pintype "bidirectional"))
      (node (ref "U9") (pin "149") (pinfunction "VSS_149") (pintype "bidirectional"))
      (node (ref "U9") (pin "170") (pinfunction "VSS_170") (pintype "bidirectional"))
      (node (ref "U9") (pin "184") (pinfunction "VSS_184") (pintype "bidirectional"))
      (node (ref "U9") (pin "202") (pinfunction "VSS_202") (pintype "bidirectional"))
      (node (ref "U9") (pin "25") (pinfunction "VSS_25") (pintype "bidirectional"))
      (node (ref "U9") (pin "40") (pinfunction "VSSA_40") (pintype "bidirectional"))
      (node (ref "U9") (pin "51") (pinfunction "VSS_51") (pintype "bidirectional"))
      (node (ref "U9") (pin "60") (pinfunction "VSS_60") (pintype "bidirectional"))
      (node (ref "U9") (pin "72") (pinfunction "VSS_72") (pintype "bidirectional"))
      (node (ref "U9") (pin "82") (pinfunction "VSS_82") (pintype "bidirectional"))
      (node (ref "U9") (pin "93") (pinfunction "VSS_93") (pintype "bidirectional"))
      (node (ref "X1") (pin "1") (pinfunction "F_1") (pintype "passive"))
      (node (ref "X3") (pin "GND") (pinfunction "GND_GND") (pintype "bidirectional"))
      (node (ref "X_IN_1") (pin "GND@1") (pinfunction "GND4_GND@1") (pintype "power_in"))
      (node (ref "X_IN_1") (pin "GND@2") (pinfunction "GND3_GND@2") (pintype "power_in"))
      (node (ref "X_IN_1") (pin "GND@3") (pinfunction "GND2_GND@3") (pintype "power_in"))
      (node (ref "X_IN_1") (pin "GND@4") (pinfunction "GND1_GND@4") (pintype "power_in"))
      (node (ref "X_IN_10") (pin "GND@1") (pinfunction "GND4_GND@1") (pintype "power_in"))
      (node (ref "X_IN_10") (pin "GND@2") (pinfunction "GND3_GND@2") (pintype "power_in"))
      (node (ref "X_IN_10") (pin "GND@3") (pinfunction "GND2_GND@3") (pintype "power_in"))
      (node (ref "X_IN_10") (pin "GND@4") (pinfunction "GND1_GND@4") (pintype "power_in"))
      (node (ref "X_IN_11") (pin "GND@1") (pinfunction "GND4_GND@1") (pintype "power_in"))
      (node (ref "X_IN_11") (pin "GND@2") (pinfunction "GND3_GND@2") (pintype "power_in"))
      (node (ref "X_IN_11") (pin "GND@3") (pinfunction "GND2_GND@3") (pintype "power_in"))
      (node (ref "X_IN_11") (pin "GND@4") (pinfunction "GND1_GND@4") (pintype "power_in"))
      (node (ref "X_IN_12") (pin "GND@1") (pinfunction "GND4_GND@1") (pintype "power_in"))
      (node (ref "X_IN_12") (pin "GND@2") (pinfunction "GND3_GND@2") (pintype "power_in"))
      (node (ref "X_IN_12") (pin "GND@3") (pinfunction "GND2_GND@3") (pintype "power_in"))
      (node (ref "X_IN_12") (pin "GND@4") (pinfunction "GND1_GND@4") (pintype "power_in"))
      (node (ref "X_IN_13") (pin "GND@1") (pinfunction "GND4_GND@1") (pintype "power_in"))
      (node (ref "X_IN_13") (pin "GND@2") (pinfunction "GND3_GND@2") (pintype "power_in"))
      (node (ref "X_IN_13") (pin "GND@3") (pinfunction "GND2_GND@3") (pintype "power_in"))
      (node (ref "X_IN_13") (pin "GND@4") (pinfunction "GND1_GND@4") (pintype "power_in"))
      (node (ref "X_IN_14") (pin "GND@1") (pinfunction "GND4_GND@1") (pintype "power_in"))
      (node (ref "X_IN_14") (pin "GND@2") (pinfunction "GND3_GND@2") (pintype "power_in"))
      (node (ref "X_IN_14") (pin "GND@3") (pinfunction "GND2_GND@3") (pintype "power_in"))
      (node (ref "X_IN_14") (pin "GND@4") (pinfunction "GND1_GND@4") (pintype "power_in"))
      (node (ref "X_IN_15") (pin "GND@1") (pinfunction "GND4_GND@1") (pintype "power_in"))
      (node (ref "X_IN_15") (pin "GND@2") (pinfunction "GND3_GND@2") (pintype "power_in"))
      (node (ref "X_IN_15") (pin "GND@3") (pinfunction "GND2_GND@3") (pintype "power_in"))
      (node (ref "X_IN_15") (pin "GND@4") (pinfunction "GND1_GND@4") (pintype "power_in"))
      (node (ref "X_IN_2") (pin "GND@1") (pinfunction "GND4_GND@1") (pintype "power_in"))
      (node (ref "X_IN_2") (pin "GND@2") (pinfunction "GND3_GND@2") (pintype "power_in"))
      (node (ref "X_IN_2") (pin "GND@3") (pinfunction "GND2_GND@3") (pintype "power_in"))
      (node (ref "X_IN_2") (pin "GND@4") (pinfunction "GND1_GND@4") (pintype "power_in"))
      (node (ref "X_IN_3") (pin "GND@1") (pinfunction "GND4_GND@1") (pintype "power_in"))
      (node (ref "X_IN_3") (pin "GND@2") (pinfunction "GND3_GND@2") (pintype "power_in"))
      (node (ref "X_IN_3") (pin "GND@3") (pinfunction "GND2_GND@3") (pintype "power_in"))
      (node (ref "X_IN_3") (pin "GND@4") (pinfunction "GND1_GND@4") (pintype "power_in"))
      (node (ref "X_IN_4") (pin "GND@1") (pinfunction "GND4_GND@1") (pintype "power_in"))
      (node (ref "X_IN_4") (pin "GND@2") (pinfunction "GND3_GND@2") (pintype "power_in"))
      (node (ref "X_IN_4") (pin "GND@3") (pinfunction "GND2_GND@3") (pintype "power_in"))
      (node (ref "X_IN_4") (pin "GND@4") (pinfunction "GND1_GND@4") (pintype "power_in"))
      (node (ref "X_IN_5") (pin "GND@1") (pinfunction "GND4_GND@1") (pintype "power_in"))
      (node (ref "X_IN_5") (pin "GND@2") (pinfunction "GND3_GND@2") (pintype "power_in"))
      (node (ref "X_IN_5") (pin "GND@3") (pinfunction "GND2_GND@3") (pintype "power_in"))
      (node (ref "X_IN_5") (pin "GND@4") (pinfunction "GND1_GND@4") (pintype "power_in"))
      (node (ref "X_IN_6") (pin "GND@1") (pinfunction "GND4_GND@1") (pintype "power_in"))
      (node (ref "X_IN_6") (pin "GND@2") (pinfunction "GND3_GND@2") (pintype "power_in"))
      (node (ref "X_IN_6") (pin "GND@3") (pinfunction "GND2_GND@3") (pintype "power_in"))
      (node (ref "X_IN_6") (pin "GND@4") (pinfunction "GND1_GND@4") (pintype "power_in"))
      (node (ref "X_IN_7") (pin "GND@1") (pinfunction "GND4_GND@1") (pintype "power_in"))
      (node (ref "X_IN_7") (pin "GND@2") (pinfunction "GND3_GND@2") (pintype "power_in"))
      (node (ref "X_IN_7") (pin "GND@3") (pinfunction "GND2_GND@3") (pintype "power_in"))
      (node (ref "X_IN_7") (pin "GND@4") (pinfunction "GND1_GND@4") (pintype "power_in"))
      (node (ref "X_IN_8") (pin "GND@1") (pinfunction "GND4_GND@1") (pintype "power_in"))
      (node (ref "X_IN_8") (pin "GND@2") (pinfunction "GND3_GND@2") (pintype "power_in"))
      (node (ref "X_IN_8") (pin "GND@3") (pinfunction "GND2_GND@3") (pintype "power_in"))
      (node (ref "X_IN_8") (pin "GND@4") (pinfunction "GND1_GND@4") (pintype "power_in"))
      (node (ref "X_IN_9") (pin "GND@1") (pinfunction "GND4_GND@1") (pintype "power_in"))
      (node (ref "X_IN_9") (pin "GND@2") (pinfunction "GND3_GND@2") (pintype "power_in"))
      (node (ref "X_IN_9") (pin "GND@3") (pinfunction "GND2_GND@3") (pintype "power_in"))
      (node (ref "X_IN_9") (pin "GND@4") (pinfunction "GND1_GND@4") (pintype "power_in"))
      (node (ref "X_PROG") (pin "10") (pinfunction "10_10") (pintype "passive"))
      (node (ref "X_PROG") (pin "14") (pinfunction "14_14") (pintype "passive"))
      (node (ref "X_PROG") (pin "2") (pinfunction "2_2") (pintype "passive"))
      (node (ref "X_PROG") (pin "4") (pinfunction "4_4") (pintype "passive"))
      (node (ref "X_PROG") (pin "6") (pinfunction "6_6") (pintype "passive"))
      (node (ref "X_PROG") (pin "8") (pinfunction "8_8") (pintype "passive"))
    )
    (net (code "51") (name "INTERSPU_RX") (class "Default")
      (node (ref "D11") (pin "C") (pinfunction "C_C") (pintype "passive"))
      (node (ref "U9") (pin "166") (pinfunction "PD2_166") (pintype "bidirectional"))
      (node (ref "X1") (pin "4") (pinfunction "F_4") (pintype "passive"))
    )
    (net (code "52") (name "INTERSPU_TX") (class "Default")
      (node (ref "D12") (pin "C") (pinfunction "C_C") (pintype "passive"))
      (node (ref "U9") (pin "163") (pinfunction "PC12_163") (pintype "bidirectional"))
      (node (ref "X1") (pin "3") (pinfunction "F_3") (pintype "passive"))
    )
    (net (code "53") (name "IN_DMS_1") (class "Default")
      (node (ref "IC2") (pin "2") (pinfunction "-IN_2") (pintype "input"))
      (node (ref "RN3") (pin "4") (pinfunction "1_4") (pintype "passive"))
      (node (ref "X_IN_1") (pin "P") (pinfunction "ANT_P") (pintype "bidirectional"))
    )
    (net (code "54") (name "IN_DMS_2") (class "Default")
      (node (ref "IC2") (pin "6") (pinfunction "-IN_6") (pintype "input"))
      (node (ref "RN3") (pin "3") (pinfunction "1_3") (pintype "passive"))
      (node (ref "X_IN_2") (pin "P") (pinfunction "ANT_P") (pintype "bidirectional"))
    )
    (net (code "55") (name "IN_DMS_3") (class "Default")
      (node (ref "IC2") (pin "9") (pinfunction "-IN_9") (pintype "input"))
      (node (ref "RN3") (pin "2") (pinfunction "1_2") (pintype "passive"))
      (node (ref "X_IN_3") (pin "P") (pinfunction "ANT_P") (pintype "bidirectional"))
    )
    (net (code "56") (name "IN_DMS_4") (class "Default")
      (node (ref "IC2") (pin "13") (pinfunction "-IN_13") (pintype "input"))
      (node (ref "RN3") (pin "1") (pinfunction "1_1") (pintype "passive"))
      (node (ref "X_IN_4") (pin "P") (pinfunction "ANT_P") (pintype "bidirectional"))
    )
    (net (code "57") (name "IN_DMS_5") (class "Default")
      (node (ref "IC3") (pin "2") (pinfunction "-IN_2") (pintype "input"))
      (node (ref "RN6") (pin "4") (pinfunction "1_4") (pintype "passive"))
      (node (ref "X_IN_5") (pin "P") (pinfunction "ANT_P") (pintype "bidirectional"))
    )
    (net (code "58") (name "IN_DMS_6") (class "Default")
      (node (ref "IC3") (pin "6") (pinfunction "-IN_6") (pintype "input"))
      (node (ref "RN6") (pin "3") (pinfunction "1_3") (pintype "passive"))
      (node (ref "X_IN_6") (pin "P") (pinfunction "ANT_P") (pintype "bidirectional"))
    )
    (net (code "59") (name "IN_DMS_7") (class "Default")
      (node (ref "IC9") (pin "2") (pinfunction "-IN_2") (pintype "input"))
      (node (ref "RN15") (pin "4") (pinfunction "1_4") (pintype "passive"))
      (node (ref "X_IN_10") (pin "P") (pinfunction "ANT_P") (pintype "bidirectional"))
    )
    (net (code "60") (name "IN_DMS_7_NC") (class "Default")
      (node (ref "IC3") (pin "9") (pinfunction "-IN_9") (pintype "input"))
      (node (ref "RN6") (pin "2") (pinfunction "1_2") (pintype "passive"))
    )
    (net (code "61") (name "IN_DMS_8") (class "Default")
      (node (ref "IC9") (pin "6") (pinfunction "-IN_6") (pintype "input"))
      (node (ref "RN15") (pin "3") (pinfunction "1_3") (pintype "passive"))
      (node (ref "X_IN_11") (pin "P") (pinfunction "ANT_P") (pintype "bidirectional"))
    )
    (net (code "62") (name "IN_DMS_8_NC") (class "Default")
      (node (ref "IC3") (pin "13") (pinfunction "-IN_13") (pintype "input"))
      (node (ref "RN6") (pin "1") (pinfunction "1_1") (pintype "passive"))
    )
    (net (code "63") (name "IN_DMS_9") (class "Default")
      (node (ref "IC9") (pin "9") (pinfunction "-IN_9") (pintype "input"))
      (node (ref "RN15") (pin "2") (pinfunction "1_2") (pintype "passive"))
      (node (ref "X_IN_12") (pin "P") (pinfunction "ANT_P") (pintype "bidirectional"))
    )
    (net (code "64") (name "IN_DMS_10") (class "Default")
      (node (ref "IC9") (pin "13") (pinfunction "-IN_13") (pintype "input"))
      (node (ref "RN15") (pin "1") (pinfunction "1_1") (pintype "passive"))
      (node (ref "X_IN_13") (pin "P") (pinfunction "ANT_P") (pintype "bidirectional"))
    )
    (net (code "65") (name "IN_DMS_11") (class "Default")
      (node (ref "IC10") (pin "2") (pinfunction "-IN_2") (pintype "input"))
      (node (ref "RN18") (pin "4") (pinfunction "1_4") (pintype "passive"))
      (node (ref "X_IN_14") (pin "P") (pinfunction "ANT_P") (pintype "bidirectional"))
    )
    (net (code "66") (name "IN_DMS_12") (class "Default")
      (node (ref "IC10") (pin "6") (pinfunction "-IN_6") (pintype "input"))
      (node (ref "RN18") (pin "3") (pinfunction "1_3") (pintype "passive"))
      (node (ref "X_IN_15") (pin "P") (pinfunction "ANT_P") (pintype "bidirectional"))
    )
    (net (code "67") (name "IN_PT_1") (class "Default")
      (node (ref "IC4") (pin "2") (pinfunction "-IN_2") (pintype "input"))
      (node (ref "RN9") (pin "4") (pinfunction "1_4") (pintype "passive"))
      (node (ref "X_IN_7") (pin "P") (pinfunction "ANT_P") (pintype "bidirectional"))
    )
    (net (code "68") (name "IN_PT_2") (class "Default")
      (node (ref "IC4") (pin "6") (pinfunction "-IN_6") (pintype "input"))
      (node (ref "RN9") (pin "3") (pinfunction "1_3") (pintype "passive"))
      (node (ref "X_IN_8") (pin "P") (pinfunction "ANT_P") (pintype "bidirectional"))
    )
    (net (code "69") (name "IN_PT_3") (class "Default")
      (node (ref "IC4") (pin "9") (pinfunction "-IN_9") (pintype "input"))
      (node (ref "RN9") (pin "2") (pinfunction "1_2") (pintype "passive"))
      (node (ref "X_IN_9") (pin "P") (pinfunction "ANT_P") (pintype "bidirectional"))
    )
    (net (code "70") (name "IN_PT_4_NC") (class "Default")
      (node (ref "IC4") (pin "13") (pinfunction "-IN_13") (pintype "input"))
      (node (ref "RN9") (pin "1") (pinfunction "1_1") (pintype "passive"))
    )
    (net (code "71") (name "LED_1") (class "Default")
      (node (ref "RN10") (pin "1") (pinfunction "1_1") (pintype "passive"))
      (node (ref "U9") (pin "24") (pinfunction "PF5_24") (pintype "bidirectional"))
    )
    (net (code "72") (name "LED_2") (class "Default")
      (node (ref "RN10") (pin "2") (pinfunction "1_2") (pintype "passive"))
      (node (ref "U9") (pin "23") (pinfunction "PF4_23") (pintype "bidirectional"))
    )
    (net (code "73") (name "LED_3") (class "Default")
      (node (ref "RN10") (pin "3") (pinfunction "1_3") (pintype "passive"))
      (node (ref "U9") (pin "22") (pinfunction "PF3_22") (pintype "bidirectional"))
    )
    (net (code "74") (name "LED_4") (class "Default")
      (node (ref "RN10") (pin "4") (pinfunction "1_4") (pintype "passive"))
      (node (ref "U9") (pin "21") (pinfunction "PI14_21") (pintype "bidirectional"))
    )
    (net (code "75") (name "LO") (class "Default")
      (node (ref "IC7") (pin "2") (pinfunction "C1_2") (pintype "bidirectional"))
      (node (ref "X1") (pin "7") (pinfunction "F_7") (pintype "passive"))
      (node (ref "X2") (pin "5") (pinfunction "F_5") (pintype "passive"))
    )
    (net (code "76") (name "LO_OPT") (class "Default")
      (node (ref "D7") (pin "C") (pinfunction "C_C") (pintype "passive"))
      (node (ref "IC7") (pin "8") (pinfunction "COL1_8") (pintype "input"))
      (node (ref "RN12") (pin "6") (pinfunction "2_6") (pintype "passive"))
      (node (ref "U9") (pin "208") (pinfunction "PI7_208") (pintype "bidirectional"))
    )
    (net (code "77") (name "MS_SEL") (class "Default")
      (node (ref "JP_MS") (pin "2") (pinfunction "2_2") (pintype "passive"))
      (node (ref "R29") (pin "1") (pinfunction "1_1") (pintype "passive"))
      (node (ref "SJ_MS") (pin "2") (pinfunction "2_2") (pintype "passive"))
      (node (ref "U9") (pin "129") (pinfunction "PG2_129") (pintype "bidirectional"))
    )
    (net (code "78") (name "NRST") (class "Default")
      (node (ref "C18") (pin "1") (pinfunction "1_1") (pintype "passive"))
      (node (ref "JP1") (pin "1") (pinfunction "1_1") (pintype "passive"))
      (node (ref "R26") (pin "1") (pinfunction "1_1") (pintype "passive"))
      (node (ref "U9") (pin "34") (pinfunction "NRST_34") (pintype "bidirectional"))
    )
    (net (code "79") (name "Net-(C44-Pad1)") (class "Default")
      (node (ref "C44") (pin "1") (pinfunction "1_1") (pintype "passive"))
      (node (ref "R10") (pin "1") (pinfunction "1_1") (pintype "passive"))
      (node (ref "R15") (pin "2") (pinfunction "2_2") (pintype "passive"))
    )
    (net (code "80") (name "Net-(IC2A-+IN)") (class "Default")
      (node (ref "IC2") (pin "3") (pinfunction "+IN_3") (pintype "input"))
      (node (ref "RN1") (pin "5") (pinfunction "2_5") (pintype "passive"))
      (node (ref "RN2") (pin "4") (pinfunction "1_4") (pintype "passive"))
    )
    (net (code "81") (name "Net-(IC2B-+IN)") (class "Default")
      (node (ref "IC2") (pin "5") (pinfunction "+IN_5") (pintype "input"))
      (node (ref "RN1") (pin "6") (pinfunction "2_6") (pintype "passive"))
      (node (ref "RN2") (pin "3") (pinfunction "1_3") (pintype "passive"))
    )
    (net (code "82") (name "Net-(IC2C-+IN)") (class "Default")
      (node (ref "IC2") (pin "10") (pinfunction "+IN_10") (pintype "input"))
      (node (ref "RN1") (pin "7") (pinfunction "2_7") (pintype "passive"))
      (node (ref "RN2") (pin "2") (pinfunction "1_2") (pintype "passive"))
    )
    (net (code "83") (name "Net-(IC2D-+IN)") (class "Default")
      (node (ref "IC2") (pin "12") (pinfunction "+IN_12") (pintype "input"))
      (node (ref "RN1") (pin "8") (pinfunction "2_8") (pintype "passive"))
      (node (ref "RN2") (pin "1") (pinfunction "1_1") (pintype "passive"))
    )
    (net (code "84") (name "Net-(IC2E-V+)") (class "Default")
      (node (ref "C3") (pin "2") (pinfunction "2_2") (pintype "passive"))
      (node (ref "C5") (pin "+") (pinfunction "+_+") (pintype "passive"))
      (node (ref "IC2") (pin "4") (pinfunction "V+_4") (pintype "power_in"))
      (node (ref "L1") (pin "2") (pinfunction "2_2") (pintype "passive"))
    )
    (net (code "85") (name "Net-(IC3A-+IN)") (class "Default")
      (node (ref "IC3") (pin "3") (pinfunction "+IN_3") (pintype "input"))
      (node (ref "RN4") (pin "5") (pinfunction "2_5") (pintype "passive"))
      (node (ref "RN5") (pin "4") (pinfunction "1_4") (pintype "passive"))
    )
    (net (code "86") (name "Net-(IC3B-+IN)") (class "Default")
      (node (ref "IC3") (pin "5") (pinfunction "+IN_5") (pintype "input"))
      (node (ref "RN4") (pin "6") (pinfunction "2_6") (pintype "passive"))
      (node (ref "RN5") (pin "3") (pinfunction "1_3") (pintype "passive"))
    )
    (net (code "87") (name "Net-(IC3C-+IN)") (class "Default")
      (node (ref "IC3") (pin "10") (pinfunction "+IN_10") (pintype "input"))
      (node (ref "RN4") (pin "7") (pinfunction "2_7") (pintype "passive"))
      (node (ref "RN5") (pin "2") (pinfunction "1_2") (pintype "passive"))
    )
    (net (code "88") (name "Net-(IC3D-+IN)") (class "Default")
      (node (ref "IC3") (pin "12") (pinfunction "+IN_12") (pintype "input"))
      (node (ref "RN4") (pin "8") (pinfunction "2_8") (pintype "passive"))
      (node (ref "RN5") (pin "1") (pinfunction "1_1") (pintype "passive"))
    )
    (net (code "89") (name "Net-(IC3E-V+)") (class "Default")
      (node (ref "C10") (pin "+") (pinfunction "+_+") (pintype "passive"))
      (node (ref "C6") (pin "2") (pinfunction "2_2") (pintype "passive"))
      (node (ref "IC3") (pin "4") (pinfunction "V+_4") (pintype "power_in"))
      (node (ref "L2") (pin "2") (pinfunction "2_2") (pintype "passive"))
    )
    (net (code "90") (name "Net-(IC4A-+IN)") (class "Default")
      (node (ref "IC4") (pin "3") (pinfunction "+IN_3") (pintype "input"))
      (node (ref "RN7") (pin "5") (pinfunction "2_5") (pintype "passive"))
      (node (ref "RN8") (pin "4") (pinfunction "1_4") (pintype "passive"))
    )
    (net (code "91") (name "Net-(IC4B-+IN)") (class "Default")
      (node (ref "IC4") (pin "5") (pinfunction "+IN_5") (pintype "input"))
      (node (ref "RN7") (pin "6") (pinfunction "2_6") (pintype "passive"))
      (node (ref "RN8") (pin "3") (pinfunction "1_3") (pintype "passive"))
    )
    (net (code "92") (name "Net-(IC4C-+IN)") (class "Default")
      (node (ref "IC4") (pin "10") (pinfunction "+IN_10") (pintype "input"))
      (node (ref "RN7") (pin "7") (pinfunction "2_7") (pintype "passive"))
      (node (ref "RN8") (pin "2") (pinfunction "1_2") (pintype "passive"))
    )
    (net (code "93") (name "Net-(IC4D-+IN)") (class "Default")
      (node (ref "IC4") (pin "12") (pinfunction "+IN_12") (pintype "input"))
      (node (ref "RN7") (pin "8") (pinfunction "2_8") (pintype "passive"))
      (node (ref "RN8") (pin "1") (pinfunction "1_1") (pintype "passive"))
    )
    (net (code "94") (name "Net-(IC4E-V+)") (class "Default")
      (node (ref "C13") (pin "2") (pinfunction "2_2") (pintype "passive"))
      (node (ref "C15") (pin "+") (pinfunction "+_+") (pintype "passive"))
      (node (ref "IC4") (pin "4") (pinfunction "V+_4") (pintype "power_in"))
      (node (ref "L3") (pin "2") (pinfunction "2_2") (pintype "passive"))
    )
    (net (code "95") (name "Net-(IC6-A1)") (class "Default")
      (node (ref "IC6") (pin "1") (pinfunction "A1_1") (pintype "bidirectional"))
      (node (ref "RN11") (pin "6") (pinfunction "2_6") (pintype "passive"))
    )
    (net (code "96") (name "Net-(IC6-A2)") (class "Default")
      (node (ref "IC6") (pin "3") (pinfunction "A2_3") (pintype "bidirectional"))
      (node (ref "RN11") (pin "5") (pinfunction "2_5") (pintype "passive"))
    )
    (net (code "97") (name "Net-(IC7-A1)") (class "Default")
      (node (ref "IC7") (pin "1") (pinfunction "A1_1") (pintype "bidirectional"))
      (node (ref "RN11") (pin "8") (pinfunction "2_8") (pintype "passive"))
    )
    (net (code "98") (name "Net-(IC7-A2)") (class "Default")
      (node (ref "IC7") (pin "3") (pinfunction "A2_3") (pintype "bidirectional"))
      (node (ref "RN11") (pin "7") (pinfunction "2_7") (pintype "passive"))
    )
    (net (code "99") (name "Net-(IC7-COL2)") (class "Default")
      (node (ref "IC7") (pin "6") (pinfunction "COL2_6") (pintype "input"))
      (node (ref "RN12") (pin "5") (pinfunction "2_5") (pintype "passive"))
    )
    (net (code "100") (name "Net-(IC8-C1)") (class "Default")
      (node (ref "IC8") (pin "2") (pinfunction "C1_2") (pintype "bidirectional"))
      (node (ref "R11") (pin "2") (pinfunction "2_2") (pintype "passive"))
    )
    (net (code "101") (name "Net-(IC8-C2)") (class "Default")
      (node (ref "IC8") (pin "4") (pinfunction "C2_4") (pintype "bidirectional"))
      (node (ref "R12") (pin "2") (pinfunction "2_2") (pintype "passive"))
    )
    (net (code "102") (name "Net-(IC9A-+IN)") (class "Default")
      (node (ref "IC9") (pin "3") (pinfunction "+IN_3") (pintype "input"))
      (node (ref "RN13") (pin "5") (pinfunction "2_5") (pintype "passive"))
      (node (ref "RN14") (pin "4") (pinfunction "1_4") (pintype "passive"))
    )
    (net (code "103") (name "Net-(IC9B-+IN)") (class "Default")
      (node (ref "IC9") (pin "5") (pinfunction "+IN_5") (pintype "input"))
      (node (ref "RN13") (pin "6") (pinfunction "2_6") (pintype "passive"))
      (node (ref "RN14") (pin "3") (pinfunction "1_3") (pintype "passive"))
    )
    (net (code "104") (name "Net-(IC9C-+IN)") (class "Default")
      (node (ref "IC9") (pin "10") (pinfunction "+IN_10") (pintype "input"))
      (node (ref "RN13") (pin "7") (pinfunction "2_7") (pintype "passive"))
      (node (ref "RN14") (pin "2") (pinfunction "1_2") (pintype "passive"))
    )
    (net (code "105") (name "Net-(IC9D-+IN)") (class "Default")
      (node (ref "IC9") (pin "12") (pinfunction "+IN_12") (pintype "input"))
      (node (ref "RN13") (pin "8") (pinfunction "2_8") (pintype "passive"))
      (node (ref "RN14") (pin "1") (pinfunction "1_1") (pintype "passive"))
    )
    (net (code "106") (name "Net-(IC9E-V+)") (class "Default")
      (node (ref "C54") (pin "2") (pinfunction "2_2") (pintype "passive"))
      (node (ref "IC9") (pin "4") (pinfunction "V+_4") (pintype "power_in"))
      (node (ref "L4") (pin "2") (pinfunction "2_2") (pintype "passive"))
    )
    (net (code "107") (name "Net-(IC10A-+IN)") (class "Default")
      (node (ref "IC10") (pin "3") (pinfunction "+IN_3") (pintype "input"))
      (node (ref "RN16") (pin "5") (pinfunction "2_5") (pintype "passive"))
      (node (ref "RN17") (pin "4") (pinfunction "1_4") (pintype "passive"))
    )
    (net (code "108") (name "Net-(IC10B-+IN)") (class "Default")
      (node (ref "IC10") (pin "5") (pinfunction "+IN_5") (pintype "input"))
      (node (ref "RN16") (pin "6") (pinfunction "2_6") (pintype "passive"))
      (node (ref "RN17") (pin "3") (pinfunction "1_3") (pintype "passive"))
    )
    (net (code "109") (name "Net-(IC10E-V+)") (class "Default")
      (node (ref "C57") (pin "2") (pinfunction "2_2") (pintype "passive"))
      (node (ref "IC10") (pin "4") (pinfunction "V+_4") (pintype "power_in"))
      (node (ref "L5") (pin "2") (pinfunction "2_2") (pintype "passive"))
    )
    (net (code "110") (name "Net-(IC13-XI)") (class "Default")
      (node (ref "C1") (pin "1") (pinfunction "1_1") (pintype "passive"))
      (node (ref "IC13") (pin "7") (pinfunction "XI_7") (pintype "bidirectional"))
      (node (ref "Q1") (pin "1") (pinfunction "1_1") (pintype "passive"))
    )
    (net (code "111") (name "Net-(IC13-XO)") (class "Default")
      (node (ref "C2") (pin "1") (pinfunction "1_1") (pintype "passive"))
      (node (ref "IC13") (pin "8") (pinfunction "XO_8") (pintype "bidirectional"))
      (node (ref "Q1") (pin "2") (pinfunction "2_2") (pintype "passive"))
    )
    (net (code "112") (name "Net-(LED5-PadA)") (class "Default")
      (node (ref "LED5") (pin "A") (pinfunction "A_A") (pintype "passive"))
      (node (ref "R18") (pin "1") (pinfunction "1_1") (pintype "passive"))
    )
    (net (code "113") (name "Net-(LED6-PadA)") (class "Default")
      (node (ref "LED6") (pin "A") (pinfunction "A_A") (pintype "passive"))
      (node (ref "R19") (pin "1") (pinfunction "1_1") (pintype "passive"))
    )
    (net (code "114") (name "Net-(LED7-PadA)") (class "Default")
      (node (ref "LED7") (pin "A") (pinfunction "A_A") (pintype "passive"))
      (node (ref "R20") (pin "1") (pinfunction "1_1") (pintype "passive"))
    )
    (net (code "115") (name "Net-(LED8-PadA)") (class "Default")
      (node (ref "LED8") (pin "A") (pinfunction "A_A") (pintype "passive"))
      (node (ref "R21") (pin "1") (pinfunction "1_1") (pintype "passive"))
    )
    (net (code "116") (name "Net-(R1-Pad2)") (class "Default")
      (node (ref "R1") (pin "2") (pinfunction "2_2") (pintype "passive"))
      (node (ref "R3") (pin "1") (pinfunction "1_1") (pintype "passive"))
      (node (ref "R4") (pin "2") (pinfunction "2_2") (pintype "passive"))
    )
    (net (code "117") (name "Net-(R2-Pad2)") (class "Default")
      (node (ref "R2") (pin "2") (pinfunction "2_2") (pintype "passive"))
      (node (ref "R4") (pin "1") (pinfunction "1_1") (pintype "passive"))
    )
    (net (code "118") (name "Net-(R5-Pad2)") (class "Default")
      (node (ref "R5") (pin "2") (pinfunction "2_2") (pintype "passive"))
      (node (ref "R7") (pin "1") (pinfunction "1_1") (pintype "passive"))
      (node (ref "R8") (pin "2") (pinfunction "2_2") (pintype "passive"))
    )
    (net (code "119") (name "Net-(R6-Pad2)") (class "Default")
      (node (ref "R6") (pin "2") (pinfunction "2_2") (pintype "passive"))
      (node (ref "R8") (pin "1") (pinfunction "1_1") (pintype "passive"))
    )
    (net (code "120") (name "Net-(R22-Pad2)") (class "Default")
      (node (ref "R22") (pin "2") (pinfunction "2_2") (pintype "passive"))
      (node (ref "R24") (pin "1") (pinfunction "1_1") (pintype "passive"))
      (node (ref "R25") (pin "2") (pinfunction "2_2") (pintype "passive"))
    )
    (net (code "121") (name "Net-(R23-Pad2)") (class "Default")
      (node (ref "R23") (pin "2") (pinfunction "2_2") (pintype "passive"))
      (node (ref "R25") (pin "1") (pinfunction "1_1") (pintype "passive"))
    )
    (net (code "122") (name "Net-(RN10A-2)") (class "Default")
      (node (ref "LED1") (pin "A") (pinfunction "A_A") (pintype "passive"))
      (node (ref "RN10") (pin "8") (pinfunction "2_8") (pintype "passive"))
    )
    (net (code "123") (name "Net-(RN10B-2)") (class "Default")
      (node (ref "LED2") (pin "A") (pinfunction "A_A") (pintype "passive"))
      (node (ref "RN10") (pin "7") (pinfunction "2_7") (pintype "passive"))
    )
    (net (code "124") (name "Net-(RN10C-2)") (class "Default")
      (node (ref "LED3") (pin "A") (pinfunction "A_A") (pintype "passive"))
      (node (ref "RN10") (pin "6") (pinfunction "2_6") (pintype "passive"))
    )
    (net (code "125") (name "Net-(RN10D-2)") (class "Default")
      (node (ref "LED4") (pin "A") (pinfunction "A_A") (pintype "passive"))
      (node (ref "RN10") (pin "5") (pinfunction "2_5") (pintype "passive"))
    )
    (net (code "126") (name "Net-(RN16A-2)") (class "Default")
      (node (ref "RN16") (pin "8") (pinfunction "2_8") (pintype "passive"))
      (node (ref "RN17") (pin "1") (pinfunction "1_1") (pintype "passive"))
    )
    (net (code "127") (name "Net-(RN16B-2)") (class "Default")
      (node (ref "RN16") (pin "7") (pinfunction "2_7") (pintype "passive"))
      (node (ref "RN17") (pin "2") (pinfunction "1_2") (pintype "passive"))
    )
    (net (code "128") (name "Net-(U1-TRIM)") (class "Default")
      (node (ref "R1") (pin "1") (pinfunction "1_1") (pintype "passive"))
      (node (ref "U1") (pin "5") (pinfunction "TRIM_5") (pintype "passive"))
    )
    (net (code "129") (name "Net-(U2-TRIM)") (class "Default")
      (node (ref "R5") (pin "1") (pinfunction "1_1") (pintype "passive"))
      (node (ref "U2") (pin "5") (pinfunction "TRIM_5") (pintype "passive"))
    )
    (net (code "130") (name "Net-(U3-VREFOUT)") (class "Default")
      (node (ref "C21") (pin "1") (pinfunction "1_1") (pintype "passive"))
      (node (ref "U3") (pin "9") (pinfunction "VREFOUT_9") (pintype "bidirectional"))
    )
    (net (code "131") (name "Net-(U4-VREFOUT)") (class "Default")
      (node (ref "C24") (pin "1") (pinfunction "1_1") (pintype "passive"))
      (node (ref "U4") (pin "9") (pinfunction "VREFOUT_9") (pintype "bidirectional"))
    )
    (net (code "132") (name "Net-(U5-VREFOUT)") (class "Default")
      (node (ref "C27") (pin "1") (pinfunction "1_1") (pintype "passive"))
      (node (ref "U5") (pin "9") (pinfunction "VREFOUT_9") (pintype "bidirectional"))
    )
    (net (code "133") (name "Net-(U9-BOOT0)") (class "Default")
      (node (ref "R27") (pin "1") (pinfunction "1_1") (pintype "passive"))
      (node (ref "R28") (pin "2") (pinfunction "2_2") (pintype "passive"))
      (node (ref "U9") (pin "197") (pinfunction "BOOT0_197") (pintype "bidirectional"))
    )
    (net (code "134") (name "Net-(U9-VCAPDSI)") (class "Default")
      (node (ref "U9") (pin "119") (pinfunction "VCAPDSI_119") (pintype "bidirectional"))
      (node (ref "U9") (pin "125") (pinfunction "VDD12DSI_125") (pintype "bidirectional"))
    )
    (net (code "135") (name "Net-(U9-VCAP_1)") (class "Default")
      (node (ref "C17") (pin "2") (pinfunction "2_2") (pintype "passive"))
      (node (ref "U9") (pin "92") (pinfunction "VCAP_1_92") (pintype "bidirectional"))
    )
    (net (code "136") (name "Net-(U9-VCAP_2)") (class "Default")
      (node (ref "C16") (pin "2") (pinfunction "2_2") (pintype "passive"))
      (node (ref "U9") (pin "148") (pinfunction "VCAP_2_148") (pintype "bidirectional"))
    )
    (net (code "137") (name "Net-(U10-VREFOUT)") (class "Default")
      (node (ref "C47") (pin "1") (pinfunction "1_1") (pintype "passive"))
      (node (ref "U10") (pin "9") (pinfunction "VREFOUT_9") (pintype "bidirectional"))
    )
    (net (code "138") (name "Net-(U11-VREFOUT)") (class "Default")
      (node (ref "C50") (pin "1") (pinfunction "1_1") (pintype "passive"))
      (node (ref "U11") (pin "9") (pinfunction "VREFOUT_9") (pintype "bidirectional"))
    )
    (net (code "139") (name "Net-(U12-VREFOUT)") (class "Default")
      (node (ref "C53") (pin "1") (pinfunction "1_1") (pintype "passive"))
      (node (ref "U12") (pin "9") (pinfunction "VREFOUT_9") (pintype "bidirectional"))
    )
    (net (code "140") (name "Net-(U13-TRIM)") (class "Default")
      (node (ref "R22") (pin "1") (pinfunction "1_1") (pintype "passive"))
      (node (ref "U13") (pin "5") (pinfunction "TRIM_5") (pintype "passive"))
    )
    (net (code "141") (name "OUT_DMS_1") (class "Default")
      (node (ref "IC2") (pin "1") (pinfunction "OUT_1") (pintype "output"))
      (node (ref "RN3") (pin "5") (pinfunction "2_5") (pintype "passive"))
      (node (ref "U4") (pin "11") (pinfunction "AIN0/IEXC_11") (pintype "bidirectional"))
    )
    (net (code "142") (name "OUT_DMS_2") (class "Default")
      (node (ref "IC2") (pin "7") (pinfunction "OUT_7") (pintype "output"))
      (node (ref "RN3") (pin "6") (pinfunction "2_6") (pintype "passive"))
      (node (ref "U4") (pin "17") (pinfunction "AIN2/IEXC/GPIO2_17") (pintype "bidirectional"))
    )
    (net (code "143") (name "OUT_DMS_3") (class "Default")
      (node (ref "IC2") (pin "8") (pinfunction "OUT_8") (pintype "output"))
      (node (ref "RN3") (pin "7") (pinfunction "2_7") (pintype "passive"))
      (node (ref "U3") (pin "11") (pinfunction "AIN0/IEXC_11") (pintype "bidirectional"))
    )
    (net (code "144") (name "OUT_DMS_4") (class "Default")
      (node (ref "IC2") (pin "14") (pinfunction "OUT_14") (pintype "output"))
      (node (ref "RN3") (pin "8") (pinfunction "2_8") (pintype "passive"))
      (node (ref "U3") (pin "17") (pinfunction "AIN2/IEXC/GPIO2_17") (pintype "bidirectional"))
    )
    (net (code "145") (name "OUT_DMS_5") (class "Default")
      (node (ref "IC3") (pin "1") (pinfunction "OUT_1") (pintype "output"))
      (node (ref "RN6") (pin "5") (pinfunction "2_5") (pintype "passive"))
      (node (ref "U5") (pin "11") (pinfunction "AIN0/IEXC_11") (pintype "bidirectional"))
    )
    (net (code "146") (name "OUT_DMS_6") (class "Default")
      (node (ref "IC3") (pin "7") (pinfunction "OUT_7") (pintype "output"))
      (node (ref "RN6") (pin "6") (pinfunction "2_6") (pintype "passive"))
      (node (ref "U5") (pin "17") (pinfunction "AIN2/IEXC/GPIO2_17") (pintype "bidirectional"))
    )
    (net (code "147") (name "OUT_DMS_7") (class "Default")
      (node (ref "IC9") (pin "1") (pinfunction "OUT_1") (pintype "output"))
      (node (ref "RN15") (pin "5") (pinfunction "2_5") (pintype "passive"))
      (node (ref "U11") (pin "11") (pinfunction "AIN0/IEXC_11") (pintype "bidirectional"))
    )
    (net (code "148") (name "OUT_DMS_7_NC") (class "Default")
      (node (ref "IC3") (pin "8") (pinfunction "OUT_8") (pintype "output"))
      (node (ref "RN6") (pin "7") (pinfunction "2_7") (pintype "passive"))
    )
    (net (code "149") (name "OUT_DMS_8") (class "Default")
      (node (ref "IC9") (pin "7") (pinfunction "OUT_7") (pintype "output"))
      (node (ref "RN15") (pin "6") (pinfunction "2_6") (pintype "passive"))
      (node (ref "U11") (pin "17") (pinfunction "AIN2/IEXC/GPIO2_17") (pintype "bidirectional"))
    )
    (net (code "150") (name "OUT_DMS_8_NC") (class "Default")
      (node (ref "IC3") (pin "14") (pinfunction "OUT_14") (pintype "output"))
      (node (ref "RN6") (pin "8") (pinfunction "2_8") (pintype "passive"))
    )
    (net (code "151") (name "OUT_DMS_9") (class "Default")
      (node (ref "IC9") (pin "8") (pinfunction "OUT_8") (pintype "output"))
      (node (ref "RN15") (pin "7") (pinfunction "2_7") (pintype "passive"))
      (node (ref "U10") (pin "11") (pinfunction "AIN0/IEXC_11") (pintype "bidirectional"))
    )
    (net (code "152") (name "OUT_DMS_10") (class "Default")
      (node (ref "IC9") (pin "14") (pinfunction "OUT_14") (pintype "output"))
      (node (ref "RN15") (pin "8") (pinfunction "2_8") (pintype "passive"))
      (node (ref "U10") (pin "17") (pinfunction "AIN2/IEXC/GPIO2_17") (pintype "bidirectional"))
    )
    (net (code "153") (name "OUT_DMS_11") (class "Default")
      (node (ref "IC10") (pin "1") (pinfunction "OUT_1") (pintype "output"))
      (node (ref "RN18") (pin "5") (pinfunction "2_5") (pintype "passive"))
      (node (ref "U12") (pin "11") (pinfunction "AIN0/IEXC_11") (pintype "bidirectional"))
    )
    (net (code "154") (name "OUT_DMS_12") (class "Default")
      (node (ref "IC10") (pin "7") (pinfunction "OUT_7") (pintype "output"))
      (node (ref "RN18") (pin "6") (pinfunction "2_6") (pintype "passive"))
      (node (ref "U12") (pin "17") (pinfunction "AIN2/IEXC/GPIO2_17") (pintype "bidirectional"))
    )
    (net (code "155") (name "OUT_PT_1") (class "Default")
      (node (ref "IC4") (pin "1") (pinfunction "OUT_1") (pintype "output"))
      (node (ref "RN9") (pin "5") (pinfunction "2_5") (pintype "passive"))
      (node (ref "U9") (pin "62") (pinfunction "PB1_62") (pintype "bidirectional"))
    )
    (net (code "156") (name "OUT_PT_2") (class "Default")
      (node (ref "IC4") (pin "7") (pinfunction "OUT_7") (pintype "output"))
      (node (ref "RN9") (pin "6") (pinfunction "2_6") (pintype "passive"))
      (node (ref "U9") (pin "53") (pinfunction "PA4_53") (pintype "bidirectional"))
    )
    (net (code "157") (name "OUT_PT_3") (class "Default")
      (node (ref "IC4") (pin "8") (pinfunction "OUT_8") (pintype "output"))
      (node (ref "RN9") (pin "7") (pinfunction "2_7") (pintype "passive"))
      (node (ref "U9") (pin "61") (pinfunction "PB0_61") (pintype "bidirectional"))
    )
    (net (code "158") (name "OUT_PT_4_NC") (class "Default")
      (node (ref "IC4") (pin "14") (pinfunction "OUT_14") (pintype "output"))
      (node (ref "RN9") (pin "8") (pinfunction "2_8") (pintype "passive"))
    )
    (net (code "159") (name "PRD_ON") (class "Default")
      (node (ref "R9") (pin "1") (pinfunction "1_1") (pintype "passive"))
      (node (ref "U9") (pin "203") (pinfunction "PDR_ON_203") (pintype "bidirectional"))
    )
    (net (code "160") (name "SODS") (class "Default")
      (node (ref "IC6") (pin "2") (pinfunction "C1_2") (pintype "bidirectional"))
      (node (ref "X1") (pin "5") (pinfunction "F_5") (pintype "passive"))
      (node (ref "X2") (pin "3") (pinfunction "F_3") (pintype "passive"))
    )
    (net (code "161") (name "SODS_OPT") (class "Default")
      (node (ref "D8") (pin "C") (pinfunction "C_C") (pintype "passive"))
      (node (ref "IC6") (pin "8") (pinfunction "COL1_8") (pintype "input"))
      (node (ref "RN12") (pin "8") (pinfunction "2_8") (pintype "passive"))
      (node (ref "U9") (pin "206") (pinfunction "PI5_206") (pintype "bidirectional"))
    )
    (net (code "162") (name "SOE") (class "Default")
      (node (ref "IC6") (pin "4") (pinfunction "C2_4") (pintype "bidirectional"))
      (node (ref "X1") (pin "6") (pinfunction "F_6") (pintype "passive"))
      (node (ref "X2") (pin "4") (pinfunction "F_4") (pintype "passive"))
    )
    (net (code "163") (name "SOE_OPT") (class "Default")
      (node (ref "D9") (pin "C") (pinfunction "C_C") (pintype "passive"))
      (node (ref "IC6") (pin "6") (pinfunction "COL2_6") (pintype "input"))
      (node (ref "RN12") (pin "7") (pinfunction "2_7") (pintype "passive"))
      (node (ref "U9") (pin "207") (pinfunction "PI6_207") (pintype "bidirectional"))
    )
    (net (code "164") (name "SPI2_MISO") (class "Default")
      (node (ref "U8") (pin "8") (pinfunction "SO_8") (pintype "bidirectional"))
      (node (ref "U9") (pin "106") (pinfunction "PB14_106") (pintype "bidirectional"))
    )
    (net (code "165") (name "SPI2_MOSI") (class "Default")
      (node (ref "U8") (pin "15") (pinfunction "SI_15") (pintype "bidirectional"))
      (node (ref "U9") (pin "107") (pinfunction "PB15_107") (pintype "bidirectional"))
    )
    (net (code "166") (name "SPI2_SCK") (class "Default")
      (node (ref "U8") (pin "16") (pinfunction "SCK_16") (pintype "bidirectional"))
      (node (ref "U9") (pin "105") (pinfunction "PB13_105") (pintype "bidirectional"))
    )
    (net (code "167") (name "SPI3_CS") (class "Default")
      (node (ref "U4") (pin "24") (pinfunction "~{CS}_24") (pintype "bidirectional"))
      (node (ref "U9") (pin "66") (pinfunction "PJ1_66") (pintype "bidirectional"))
    )
    (net (code "168") (name "SPI3_CS2") (class "Default")
      (node (ref "U11") (pin "24") (pinfunction "~{CS}_24") (pintype "bidirectional"))
      (node (ref "U9") (pin "18") (pinfunction "PF2_18") (pintype "bidirectional"))
    )
    (net (code "169") (name "SPI3_MISO") (class "Default")
      (node (ref "U11") (pin "26") (pinfunction "DOUT/~{DRDY}_26") (pintype "bidirectional"))
      (node (ref "U4") (pin "26") (pinfunction "DOUT/~{DRDY}_26") (pintype "bidirectional"))
      (node (ref "U9") (pin "162") (pinfunction "PC11_162") (pintype "bidirectional"))
    )
    (net (code "170") (name "SPI3_MOSI") (class "Default")
      (node (ref "U11") (pin "27") (pinfunction "DIN_27") (pintype "bidirectional"))
      (node (ref "U4") (pin "27") (pinfunction "DIN_27") (pintype "bidirectional"))
      (node (ref "U9") (pin "63") (pinfunction "PB2_63") (pintype "bidirectional"))
    )
    (net (code "171") (name "SPI3_SCK") (class "Default")
      (node (ref "U11") (pin "28") (pinfunction "SCLK_28") (pintype "bidirectional"))
      (node (ref "U4") (pin "28") (pinfunction "SCLK_28") (pintype "bidirectional"))
      (node (ref "U9") (pin "161") (pinfunction "PC10_161") (pintype "bidirectional"))
    )
    (net (code "172") (name "SPI4_CS") (class "Default")
      (node (ref "U3") (pin "24") (pinfunction "~{CS}_24") (pintype "bidirectional"))
      (node (ref "U9") (pin "48") (pinfunction "PH4_48") (pintype "bidirectional"))
    )
    (net (code "173") (name "SPI4_CS2") (class "Default")
      (node (ref "U10") (pin "24") (pinfunction "~{CS}_24") (pintype "bidirectional"))
      (node (ref "U9") (pin "19") (pinfunction "PI12_19") (pintype "bidirectional"))
    )
    (net (code "174") (name "SPI4_MISO") (class "Default")
      (node (ref "U10") (pin "26") (pinfunction "DOUT/~{DRDY}_26") (pintype "bidirectional"))
      (node (ref "U3") (pin "26") (pinfunction "DOUT/~{DRDY}_26") (pintype "bidirectional"))
      (node (ref "U9") (pin "4") (pinfunction "PE5_4") (pintype "bidirectional"))
    )
    (net (code "175") (name "SPI4_MOSI") (class "Default")
      (node (ref "U10") (pin "27") (pinfunction "DIN_27") (pintype "bidirectional"))
      (node (ref "U3") (pin "27") (pinfunction "DIN_27") (pintype "bidirectional"))
      (node (ref "U9") (pin "5") (pinfunction "PE6_5") (pintype "bidirectional"))
    )
    (net (code "176") (name "SPI4_SCK") (class "Default")
      (node (ref "U10") (pin "28") (pinfunction "SCLK_28") (pintype "bidirectional"))
      (node (ref "U3") (pin "28") (pinfunction "SCLK_28") (pintype "bidirectional"))
      (node (ref "U9") (pin "1") (pinfunction "PE2_1") (pintype "bidirectional"))
    )
    (net (code "177") (name "SPI5_CS") (class "Default")
      (node (ref "U5") (pin "24") (pinfunction "~{CS}_24") (pintype "bidirectional"))
      (node (ref "U9") (pin "74") (pinfunction "PF13_74") (pintype "bidirectional"))
    )
    (net (code "178") (name "SPI5_CS2") (class "Default")
      (node (ref "U12") (pin "24") (pinfunction "~{CS}_24") (pintype "bidirectional"))
      (node (ref "U9") (pin "20") (pinfunction "PI13_20") (pintype "bidirectional"))
    )
    (net (code "179") (name "SPI5_MISO") (class "Default")
      (node (ref "U12") (pin "26") (pinfunction "DOUT/~{DRDY}_26") (pintype "bidirectional"))
      (node (ref "U5") (pin "26") (pinfunction "DOUT/~{DRDY}_26") (pintype "bidirectional"))
      (node (ref "U9") (pin "29") (pinfunction "PF8_29") (pintype "bidirectional"))
    )
    (net (code "180") (name "SPI5_MOSI") (class "Default")
      (node (ref "U12") (pin "27") (pinfunction "DIN_27") (pintype "bidirectional"))
      (node (ref "U5") (pin "27") (pinfunction "DIN_27") (pintype "bidirectional"))
      (node (ref "U9") (pin "70") (pinfunction "PF11_70") (pintype "bidirectional"))
    )
    (net (code "181") (name "SPI5_SCK") (class "Default")
      (node (ref "U12") (pin "28") (pinfunction "SCLK_28") (pintype "bidirectional"))
      (node (ref "U5") (pin "28") (pinfunction "SCLK_28") (pintype "bidirectional"))
      (node (ref "U9") (pin "28") (pinfunction "PF7_28") (pintype "bidirectional"))
    )
    (net (code "182") (name "SPI6_MISO") (class "Default")
      (node (ref "U7") (pin "8") (pinfunction "SO_8") (pintype "bidirectional"))
      (node (ref "U9") (pin "55") (pinfunction "PA6_55") (pintype "bidirectional"))
    )
    (net (code "183") (name "SPI6_MOSI") (class "Default")
      (node (ref "U7") (pin "15") (pinfunction "SI_15") (pintype "bidirectional"))
      (node (ref "U9") (pin "56") (pinfunction "PA7_56") (pintype "bidirectional"))
    )
    (net (code "184") (name "SPI6_SCK") (class "Default")
      (node (ref "U7") (pin "16") (pinfunction "SCK_16") (pintype "bidirectional"))
      (node (ref "U9") (pin "54") (pinfunction "PA5_54") (pintype "bidirectional"))
    )
    (net (code "185") (name "TCK") (class "Default")
      (node (ref "U9") (pin "159") (pinfunction "PA14_159") (pintype "bidirectional"))
      (node (ref "X_PROG") (pin "9") (pinfunction "9_9") (pintype "passive"))
    )
    (net (code "186") (name "TDI") (class "Default")
      (node (ref "U9") (pin "160") (pinfunction "PA15_160") (pintype "bidirectional"))
      (node (ref "X_PROG") (pin "5") (pinfunction "5_5") (pintype "passive"))
    )
    (net (code "187") (name "TDO") (class "Default")
      (node (ref "U9") (pin "192") (pinfunction "PB3_192") (pintype "bidirectional"))
      (node (ref "X_PROG") (pin "13") (pinfunction "13_13") (pintype "passive"))
    )
    (net (code "188") (name "TMS") (class "Default")
      (node (ref "U9") (pin "147") (pinfunction "PA13_147") (pintype "bidirectional"))
      (node (ref "X_PROG") (pin "7") (pinfunction "7_7") (pintype "passive"))
    )
    (net (code "189") (name "TRST") (class "Default")
      (node (ref "JP1") (pin "2") (pinfunction "2_2") (pintype "passive"))
      (node (ref "U9") (pin "193") (pinfunction "PB4_193") (pintype "bidirectional"))
      (node (ref "X_PROG") (pin "3") (pinfunction "3_3") (pintype "passive"))
    )
    (net (code "190") (name "unconnected-(IC1-RMT_ON_OFF-Pad6)") (class "Default")
      (node (ref "IC1") (pin "6") (pinfunction "RMT_ON_OFF_6") (pintype "input"))
    )
    (net (code "191") (name "unconnected-(IC1-TRIM-Pad4)") (class "Default")
      (node (ref "IC1") (pin "4") (pinfunction "TRIM_4") (pintype "input"))
    )
    (net (code "192") (name "unconnected-(IC7-C2-Pad4)") (class "Default")
      (node (ref "IC7") (pin "4") (pinfunction "C2_4") (pintype "bidirectional"))
    )
    (net (code "193") (name "unconnected-(IC10C-+IN-Pad10)") (class "Default")
      (node (ref "IC10") (pin "10") (pinfunction "+IN_10") (pintype "input"))
    )
    (net (code "194") (name "unconnected-(IC10C--IN-Pad9)") (class "Default")
      (node (ref "IC10") (pin "9") (pinfunction "-IN_9") (pintype "input"))
    )
    (net (code "195") (name "unconnected-(IC10C-OUT-Pad8)") (class "Default")
      (node (ref "IC10") (pin "8") (pinfunction "OUT_8") (pintype "output"))
    )
    (net (code "196") (name "unconnected-(IC10D-+IN-Pad12)") (class "Default")
      (node (ref "IC10") (pin "12") (pinfunction "+IN_12") (pintype "input"))
    )
    (net (code "197") (name "unconnected-(IC10D--IN-Pad13)") (class "Default")
      (node (ref "IC10") (pin "13") (pinfunction "-IN_13") (pintype "input"))
    )
    (net (code "198") (name "unconnected-(IC10D-OUT-Pad14)") (class "Default")
      (node (ref "IC10") (pin "14") (pinfunction "OUT_14") (pintype "output"))
    )
    (net (code "199") (name "unconnected-(IC13-CTS-Pad9)") (class "Default")
      (node (ref "IC13") (pin "9") (pinfunction "CTS_9") (pintype "bidirectional"))
    )
    (net (code "200") (name "unconnected-(IC13-DCD-Pad12)") (class "Default")
      (node (ref "IC13") (pin "12") (pinfunction "DCD_12") (pintype "bidirectional"))
    )
    (net (code "201") (name "unconnected-(IC13-DSR-Pad10)") (class "Default")
      (node (ref "IC13") (pin "10") (pinfunction "DSR_10") (pintype "bidirectional"))
    )
    (net (code "202") (name "unconnected-(IC13-DTR-Pad13)") (class "Default")
      (node (ref "IC13") (pin "13") (pinfunction "DTR_13") (pintype "bidirectional"))
    )
    (net (code "203") (name "unconnected-(IC13-RI-Pad11)") (class "Default")
      (node (ref "IC13") (pin "11") (pinfunction "RI_11") (pintype "bidirectional"))
    )
    (net (code "204") (name "unconnected-(IC13-RS232-Pad15)") (class "Default")
      (node (ref "IC13") (pin "15") (pinfunction "RS232_15") (pintype "bidirectional"))
    )
    (net (code "205") (name "unconnected-(IC13-RTS-Pad14)") (class "Default")
      (node (ref "IC13") (pin "14") (pinfunction "RTS_14") (pintype "bidirectional"))
    )
    (net (code "206") (name "unconnected-(IC13-V3-Pad4)") (class "Default")
      (node (ref "IC13") (pin "4") (pinfunction "V3_4") (pintype "bidirectional"))
    )
    (net (code "207") (name "unconnected-(RN18-Pad1)") (class "Default")
      (node (ref "RN18") (pin "1") (pinfunction "1_1") (pintype "passive"))
    )
    (net (code "208") (name "unconnected-(RN18A-2-Pad8)") (class "Default")
      (node (ref "RN18") (pin "8") (pinfunction "2_8") (pintype "passive"))
    )
    (net (code "209") (name "unconnected-(RN18B-1-Pad2)") (class "Default")
      (node (ref "RN18") (pin "2") (pinfunction "1_2") (pintype "passive"))
    )
    (net (code "210") (name "unconnected-(RN18B-2-Pad7)") (class "Default")
      (node (ref "RN18") (pin "7") (pinfunction "2_7") (pintype "passive"))
    )
    (net (code "211") (name "unconnected-(U3-AIN1{slash}IEXC-Pad12)") (class "Default")
      (node (ref "U3") (pin "12") (pinfunction "AIN1/IEXC_12") (pintype "bidirectional"))
    )
    (net (code "212") (name "unconnected-(U3-AIN3{slash}IEXC{slash}GPIO3-Pad18)") (class "Default")
      (node (ref "U3") (pin "18") (pinfunction "AIN3/IEXC/GPIO3_18") (pintype "bidirectional"))
    )
    (net (code "213") (name "unconnected-(U3-AIN4{slash}IECG{slash}GPIO4-Pad13)") (class "Default")
      (node (ref "U3") (pin "13") (pinfunction "AIN4/IECG/GPIO4_13") (pintype "bidirectional"))
    )
    (net (code "214") (name "unconnected-(U3-AIN5{slash}IEXC{slash}GPIO5-Pad14)") (class "Default")
      (node (ref "U3") (pin "14") (pinfunction "AIN5/IEXC/GPIO5_14") (pintype "bidirectional"))
    )
    (net (code "215") (name "unconnected-(U3-AIN6{slash}IEXC{slash}GPIO6-Pad15)") (class "Default")
      (node (ref "U3") (pin "15") (pinfunction "AIN6/IEXC/GPIO6_15") (pintype "bidirectional"))
    )
    (net (code "216") (name "unconnected-(U3-AIN7{slash}IEXC{slash}GPIO7-Pad16)") (class "Default")
      (node (ref "U3") (pin "16") (pinfunction "AIN7/IEXC/GPIO7_16") (pintype "bidirectional"))
    )
    (net (code "217") (name "unconnected-(U3-IEXC1-Pad20)") (class "Default")
      (node (ref "U3") (pin "20") (pinfunction "IEXC1_20") (pintype "bidirectional"))
    )
    (net (code "218") (name "unconnected-(U3-IEXC2-Pad19)") (class "Default")
      (node (ref "U3") (pin "19") (pinfunction "IEXC2_19") (pintype "bidirectional"))
    )
    (net (code "219") (name "unconnected-(U3-REFN0{slash}GPIO1-Pad6)") (class "Default")
      (node (ref "U3") (pin "6") (pinfunction "REFN0/GPIO1_6") (pintype "bidirectional"))
    )
    (net (code "220") (name "unconnected-(U3-REFN1-Pad8)") (class "Default")
      (node (ref "U3") (pin "8") (pinfunction "REFN1_8") (pintype "bidirectional"))
    )
    (net (code "221") (name "unconnected-(U3-REFP0{slash}GPIO0-Pad5)") (class "Default")
      (node (ref "U3") (pin "5") (pinfunction "REFP0/GPIO0_5") (pintype "bidirectional"))
    )
    (net (code "222") (name "unconnected-(U3-REFP1-Pad7)") (class "Default")
      (node (ref "U3") (pin "7") (pinfunction "REFP1_7") (pintype "bidirectional"))
    )
    (net (code "223") (name "unconnected-(U4-AIN1{slash}IEXC-Pad12)") (class "Default")
      (node (ref "U4") (pin "12") (pinfunction "AIN1/IEXC_12") (pintype "bidirectional"))
    )
    (net (code "224") (name "unconnected-(U4-AIN3{slash}IEXC{slash}GPIO3-Pad18)") (class "Default")
      (node (ref "U4") (pin "18") (pinfunction "AIN3/IEXC/GPIO3_18") (pintype "bidirectional"))
    )
    (net (code "225") (name "unconnected-(U4-AIN4{slash}IECG{slash}GPIO4-Pad13)") (class "Default")
      (node (ref "U4") (pin "13") (pinfunction "AIN4/IECG/GPIO4_13") (pintype "bidirectional"))
    )
    (net (code "226") (name "unconnected-(U4-AIN5{slash}IEXC{slash}GPIO5-Pad14)") (class "Default")
      (node (ref "U4") (pin "14") (pinfunction "AIN5/IEXC/GPIO5_14") (pintype "bidirectional"))
    )
    (net (code "227") (name "unconnected-(U4-AIN6{slash}IEXC{slash}GPIO6-Pad15)") (class "Default")
      (node (ref "U4") (pin "15") (pinfunction "AIN6/IEXC/GPIO6_15") (pintype "bidirectional"))
    )
    (net (code "228") (name "unconnected-(U4-AIN7{slash}IEXC{slash}GPIO7-Pad16)") (class "Default")
      (node (ref "U4") (pin "16") (pinfunction "AIN7/IEXC/GPIO7_16") (pintype "bidirectional"))
    )
    (net (code "229") (name "unconnected-(U4-IEXC1-Pad20)") (class "Default")
      (node (ref "U4") (pin "20") (pinfunction "IEXC1_20") (pintype "bidirectional"))
    )
    (net (code "230") (name "unconnected-(U4-IEXC2-Pad19)") (class "Default")
      (node (ref "U4") (pin "19") (pinfunction "IEXC2_19") (pintype "bidirectional"))
    )
    (net (code "231") (name "unconnected-(U4-REFN0{slash}GPIO1-Pad6)") (class "Default")
      (node (ref "U4") (pin "6") (pinfunction "REFN0/GPIO1_6") (pintype "bidirectional"))
    )
    (net (code "232") (name "unconnected-(U4-REFN1-Pad8)") (class "Default")
      (node (ref "U4") (pin "8") (pinfunction "REFN1_8") (pintype "bidirectional"))
    )
    (net (code "233") (name "unconnected-(U4-REFP0{slash}GPIO0-Pad5)") (class "Default")
      (node (ref "U4") (pin "5") (pinfunction "REFP0/GPIO0_5") (pintype "bidirectional"))
    )
    (net (code "234") (name "unconnected-(U4-REFP1-Pad7)") (class "Default")
      (node (ref "U4") (pin "7") (pinfunction "REFP1_7") (pintype "bidirectional"))
    )
    (net (code "235") (name "unconnected-(U5-AIN1{slash}IEXC-Pad12)") (class "Default")
      (node (ref "U5") (pin "12") (pinfunction "AIN1/IEXC_12") (pintype "bidirectional"))
    )
    (net (code "236") (name "unconnected-(U5-AIN3{slash}IEXC{slash}GPIO3-Pad18)") (class "Default")
      (node (ref "U5") (pin "18") (pinfunction "AIN3/IEXC/GPIO3_18") (pintype "bidirectional"))
    )
    (net (code "237") (name "unconnected-(U5-AIN4{slash}IECG{slash}GPIO4-Pad13)") (class "Default")
      (node (ref "U5") (pin "13") (pinfunction "AIN4/IECG/GPIO4_13") (pintype "bidirectional"))
    )
    (net (code "238") (name "unconnected-(U5-AIN5{slash}IEXC{slash}GPIO5-Pad14)") (class "Default")
      (node (ref "U5") (pin "14") (pinfunction "AIN5/IEXC/GPIO5_14") (pintype "bidirectional"))
    )
    (net (code "239") (name "unconnected-(U5-AIN6{slash}IEXC{slash}GPIO6-Pad15)") (class "Default")
      (node (ref "U5") (pin "15") (pinfunction "AIN6/IEXC/GPIO6_15") (pintype "bidirectional"))
    )
    (net (code "240") (name "unconnected-(U5-AIN7{slash}IEXC{slash}GPIO7-Pad16)") (class "Default")
      (node (ref "U5") (pin "16") (pinfunction "AIN7/IEXC/GPIO7_16") (pintype "bidirectional"))
    )
    (net (code "241") (name "unconnected-(U5-IEXC1-Pad20)") (class "Default")
      (node (ref "U5") (pin "20") (pinfunction "IEXC1_20") (pintype "bidirectional"))
    )
    (net (code "242") (name "unconnected-(U5-IEXC2-Pad19)") (class "Default")
      (node (ref "U5") (pin "19") (pinfunction "IEXC2_19") (pintype "bidirectional"))
    )
    (net (code "243") (name "unconnected-(U5-REFN0{slash}GPIO1-Pad6)") (class "Default")
      (node (ref "U5") (pin "6") (pinfunction "REFN0/GPIO1_6") (pintype "bidirectional"))
    )
    (net (code "244") (name "unconnected-(U5-REFN1-Pad8)") (class "Default")
      (node (ref "U5") (pin "8") (pinfunction "REFN1_8") (pintype "bidirectional"))
    )
    (net (code "245") (name "unconnected-(U5-REFP0{slash}GPIO0-Pad5)") (class "Default")
      (node (ref "U5") (pin "5") (pinfunction "REFP0/GPIO0_5") (pintype "bidirectional"))
    )
    (net (code "246") (name "unconnected-(U5-REFP1-Pad7)") (class "Default")
      (node (ref "U5") (pin "7") (pinfunction "REFP1_7") (pintype "bidirectional"))
    )
    (net (code "247") (name "unconnected-(U9-DSI_CKN-Pad124)") (class "Default")
      (node (ref "U9") (pin "124") (pinfunction "DSI_CKN_124") (pintype "bidirectional"))
    )
    (net (code "248") (name "unconnected-(U9-DSI_CKP-Pad123)") (class "Default")
      (node (ref "U9") (pin "123") (pinfunction "DSI_CKP_123") (pintype "bidirectional"))
    )
    (net (code "249") (name "unconnected-(U9-DSI_D0N-Pad121)") (class "Default")
      (node (ref "U9") (pin "121") (pinfunction "DSI_D0N_121") (pintype "bidirectional"))
    )
    (net (code "250") (name "unconnected-(U9-DSI_D0P-Pad120)") (class "Default")
      (node (ref "U9") (pin "120") (pinfunction "DSI_D0P_120") (pintype "bidirectional"))
    )
    (net (code "251") (name "unconnected-(U9-DSI_D1N-Pad127)") (class "Default")
      (node (ref "U9") (pin "127") (pinfunction "DSI_D1N_127") (pintype "bidirectional"))
    )
    (net (code "252") (name "unconnected-(U9-DSI_D1P-Pad126)") (class "Default")
      (node (ref "U9") (pin "126") (pinfunction "DSI_D1P_126") (pintype "bidirectional"))
    )
    (net (code "253") (name "unconnected-(U9-PA8-Pad142)") (class "Default")
      (node (ref "U9") (pin "142") (pinfunction "PA8_142") (pintype "bidirectional"))
    )
    (net (code "254") (name "unconnected-(U9-PA9-Pad143)") (class "Default")
      (node (ref "U9") (pin "143") (pinfunction "PA9_143") (pintype "bidirectional"))
    )
    (net (code "255") (name "unconnected-(U9-PA10-Pad144)") (class "Default")
      (node (ref "U9") (pin "144") (pinfunction "PA10_144") (pintype "bidirectional"))
    )
    (net (code "256") (name "unconnected-(U9-PA11-Pad145)") (class "Default")
      (node (ref "U9") (pin "145") (pinfunction "PA11_145") (pintype "bidirectional"))
    )
    (net (code "257") (name "unconnected-(U9-PA12-Pad146)") (class "Default")
      (node (ref "U9") (pin "146") (pinfunction "PA12_146") (pintype "bidirectional"))
    )
    (net (code "258") (name "unconnected-(U9-PB5-Pad194)") (class "Default")
      (node (ref "U9") (pin "194") (pinfunction "PB5_194") (pintype "bidirectional"))
    )
    (net (code "259") (name "unconnected-(U9-PB6-Pad195)") (class "Default")
      (node (ref "U9") (pin "195") (pinfunction "PB6_195") (pintype "bidirectional"))
    )
    (net (code "260") (name "unconnected-(U9-PB7-Pad196)") (class "Default")
      (node (ref "U9") (pin "196") (pinfunction "PB7_196") (pintype "bidirectional"))
    )
    (net (code "261") (name "unconnected-(U9-PB8-Pad198)") (class "Default")
      (node (ref "U9") (pin "198") (pinfunction "PB8_198") (pintype "bidirectional"))
    )
    (net (code "262") (name "unconnected-(U9-PB9-Pad199)") (class "Default")
      (node (ref "U9") (pin "199") (pinfunction "PB9_199") (pintype "bidirectional"))
    )
    (net (code "263") (name "unconnected-(U9-PB10-Pad90)") (class "Default")
      (node (ref "U9") (pin "90") (pinfunction "PB10_90") (pintype "bidirectional"))
    )
    (net (code "264") (name "unconnected-(U9-PB11-Pad91)") (class "Default")
      (node (ref "U9") (pin "91") (pinfunction "PB11_91") (pintype "bidirectional"))
    )
    (net (code "265") (name "unconnected-(U9-PC1-Pad36)") (class "Default")
      (node (ref "U9") (pin "36") (pinfunction "PC1_36") (pintype "bidirectional"))
    )
    (net (code "266") (name "unconnected-(U9-PC4-Pad57)") (class "Default")
      (node (ref "U9") (pin "57") (pinfunction "PC4_57") (pintype "bidirectional"))
    )
    (net (code "267") (name "unconnected-(U9-PC5-Pad58)") (class "Default")
      (node (ref "U9") (pin "58") (pinfunction "PC5_58") (pintype "bidirectional"))
    )
    (net (code "268") (name "unconnected-(U9-PC6-Pad138)") (class "Default")
      (node (ref "U9") (pin "138") (pinfunction "PC6_138") (pintype "bidirectional"))
    )
    (net (code "269") (name "unconnected-(U9-PC7-Pad139)") (class "Default")
      (node (ref "U9") (pin "139") (pinfunction "PC7_139") (pintype "bidirectional"))
    )
    (net (code "270") (name "unconnected-(U9-PC8-Pad140)") (class "Default")
      (node (ref "U9") (pin "140") (pinfunction "PC8_140") (pintype "bidirectional"))
    )
    (net (code "271") (name "unconnected-(U9-PC9-Pad141)") (class "Default")
      (node (ref "U9") (pin "141") (pinfunction "PC9_141") (pintype "bidirectional"))
    )
    (net (code "272") (name "unconnected-(U9-PC13-Pad8)") (class "Default")
      (node (ref "U9") (pin "8") (pinfunction "PC13_8") (pintype "bidirectional"))
    )
    (net (code "273") (name "unconnected-(U9-PC14-Pad9)") (class "Default")
      (node (ref "U9") (pin "9") (pinfunction "PC14_9") (pintype "bidirectional"))
    )
    (net (code "274") (name "unconnected-(U9-PC15-Pad10)") (class "Default")
      (node (ref "U9") (pin "10") (pinfunction "PC15_10") (pintype "bidirectional"))
    )
    (net (code "275") (name "unconnected-(U9-PD0-Pad164)") (class "Default")
      (node (ref "U9") (pin "164") (pinfunction "PD0_164") (pintype "bidirectional"))
    )
    (net (code "276") (name "unconnected-(U9-PD1-Pad165)") (class "Default")
      (node (ref "U9") (pin "165") (pinfunction "PD1_165") (pintype "bidirectional"))
    )
    (net (code "277") (name "unconnected-(U9-PD3-Pad167)") (class "Default")
      (node (ref "U9") (pin "167") (pinfunction "PD3_167") (pintype "bidirectional"))
    )
    (net (code "278") (name "unconnected-(U9-PD4-Pad168)") (class "Default")
      (node (ref "U9") (pin "168") (pinfunction "PD4_168") (pintype "bidirectional"))
    )
    (net (code "279") (name "unconnected-(U9-PD5-Pad169)") (class "Default")
      (node (ref "U9") (pin "169") (pinfunction "PD5_169") (pintype "bidirectional"))
    )
    (net (code "280") (name "unconnected-(U9-PD6-Pad172)") (class "Default")
      (node (ref "U9") (pin "172") (pinfunction "PD6_172") (pintype "bidirectional"))
    )
    (net (code "281") (name "unconnected-(U9-PD7-Pad173)") (class "Default")
      (node (ref "U9") (pin "173") (pinfunction "PD7_173") (pintype "bidirectional"))
    )
    (net (code "282") (name "unconnected-(U9-PD13-Pad113)") (class "Default")
      (node (ref "U9") (pin "113") (pinfunction "PD13_113") (pintype "bidirectional"))
    )
    (net (code "283") (name "unconnected-(U9-PD14-Pad116)") (class "Default")
      (node (ref "U9") (pin "116") (pinfunction "PD14_116") (pintype "bidirectional"))
    )
    (net (code "284") (name "unconnected-(U9-PD15-Pad117)") (class "Default")
      (node (ref "U9") (pin "117") (pinfunction "PD15_117") (pintype "bidirectional"))
    )
    (net (code "285") (name "unconnected-(U9-PE3-Pad2)") (class "Default")
      (node (ref "U9") (pin "2") (pinfunction "PE3_2") (pintype "bidirectional"))
    )
    (net (code "286") (name "unconnected-(U9-PE4-Pad3)") (class "Default")
      (node (ref "U9") (pin "3") (pinfunction "PE4_3") (pintype "bidirectional"))
    )
    (net (code "287") (name "unconnected-(U9-PE7-Pad79)") (class "Default")
      (node (ref "U9") (pin "79") (pinfunction "PE7_79") (pintype "bidirectional"))
    )
    (net (code "288") (name "unconnected-(U9-PE8-Pad80)") (class "Default")
      (node (ref "U9") (pin "80") (pinfunction "PE8_80") (pintype "bidirectional"))
    )
    (net (code "289") (name "unconnected-(U9-PE9-Pad81)") (class "Default")
      (node (ref "U9") (pin "81") (pinfunction "PE9_81") (pintype "bidirectional"))
    )
    (net (code "290") (name "unconnected-(U9-PE10-Pad84)") (class "Default")
      (node (ref "U9") (pin "84") (pinfunction "PE10_84") (pintype "bidirectional"))
    )
    (net (code "291") (name "unconnected-(U9-PE11-Pad85)") (class "Default")
      (node (ref "U9") (pin "85") (pinfunction "PE11_85") (pintype "bidirectional"))
    )
    (net (code "292") (name "unconnected-(U9-PE12-Pad86)") (class "Default")
      (node (ref "U9") (pin "86") (pinfunction "PE12_86") (pintype "bidirectional"))
    )
    (net (code "293") (name "unconnected-(U9-PE13-Pad87)") (class "Default")
      (node (ref "U9") (pin "87") (pinfunction "PE13_87") (pintype "bidirectional"))
    )
    (net (code "294") (name "unconnected-(U9-PE14-Pad88)") (class "Default")
      (node (ref "U9") (pin "88") (pinfunction "PE14_88") (pintype "bidirectional"))
    )
    (net (code "295") (name "unconnected-(U9-PE15-Pad89)") (class "Default")
      (node (ref "U9") (pin "89") (pinfunction "PE15_89") (pintype "bidirectional"))
    )
    (net (code "296") (name "unconnected-(U9-PF0-Pad16)") (class "Default")
      (node (ref "U9") (pin "16") (pinfunction "PF0_16") (pintype "bidirectional"))
    )
    (net (code "297") (name "unconnected-(U9-PF1-Pad17)") (class "Default")
      (node (ref "U9") (pin "17") (pinfunction "PF1_17") (pintype "bidirectional"))
    )
    (net (code "298") (name "unconnected-(U9-PF6-Pad27)") (class "Default")
      (node (ref "U9") (pin "27") (pinfunction "PF6_27") (pintype "bidirectional"))
    )
    (net (code "299") (name "unconnected-(U9-PG0-Pad77)") (class "Default")
      (node (ref "U9") (pin "77") (pinfunction "PG0_77") (pintype "bidirectional"))
    )
    (net (code "300") (name "unconnected-(U9-PG1-Pad78)") (class "Default")
      (node (ref "U9") (pin "78") (pinfunction "PG1_78") (pintype "bidirectional"))
    )
    (net (code "301") (name "unconnected-(U9-PG3-Pad130)") (class "Default")
      (node (ref "U9") (pin "130") (pinfunction "PG3_130") (pintype "bidirectional"))
    )
    (net (code "302") (name "unconnected-(U9-PG4-Pad131)") (class "Default")
      (node (ref "U9") (pin "131") (pinfunction "PG4_131") (pintype "bidirectional"))
    )
    (net (code "303") (name "unconnected-(U9-PG5-Pad132)") (class "Default")
      (node (ref "U9") (pin "132") (pinfunction "PG5_132") (pintype "bidirectional"))
    )
    (net (code "304") (name "unconnected-(U9-PG6-Pad133)") (class "Default")
      (node (ref "U9") (pin "133") (pinfunction "PG6_133") (pintype "bidirectional"))
    )
    (net (code "305") (name "unconnected-(U9-PG7-Pad134)") (class "Default")
      (node (ref "U9") (pin "134") (pinfunction "PG7_134") (pintype "bidirectional"))
    )
    (net (code "306") (name "unconnected-(U9-PG8-Pad135)") (class "Default")
      (node (ref "U9") (pin "135") (pinfunction "PG8_135") (pintype "bidirectional"))
    )
    (net (code "307") (name "unconnected-(U9-PG9-Pad178)") (class "Default")
      (node (ref "U9") (pin "178") (pinfunction "PG9_178") (pintype "bidirectional"))
    )
    (net (code "308") (name "unconnected-(U9-PG10-Pad179)") (class "Default")
      (node (ref "U9") (pin "179") (pinfunction "PG10_179") (pintype "bidirectional"))
    )
    (net (code "309") (name "unconnected-(U9-PG11-Pad180)") (class "Default")
      (node (ref "U9") (pin "180") (pinfunction "PG11_180") (pintype "bidirectional"))
    )
    (net (code "310") (name "unconnected-(U9-PG12-Pad181)") (class "Default")
      (node (ref "U9") (pin "181") (pinfunction "PG12_181") (pintype "bidirectional"))
    )
    (net (code "311") (name "unconnected-(U9-PG13-Pad182)") (class "Default")
      (node (ref "U9") (pin "182") (pinfunction "PG13_182") (pintype "bidirectional"))
    )
    (net (code "312") (name "unconnected-(U9-PG14-Pad183)") (class "Default")
      (node (ref "U9") (pin "183") (pinfunction "PG14_183") (pintype "bidirectional"))
    )
    (net (code "313") (name "unconnected-(U9-PG15-Pad191)") (class "Default")
      (node (ref "U9") (pin "191") (pinfunction "PG15_191") (pintype "bidirectional"))
    )
    (net (code "314") (name "unconnected-(U9-PH2-Pad46)") (class "Default")
      (node (ref "U9") (pin "46") (pinfunction "PH2_46") (pintype "bidirectional"))
    )
    (net (code "315") (name "unconnected-(U9-PH6-Pad96)") (class "Default")
      (node (ref "U9") (pin "96") (pinfunction "PH6_96") (pintype "bidirectional"))
    )
    (net (code "316") (name "unconnected-(U9-PH7-Pad97)") (class "Default")
      (node (ref "U9") (pin "97") (pinfunction "PH7_97") (pintype "bidirectional"))
    )
    (net (code "317") (name "unconnected-(U9-PH8-Pad98)") (class "Default")
      (node (ref "U9") (pin "98") (pinfunction "PH8_98") (pintype "bidirectional"))
    )
    (net (code "318") (name "unconnected-(U9-PH13-Pad151)") (class "Default")
      (node (ref "U9") (pin "151") (pinfunction "PH13_151") (pintype "bidirectional"))
    )
    (net (code "319") (name "unconnected-(U9-PH14-Pad152)") (class "Default")
      (node (ref "U9") (pin "152") (pinfunction "PH14_152") (pintype "bidirectional"))
    )
    (net (code "320") (name "unconnected-(U9-PH15-Pad153)") (class "Default")
      (node (ref "U9") (pin "153") (pinfunction "PH15_153") (pintype "bidirectional"))
    )
    (net (code "321") (name "unconnected-(U9-PI0-Pad154)") (class "Default")
      (node (ref "U9") (pin "154") (pinfunction "PI0_154") (pintype "bidirectional"))
    )
    (net (code "322") (name "unconnected-(U9-PI1-Pad155)") (class "Default")
      (node (ref "U9") (pin "155") (pinfunction "PI1_155") (pintype "bidirectional"))
    )
    (net (code "323") (name "unconnected-(U9-PI2-Pad156)") (class "Default")
      (node (ref "U9") (pin "156") (pinfunction "PI2_156") (pintype "bidirectional"))
    )
    (net (code "324") (name "unconnected-(U9-PI3-Pad157)") (class "Default")
      (node (ref "U9") (pin "157") (pinfunction "PI3_157") (pintype "bidirectional"))
    )
    (net (code "325") (name "unconnected-(U9-PI4-Pad205)") (class "Default")
      (node (ref "U9") (pin "205") (pinfunction "PI4_205") (pintype "bidirectional"))
    )
    (net (code "326") (name "unconnected-(U9-PI8-Pad7)") (class "Default")
      (node (ref "U9") (pin "7") (pinfunction "PI8_7") (pintype "bidirectional"))
    )
    (net (code "327") (name "unconnected-(U9-PI10-Pad12)") (class "Default")
      (node (ref "U9") (pin "12") (pinfunction "PI10_12") (pintype "bidirectional"))
    )
    (net (code "328") (name "unconnected-(U9-PI11-Pad13)") (class "Default")
      (node (ref "U9") (pin "13") (pinfunction "PI11_13") (pintype "bidirectional"))
    )
    (net (code "329") (name "unconnected-(U9-PI15-Pad64)") (class "Default")
      (node (ref "U9") (pin "64") (pinfunction "PI15_64") (pintype "bidirectional"))
    )
    (net (code "330") (name "unconnected-(U9-PJ4-Pad69)") (class "Default")
      (node (ref "U9") (pin "69") (pinfunction "PJ4_69") (pintype "bidirectional"))
    )
    (net (code "331") (name "unconnected-(U9-PJ5-Pad95)") (class "Default")
      (node (ref "U9") (pin "95") (pinfunction "PJ5_95") (pintype "bidirectional"))
    )
    (net (code "332") (name "unconnected-(U9-PJ12-Pad174)") (class "Default")
      (node (ref "U9") (pin "174") (pinfunction "PJ12_174") (pintype "bidirectional"))
    )
    (net (code "333") (name "unconnected-(U9-PJ13-Pad175)") (class "Default")
      (node (ref "U9") (pin "175") (pinfunction "PJ13_175") (pintype "bidirectional"))
    )
    (net (code "334") (name "unconnected-(U9-PJ14-Pad176)") (class "Default")
      (node (ref "U9") (pin "176") (pinfunction "PJ14_176") (pintype "bidirectional"))
    )
    (net (code "335") (name "unconnected-(U9-PJ15-Pad177)") (class "Default")
      (node (ref "U9") (pin "177") (pinfunction "PJ15_177") (pintype "bidirectional"))
    )
    (net (code "336") (name "unconnected-(U9-PK3-Pad186)") (class "Default")
      (node (ref "U9") (pin "186") (pinfunction "PK3_186") (pintype "bidirectional"))
    )
    (net (code "337") (name "unconnected-(U9-PK4-Pad187)") (class "Default")
      (node (ref "U9") (pin "187") (pinfunction "PK4_187") (pintype "bidirectional"))
    )
    (net (code "338") (name "unconnected-(U9-PK5-Pad188)") (class "Default")
      (node (ref "U9") (pin "188") (pinfunction "PK5_188") (pintype "bidirectional"))
    )
    (net (code "339") (name "unconnected-(U9-PK6-Pad189)") (class "Default")
      (node (ref "U9") (pin "189") (pinfunction "PK6_189") (pintype "bidirectional"))
    )
    (net (code "340") (name "unconnected-(U9-PK7-Pad190)") (class "Default")
      (node (ref "U9") (pin "190") (pinfunction "PK7_190") (pintype "bidirectional"))
    )
    (net (code "341") (name "unconnected-(U10-AIN1{slash}IEXC-Pad12)") (class "Default")
      (node (ref "U10") (pin "12") (pinfunction "AIN1/IEXC_12") (pintype "bidirectional"))
    )
    (net (code "342") (name "unconnected-(U10-AIN3{slash}IEXC{slash}GPIO3-Pad18)") (class "Default")
      (node (ref "U10") (pin "18") (pinfunction "AIN3/IEXC/GPIO3_18") (pintype "bidirectional"))
    )
    (net (code "343") (name "unconnected-(U10-AIN4{slash}IECG{slash}GPIO4-Pad13)") (class "Default")
      (node (ref "U10") (pin "13") (pinfunction "AIN4/IECG/GPIO4_13") (pintype "bidirectional"))
    )
    (net (code "344") (name "unconnected-(U10-AIN5{slash}IEXC{slash}GPIO5-Pad14)") (class "Default")
      (node (ref "U10") (pin "14") (pinfunction "AIN5/IEXC/GPIO5_14") (pintype "bidirectional"))
    )
    (net (code "345") (name "unconnected-(U10-AIN6{slash}IEXC{slash}GPIO6-Pad15)") (class "Default")
      (node (ref "U10") (pin "15") (pinfunction "AIN6/IEXC/GPIO6_15") (pintype "bidirectional"))
    )
    (net (code "346") (name "unconnected-(U10-AIN7{slash}IEXC{slash}GPIO7-Pad16)") (class "Default")
      (node (ref "U10") (pin "16") (pinfunction "AIN7/IEXC/GPIO7_16") (pintype "bidirectional"))
    )
    (net (code "347") (name "unconnected-(U10-IEXC1-Pad20)") (class "Default")
      (node (ref "U10") (pin "20") (pinfunction "IEXC1_20") (pintype "bidirectional"))
    )
    (net (code "348") (name "unconnected-(U10-IEXC2-Pad19)") (class "Default")
      (node (ref "U10") (pin "19") (pinfunction "IEXC2_19") (pintype "bidirectional"))
    )
    (net (code "349") (name "unconnected-(U10-REFN0{slash}GPIO1-Pad6)") (class "Default")
      (node (ref "U10") (pin "6") (pinfunction "REFN0/GPIO1_6") (pintype "bidirectional"))
    )
    (net (code "350") (name "unconnected-(U10-REFN1-Pad8)") (class "Default")
      (node (ref "U10") (pin "8") (pinfunction "REFN1_8") (pintype "bidirectional"))
    )
    (net (code "351") (name "unconnected-(U10-REFP0{slash}GPIO0-Pad5)") (class "Default")
      (node (ref "U10") (pin "5") (pinfunction "REFP0/GPIO0_5") (pintype "bidirectional"))
    )
    (net (code "352") (name "unconnected-(U10-REFP1-Pad7)") (class "Default")
      (node (ref "U10") (pin "7") (pinfunction "REFP1_7") (pintype "bidirectional"))
    )
    (net (code "353") (name "unconnected-(U11-AIN1{slash}IEXC-Pad12)") (class "Default")
      (node (ref "U11") (pin "12") (pinfunction "AIN1/IEXC_12") (pintype "bidirectional"))
    )
    (net (code "354") (name "unconnected-(U11-AIN3{slash}IEXC{slash}GPIO3-Pad18)") (class "Default")
      (node (ref "U11") (pin "18") (pinfunction "AIN3/IEXC/GPIO3_18") (pintype "bidirectional"))
    )
    (net (code "355") (name "unconnected-(U11-AIN4{slash}IECG{slash}GPIO4-Pad13)") (class "Default")
      (node (ref "U11") (pin "13") (pinfunction "AIN4/IECG/GPIO4_13") (pintype "bidirectional"))
    )
    (net (code "356") (name "unconnected-(U11-AIN5{slash}IEXC{slash}GPIO5-Pad14)") (class "Default")
      (node (ref "U11") (pin "14") (pinfunction "AIN5/IEXC/GPIO5_14") (pintype "bidirectional"))
    )
    (net (code "357") (name "unconnected-(U11-AIN6{slash}IEXC{slash}GPIO6-Pad15)") (class "Default")
      (node (ref "U11") (pin "15") (pinfunction "AIN6/IEXC/GPIO6_15") (pintype "bidirectional"))
    )
    (net (code "358") (name "unconnected-(U11-AIN7{slash}IEXC{slash}GPIO7-Pad16)") (class "Default")
      (node (ref "U11") (pin "16") (pinfunction "AIN7/IEXC/GPIO7_16") (pintype "bidirectional"))
    )
    (net (code "359") (name "unconnected-(U11-IEXC1-Pad20)") (class "Default")
      (node (ref "U11") (pin "20") (pinfunction "IEXC1_20") (pintype "bidirectional"))
    )
    (net (code "360") (name "unconnected-(U11-IEXC2-Pad19)") (class "Default")
      (node (ref "U11") (pin "19") (pinfunction "IEXC2_19") (pintype "bidirectional"))
    )
    (net (code "361") (name "unconnected-(U11-REFN0{slash}GPIO1-Pad6)") (class "Default")
      (node (ref "U11") (pin "6") (pinfunction "REFN0/GPIO1_6") (pintype "bidirectional"))
    )
    (net (code "362") (name "unconnected-(U11-REFN1-Pad8)") (class "Default")
      (node (ref "U11") (pin "8") (pinfunction "REFN1_8") (pintype "bidirectional"))
    )
    (net (code "363") (name "unconnected-(U11-REFP0{slash}GPIO0-Pad5)") (class "Default")
      (node (ref "U11") (pin "5") (pinfunction "REFP0/GPIO0_5") (pintype "bidirectional"))
    )
    (net (code "364") (name "unconnected-(U11-REFP1-Pad7)") (class "Default")
      (node (ref "U11") (pin "7") (pinfunction "REFP1_7") (pintype "bidirectional"))
    )
    (net (code "365") (name "unconnected-(U12-AIN1{slash}IEXC-Pad12)") (class "Default")
      (node (ref "U12") (pin "12") (pinfunction "AIN1/IEXC_12") (pintype "bidirectional"))
    )
    (net (code "366") (name "unconnected-(U12-AIN3{slash}IEXC{slash}GPIO3-Pad18)") (class "Default")
      (node (ref "U12") (pin "18") (pinfunction "AIN3/IEXC/GPIO3_18") (pintype "bidirectional"))
    )
    (net (code "367") (name "unconnected-(U12-AIN4{slash}IECG{slash}GPIO4-Pad13)") (class "Default")
      (node (ref "U12") (pin "13") (pinfunction "AIN4/IECG/GPIO4_13") (pintype "bidirectional"))
    )
    (net (code "368") (name "unconnected-(U12-AIN5{slash}IEXC{slash}GPIO5-Pad14)") (class "Default")
      (node (ref "U12") (pin "14") (pinfunction "AIN5/IEXC/GPIO5_14") (pintype "bidirectional"))
    )
    (net (code "369") (name "unconnected-(U12-AIN6{slash}IEXC{slash}GPIO6-Pad15)") (class "Default")
      (node (ref "U12") (pin "15") (pinfunction "AIN6/IEXC/GPIO6_15") (pintype "bidirectional"))
    )
    (net (code "370") (name "unconnected-(U12-AIN7{slash}IEXC{slash}GPIO7-Pad16)") (class "Default")
      (node (ref "U12") (pin "16") (pinfunction "AIN7/IEXC/GPIO7_16") (pintype "bidirectional"))
    )
    (net (code "371") (name "unconnected-(U12-IEXC1-Pad20)") (class "Default")
      (node (ref "U12") (pin "20") (pinfunction "IEXC1_20") (pintype "bidirectional"))
    )
    (net (code "372") (name "unconnected-(U12-IEXC2-Pad19)") (class "Default")
      (node (ref "U12") (pin "19") (pinfunction "IEXC2_19") (pintype "bidirectional"))
    )
    (net (code "373") (name "unconnected-(U12-REFN0{slash}GPIO1-Pad6)") (class "Default")
      (node (ref "U12") (pin "6") (pinfunction "REFN0/GPIO1_6") (pintype "bidirectional"))
    )
    (net (code "374") (name "unconnected-(U12-REFN1-Pad8)") (class "Default")
      (node (ref "U12") (pin "8") (pinfunction "REFN1_8") (pintype "bidirectional"))
    )
    (net (code "375") (name "unconnected-(U12-REFP0{slash}GPIO0-Pad5)") (class "Default")
      (node (ref "U12") (pin "5") (pinfunction "REFP0/GPIO0_5") (pintype "bidirectional"))
    )
    (net (code "376") (name "unconnected-(U12-REFP1-Pad7)") (class "Default")
      (node (ref "U12") (pin "7") (pinfunction "REFP1_7") (pintype "bidirectional"))
    )
    (net (code "377") (name "unconnected-(X1B-F-Pad2)") (class "Default")
      (node (ref "X1") (pin "2") (pinfunction "F_2") (pintype "passive"))
    )
    (net (code "378") (name "unconnected-(X2B-F-Pad10)") (class "Default")
      (node (ref "X2") (pin "10") (pinfunction "F_10") (pintype "passive"))
    )
    (net (code "379") (name "unconnected-(X2C-F-Pad11)") (class "Default")
      (node (ref "X2") (pin "11") (pinfunction "F_11") (pintype "passive"))
    )
    (net (code "380") (name "unconnected-(X2D-F-Pad12)") (class "Default")
      (node (ref "X2") (pin "12") (pinfunction "F_12") (pintype "passive"))
    )
    (net (code "381") (name "unconnected-(X2H-F-Pad2)") (class "Default")
      (node (ref "X2") (pin "2") (pinfunction "F_2") (pintype "passive"))
    )
    (net (code "382") (name "unconnected-(X_PROG-Pad11)") (class "Default")
      (node (ref "X_PROG") (pin "11") (pinfunction "11_11") (pintype "passive"))
    )
    (net (code "383") (name "unconnected-(X_PROG-Pad12)") (class "Default")
      (node (ref "X_PROG") (pin "12") (pinfunction "12_12") (pintype "passive"))
    )
  )
)
